# EEZ_DIB_DCP505_r1B2.net
KiCad netlist of a schematic drawn in EAGLE
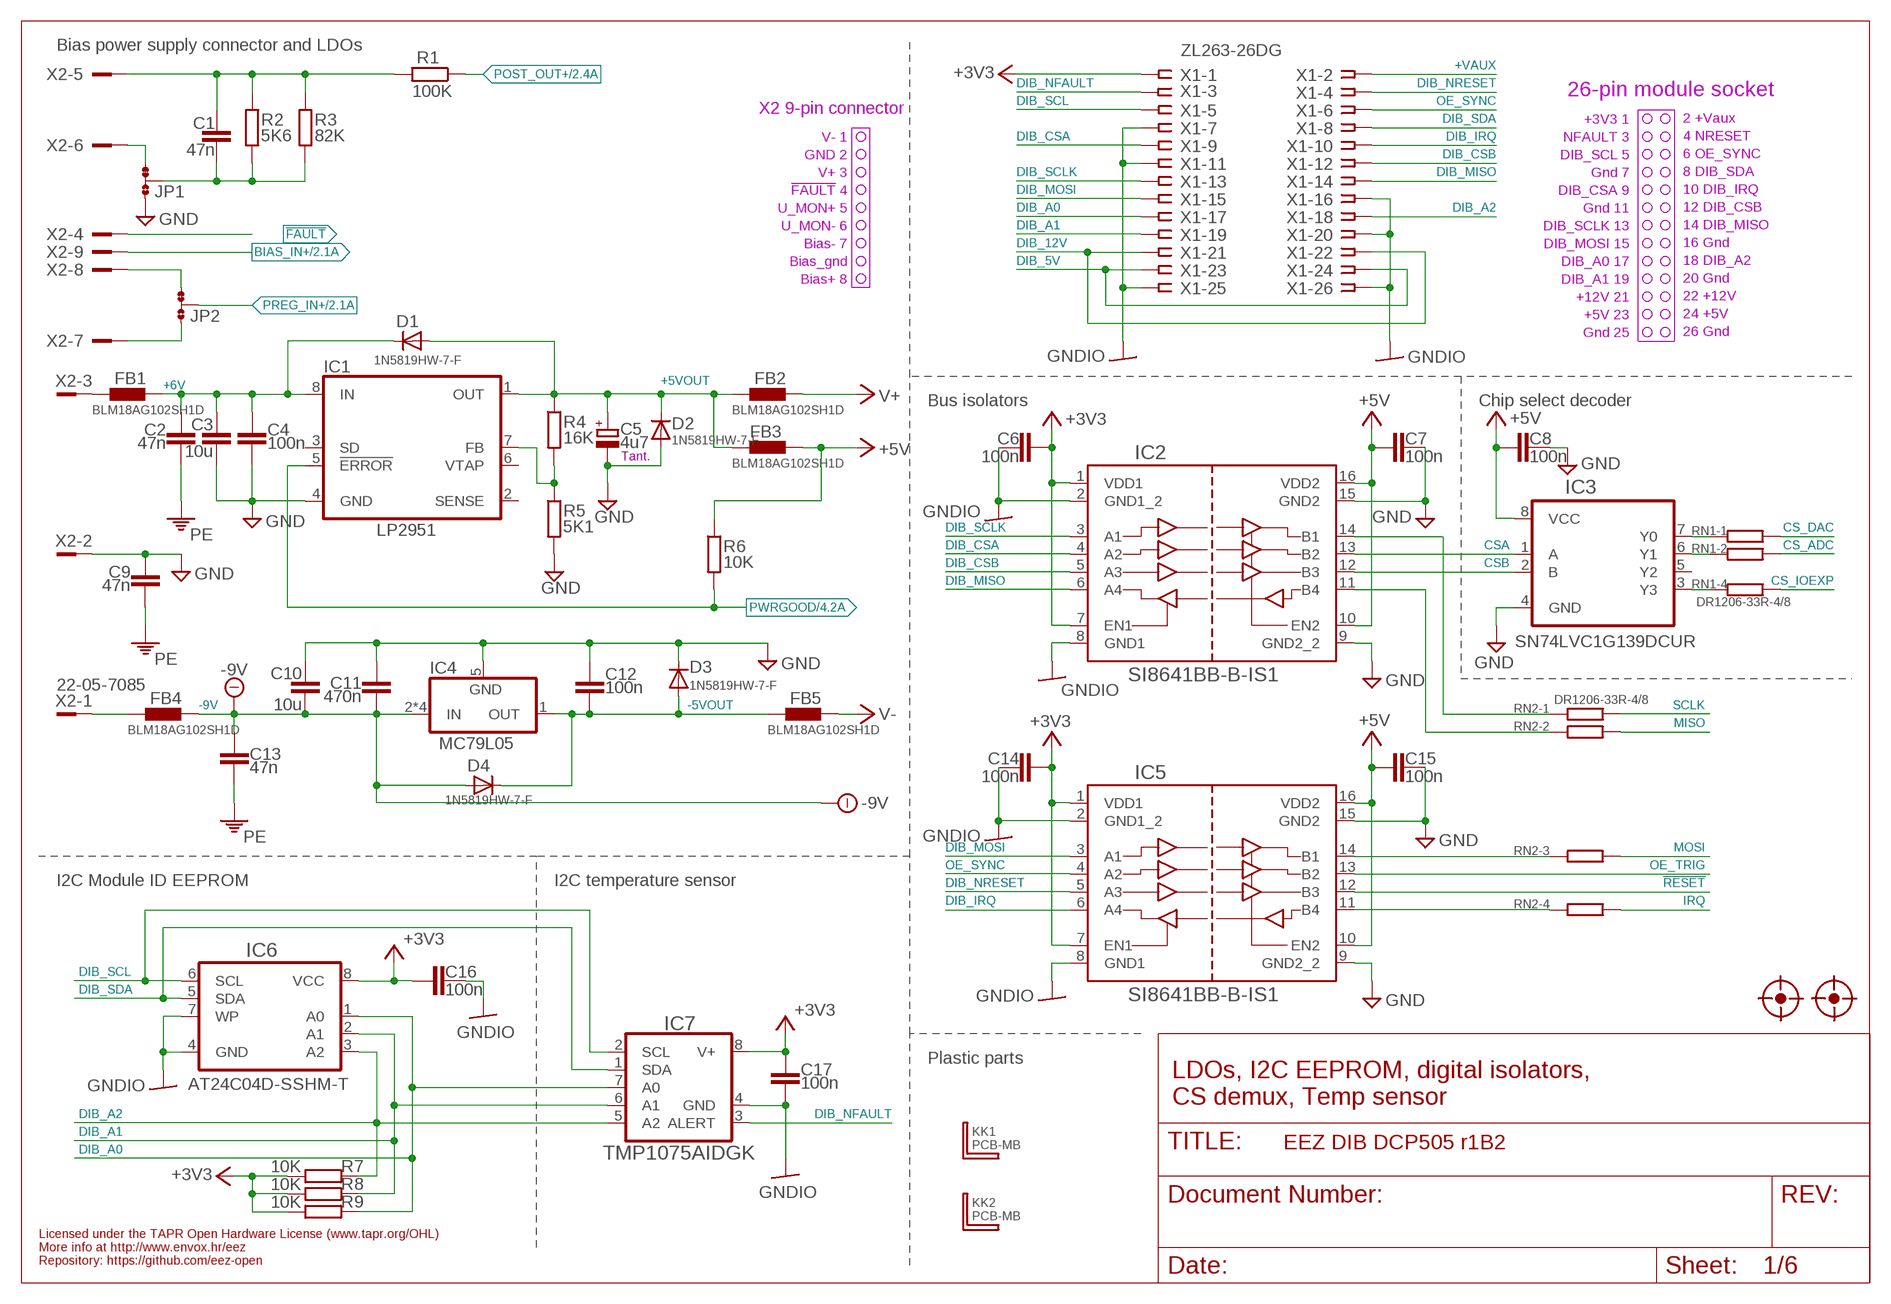
[diagram p0: schematic, sheet 1]
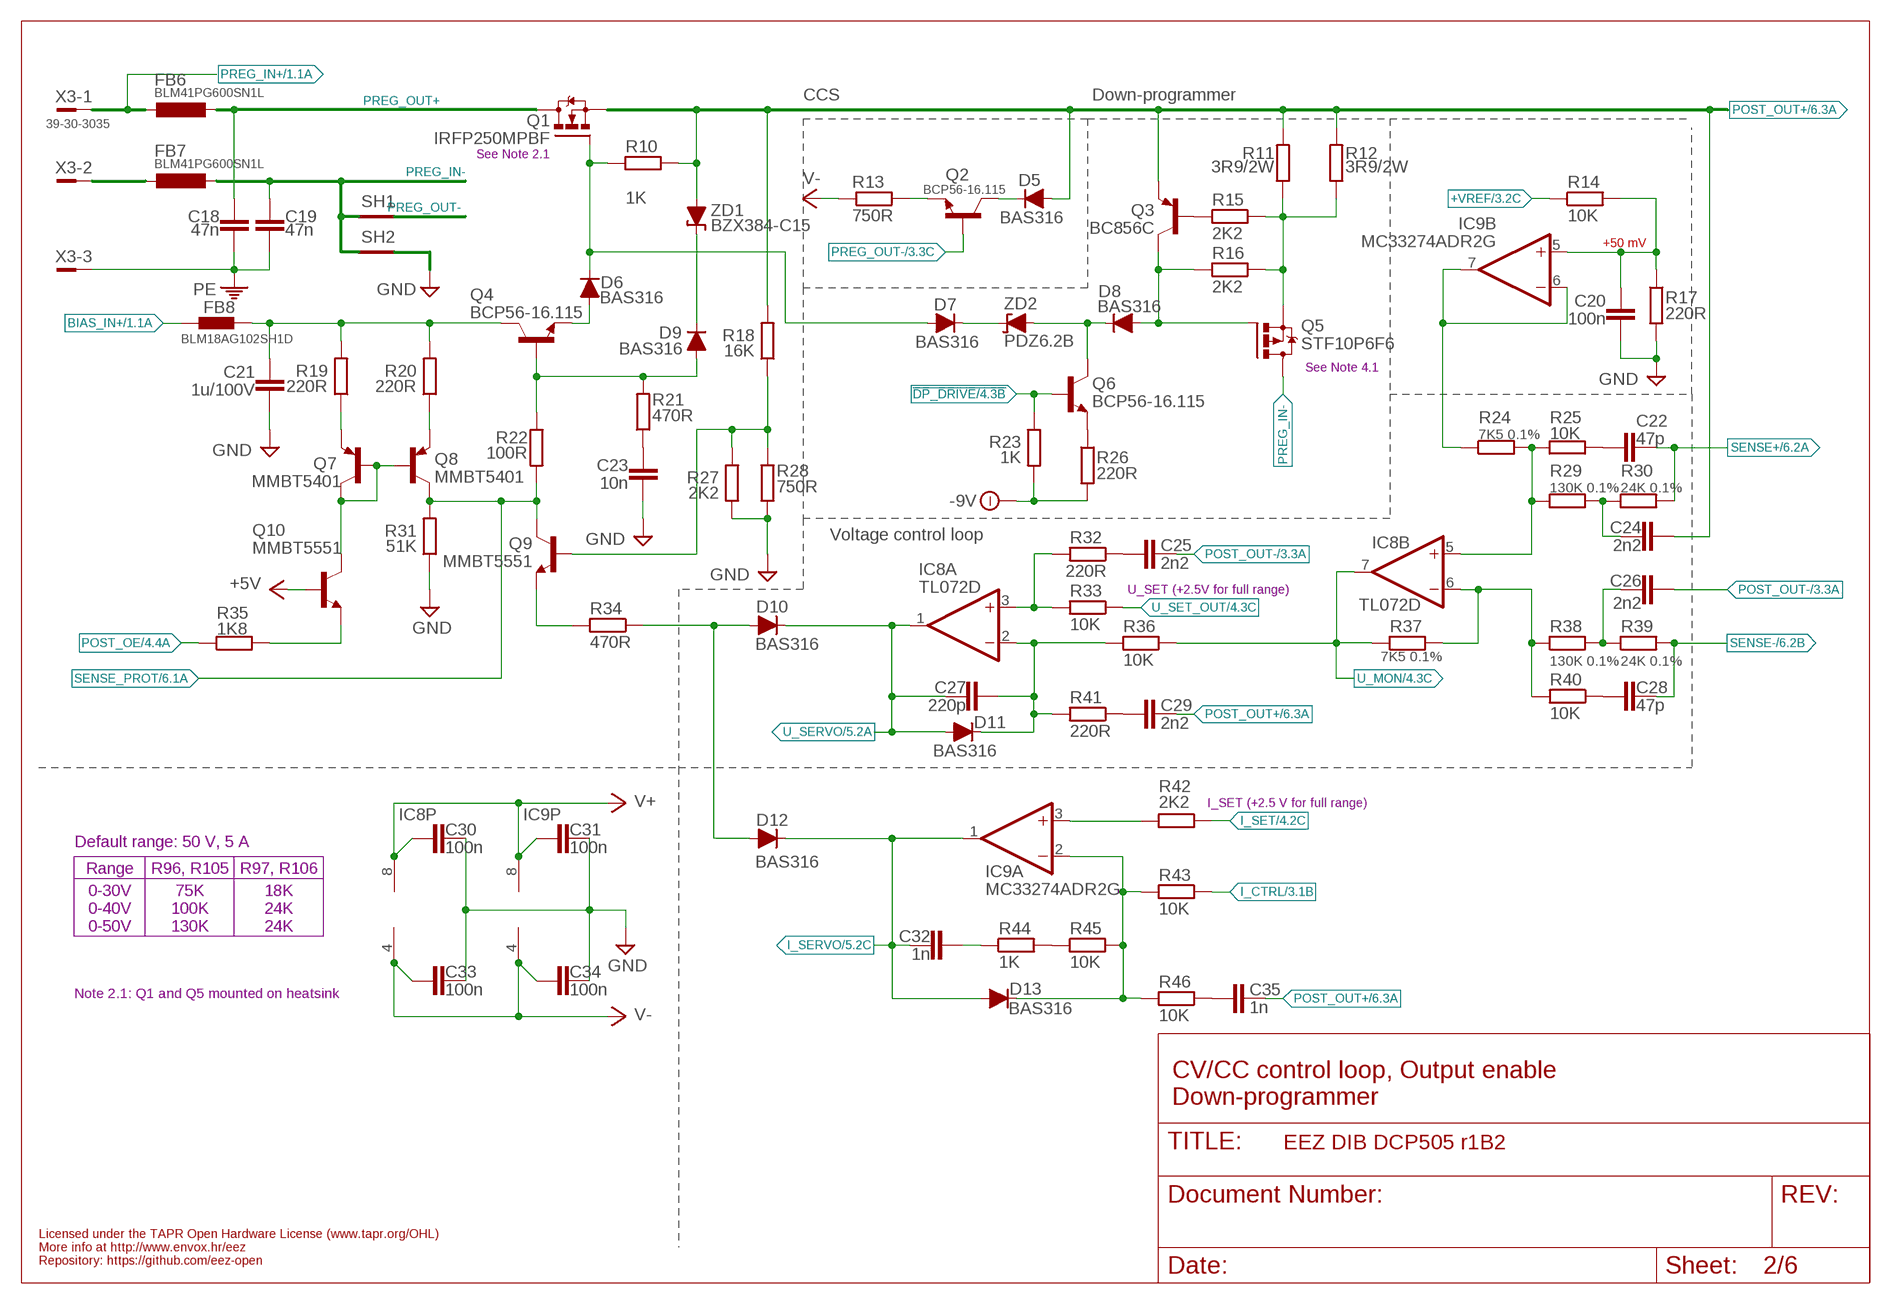
[diagram p1: schematic, sheet 2]
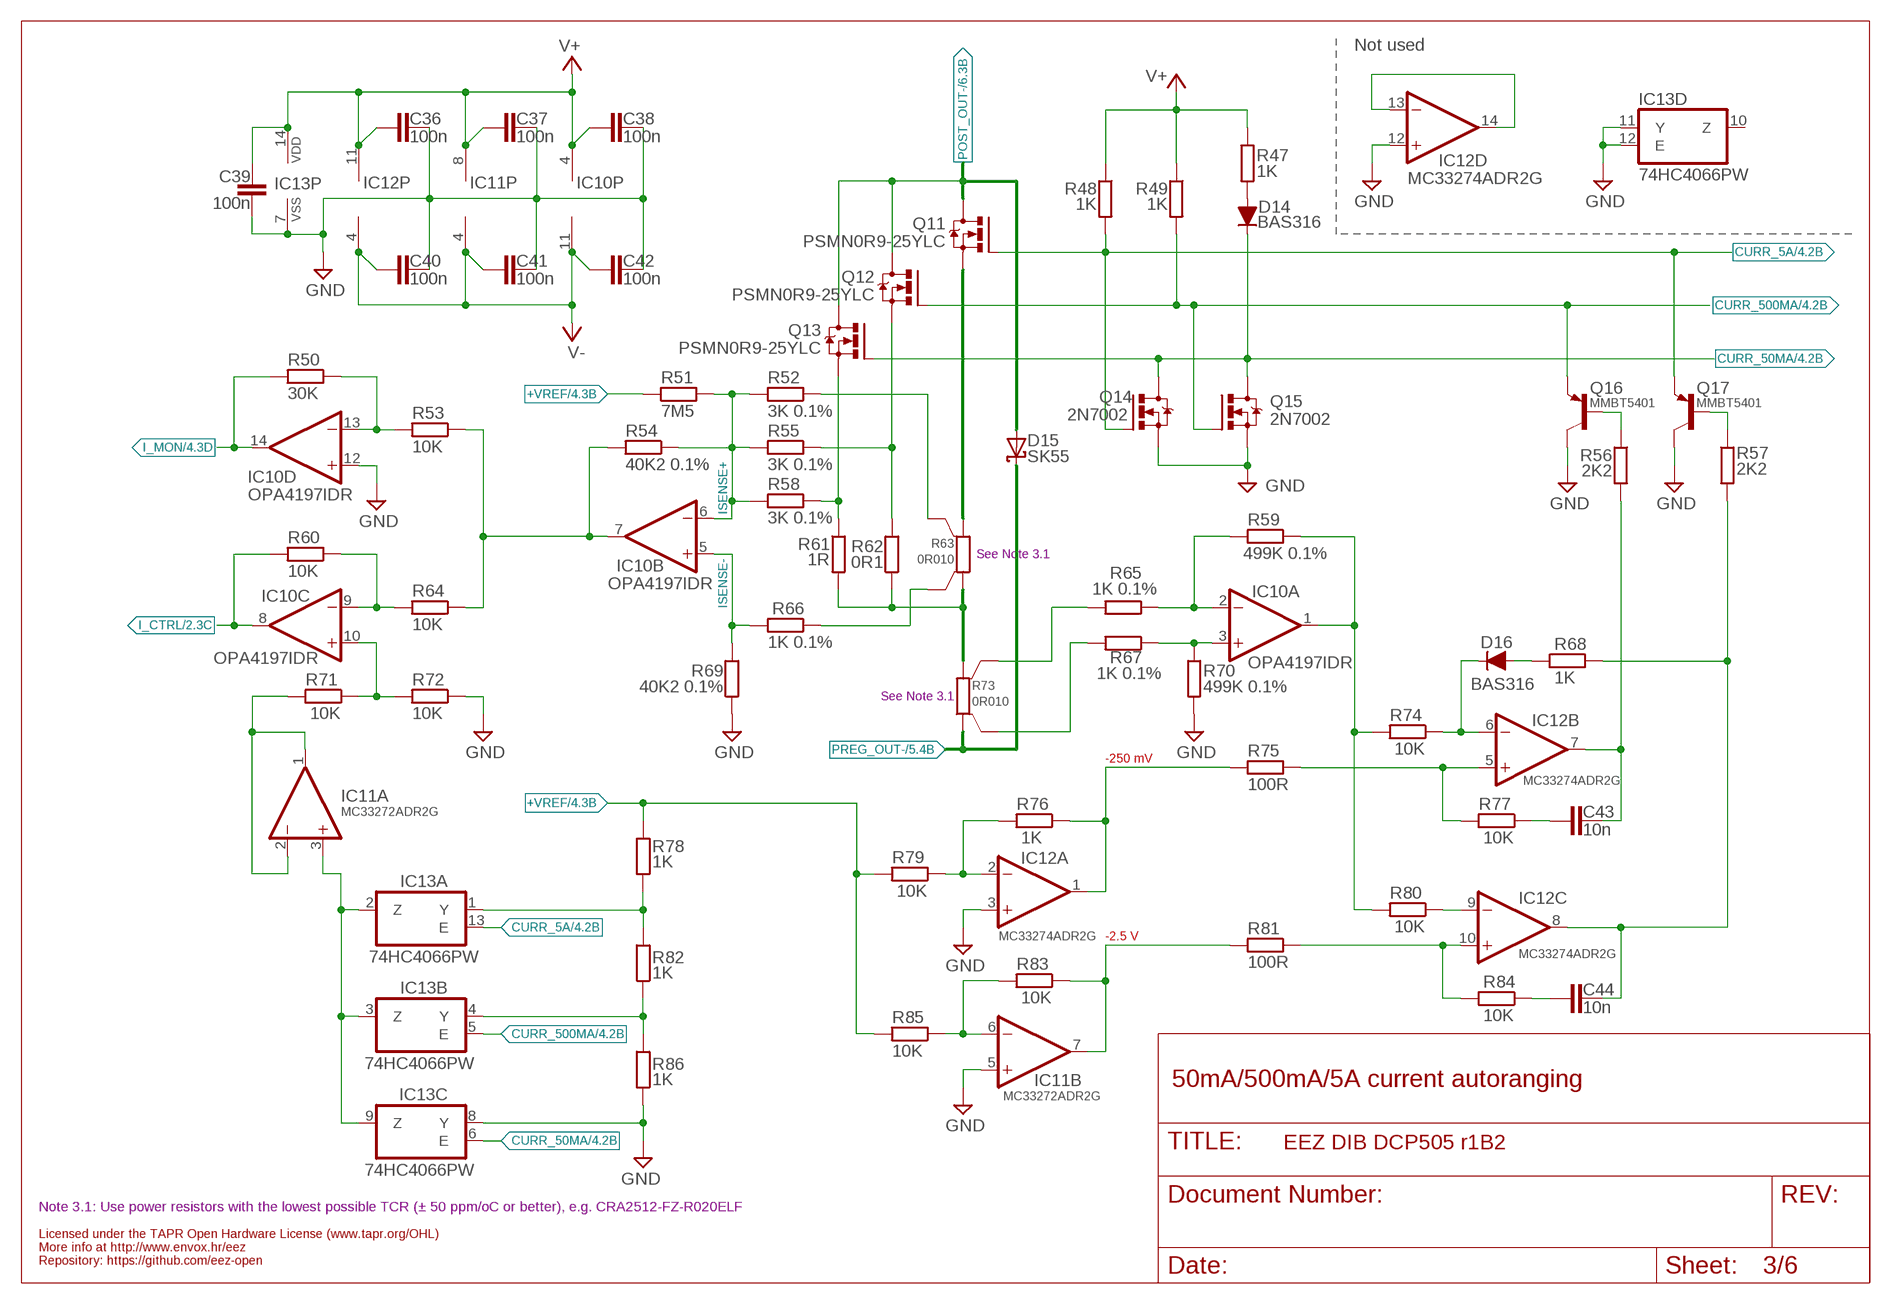
[diagram p2: schematic, sheet 3]
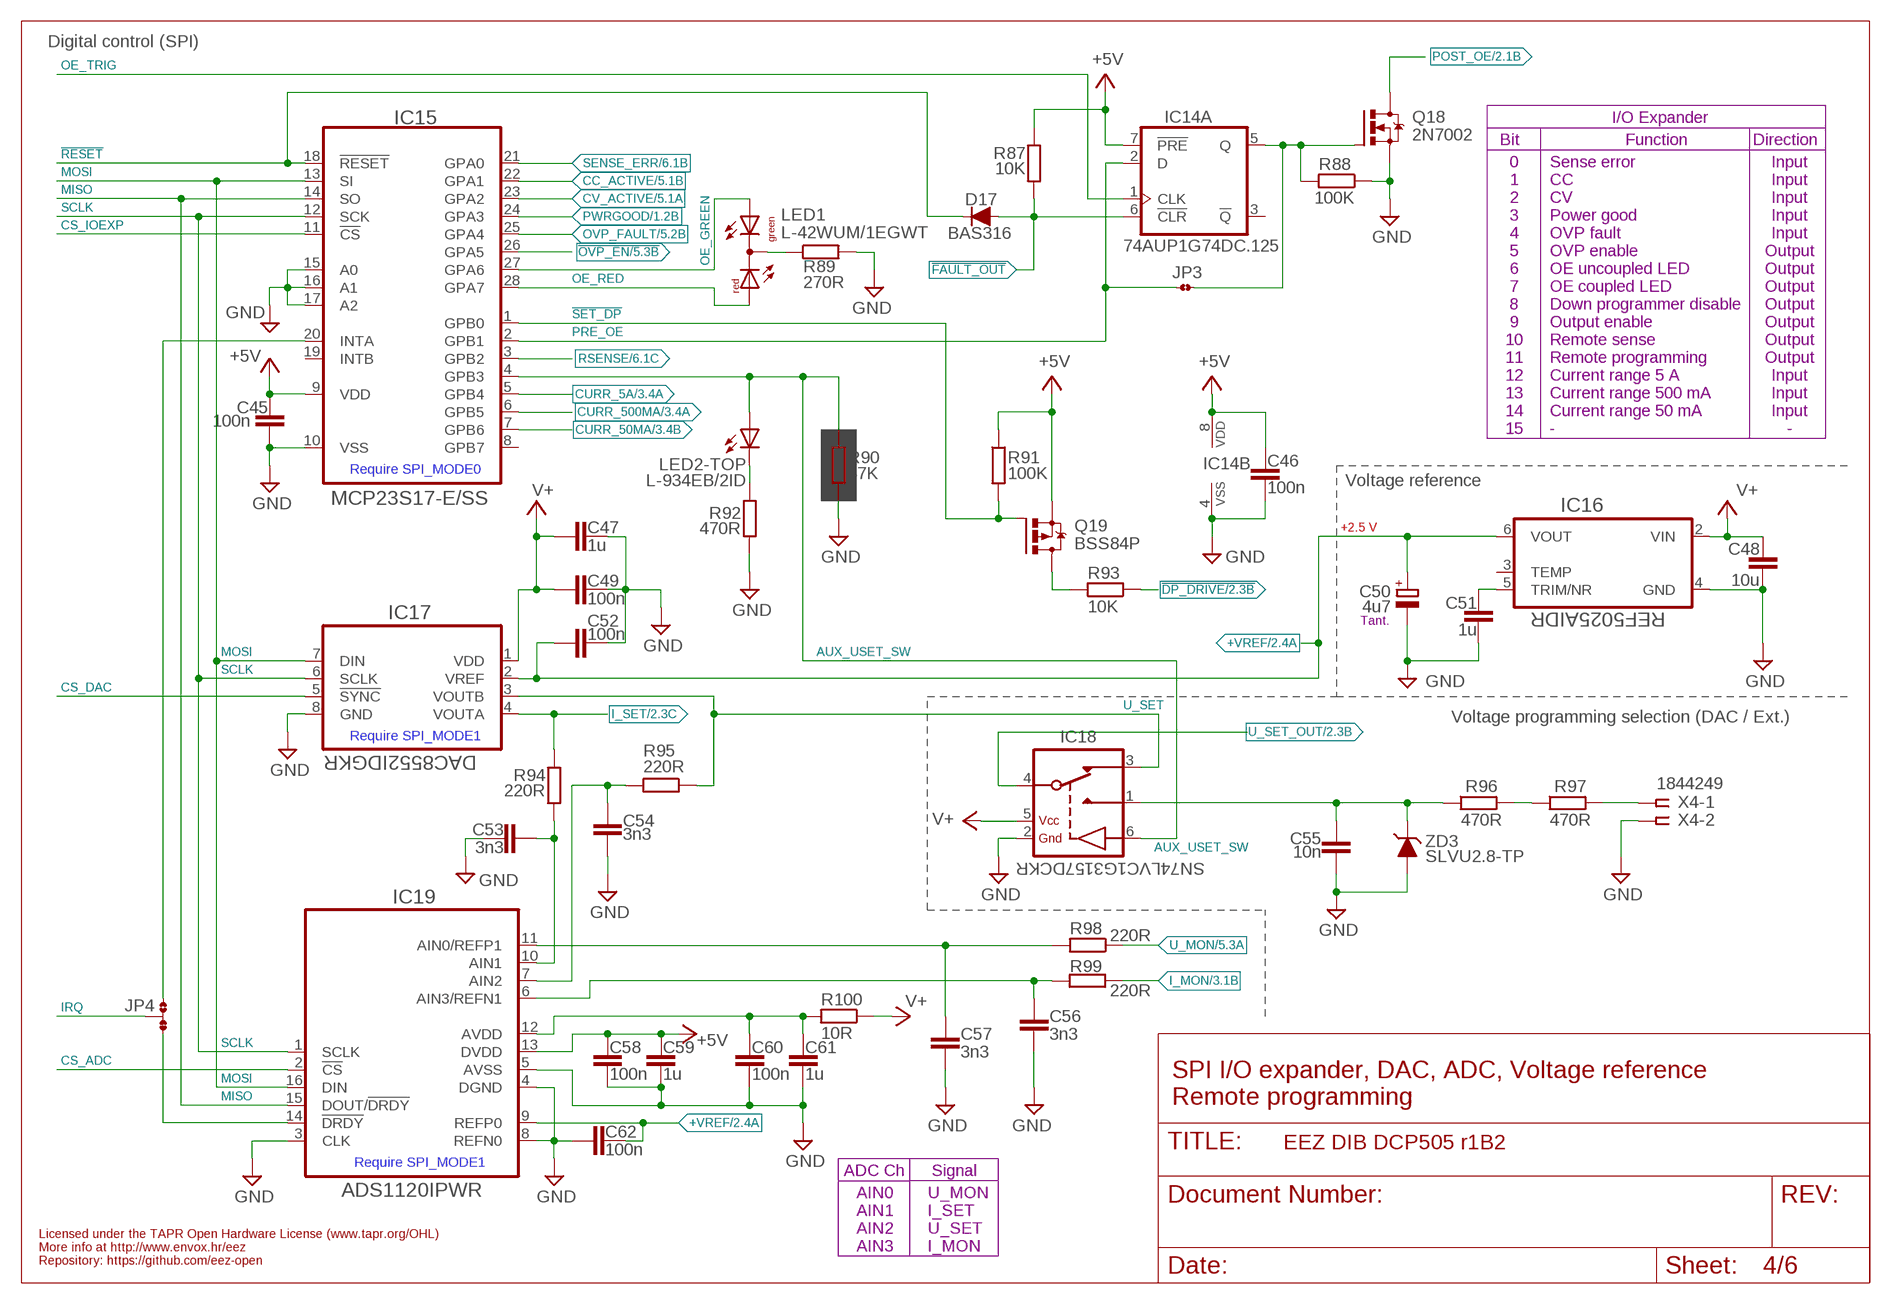
[diagram p3: schematic, sheet 4]
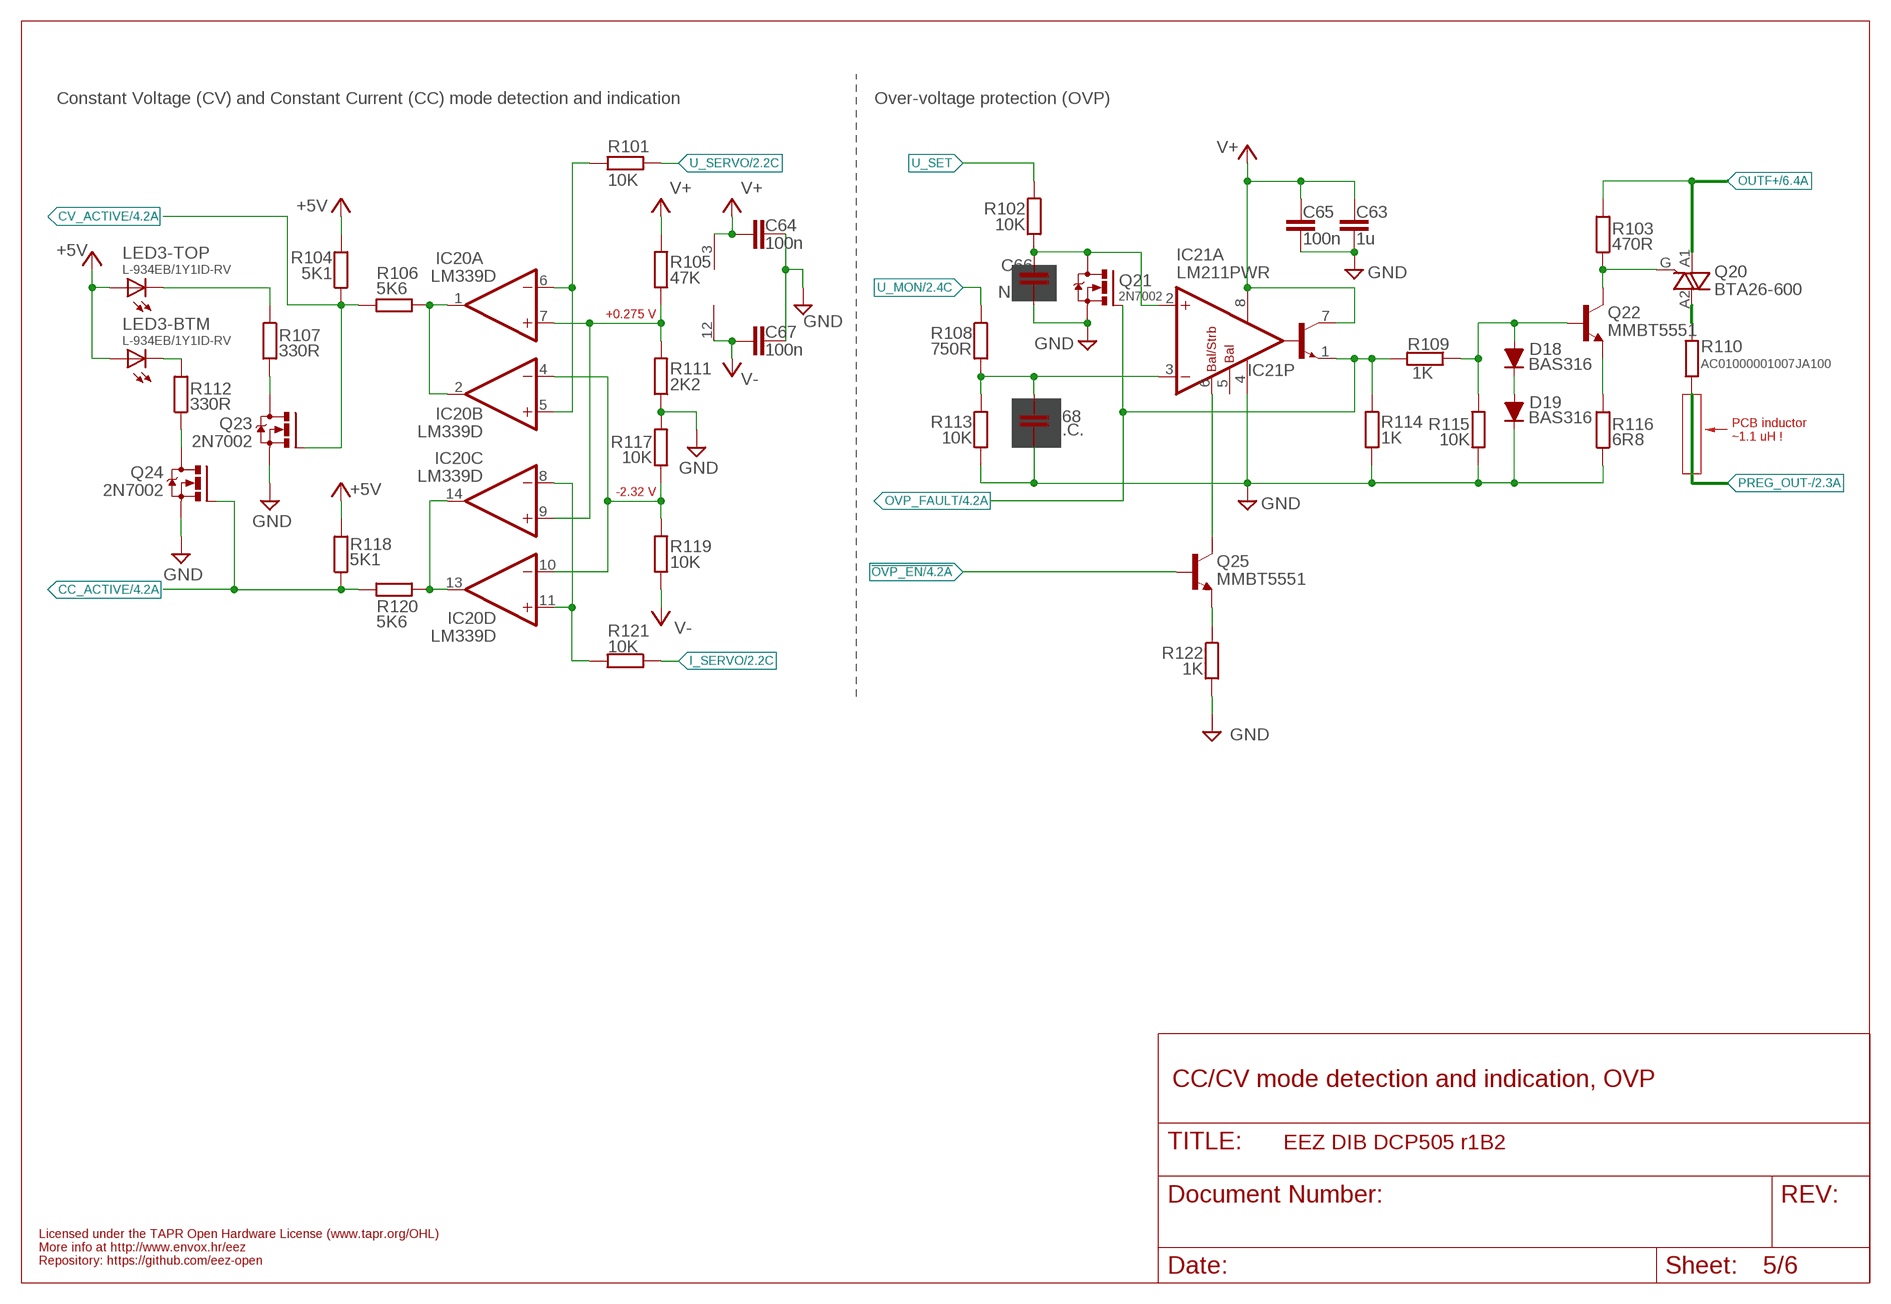
[diagram p4: schematic, sheet 5]
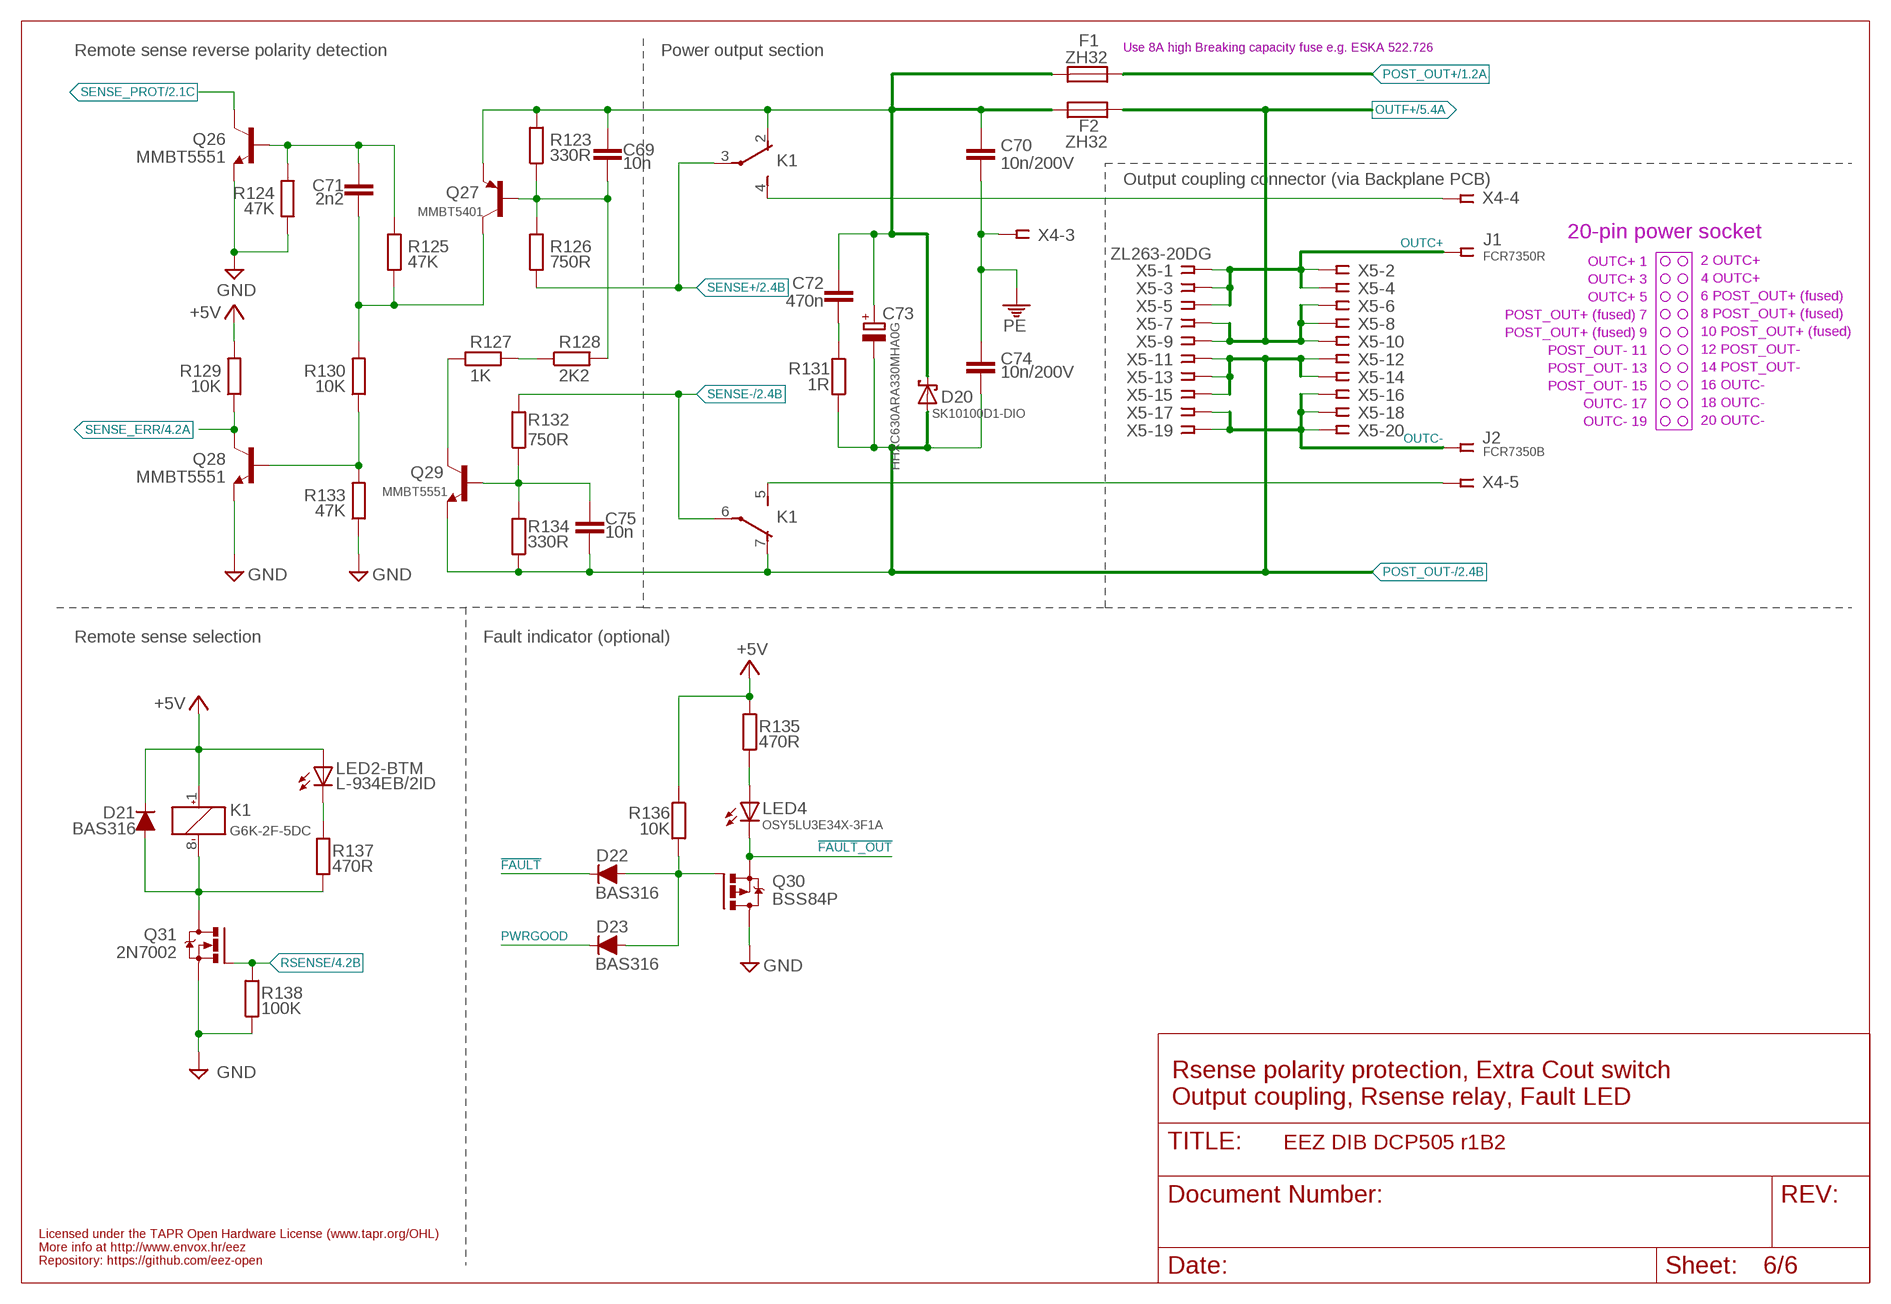
[diagram p5: schematic, sheet 6]

(export (version "E")
  (design (tool "Eeschema 10.0.6"))
  (components
    (comp (ref "C1")
      (value "47n")
      (footprint "eagle-import:C0805")
      (libsource (lib "eagle-import") (part "C-EUC0805"))
    )
    (comp (ref "C2")
      (value "47n")
      (footprint "eagle-import:C1206")
      (libsource (lib "eagle-import") (part "C-EUC1206"))
    )
    (comp (ref "C3")
      (value "10u")
      (footprint "eagle-import:C1206")
      (libsource (lib "eagle-import") (part "C-EUC1206"))
    )
    (comp (ref "C4")
      (value "100n")
      (footprint "eagle-import:C0603")
      (libsource (lib "eagle-import") (part "C-EUC0603"))
    )
    (comp (ref "C5")
      (value "4u7")
      (footprint "eagle-import:EC1206")
      (libsource (lib "eagle-import") (part "ECAP1206"))
    )
    (comp (ref "C6")
      (value "100n")
      (footprint "eagle-import:C0603")
      (libsource (lib "eagle-import") (part "C-EUC0603"))
    )
    (comp (ref "C7")
      (value "100n")
      (footprint "eagle-import:C0603")
      (libsource (lib "eagle-import") (part "C-EUC0603"))
    )
    (comp (ref "C8")
      (value "100n")
      (footprint "eagle-import:C0603")
      (libsource (lib "eagle-import") (part "C-EUC0603"))
    )
    (comp (ref "C9")
      (value "47n")
      (footprint "eagle-import:C1206")
      (libsource (lib "eagle-import") (part "C-EUC1206"))
    )
    (comp (ref "C10")
      (value "10u")
      (footprint "eagle-import:C1206")
      (libsource (lib "eagle-import") (part "C-EUC1206"))
    )
    (comp (ref "C11")
      (value "470n")
      (footprint "eagle-import:C0805")
      (libsource (lib "eagle-import") (part "C-EUC0805"))
    )
    (comp (ref "C12")
      (value "100n")
      (footprint "eagle-import:C0603")
      (libsource (lib "eagle-import") (part "C-EUC0603"))
    )
    (comp (ref "C13")
      (value "47n")
      (footprint "eagle-import:C1206")
      (libsource (lib "eagle-import") (part "C-EUC1206"))
    )
    (comp (ref "C14")
      (value "100n")
      (footprint "eagle-import:C0603")
      (libsource (lib "eagle-import") (part "C-EUC0603"))
    )
    (comp (ref "C15")
      (value "100n")
      (footprint "eagle-import:C0603")
      (libsource (lib "eagle-import") (part "C-EUC0603"))
    )
    (comp (ref "C16")
      (value "100n")
      (footprint "eagle-import:C0603")
      (libsource (lib "eagle-import") (part "C-EUC0603"))
    )
    (comp (ref "C17")
      (value "100n")
      (footprint "eagle-import:C0603")
      (libsource (lib "eagle-import") (part "C-EUC0603"))
    )
    (comp (ref "D1")
      (value "1N5819HW-7-F")
      (footprint "eagle-import:SOD323-W")
      (libsource (lib "eagle-import") (part "DIODE-SOD323-W"))
    )
    (comp (ref "D2")
      (value "1N5819HW-7-F")
      (footprint "eagle-import:SOD323-W")
      (libsource (lib "eagle-import") (part "DIODE-SOD323-W"))
    )
    (comp (ref "D3")
      (value "1N5819HW-7-F")
      (footprint "eagle-import:SOD323-W")
      (libsource (lib "eagle-import") (part "DIODE-SOD323-W"))
    )
    (comp (ref "D4")
      (value "1N5819HW-7-F")
      (footprint "eagle-import:SOD323-W")
      (libsource (lib "eagle-import") (part "DIODE-SOD323-W"))
    )
    (comp (ref "FB1")
      (value "BLM18AG102SH1D")
      (footprint "eagle-import:BEAD0603")
      (libsource (lib "eagle-import") (part "EEZ_inductors_and_transformers_FERRITE_BEAD0603"))
    )
    (comp (ref "FB2")
      (value "BLM18AG102SH1D")
      (footprint "eagle-import:BEAD0603")
      (libsource (lib "eagle-import") (part "EEZ_inductors_and_transformers_FERRITE_BEAD0603"))
    )
    (comp (ref "FB3")
      (value "BLM18AG102SH1D")
      (footprint "eagle-import:BEAD0603")
      (libsource (lib "eagle-import") (part "EEZ_inductors_and_transformers_FERRITE_BEAD0603"))
    )
    (comp (ref "FB4")
      (value "BLM18AG102SH1D")
      (footprint "eagle-import:BEAD0603")
      (libsource (lib "eagle-import") (part "EEZ_inductors_and_transformers_FERRITE_BEAD0603"))
    )
    (comp (ref "FB5")
      (value "BLM18AG102SH1D")
      (footprint "eagle-import:BEAD0603")
      (libsource (lib "eagle-import") (part "EEZ_inductors_and_transformers_FERRITE_BEAD0603"))
    )
    (comp (ref "FM1")
      (value "FIDUCIAL_2")
      (footprint "eagle-import:FIDUCIAL_DUAL")
      (libsource (lib "eagle-import") (part "FIDUCIAL_2"))
    )
    (comp (ref "FM2")
      (value "FIDUCIAL_2")
      (footprint "eagle-import:FIDUCIAL_DUAL")
      (libsource (lib "eagle-import") (part "FIDUCIAL_2"))
    )
    (comp (ref "IC1")
      (value "LP2951")
      (footprint "eagle-import:SOIC127P600X175-8N")
      (libsource (lib "eagle-import") (part "LP2951SO8"))
    )
    (comp (ref "IC2")
      (value "SI8641BB-B-IS1")
      (footprint "eagle-import:SOIC-16")
      (libsource (lib "eagle-import") (part "SI8641NSOIC-16"))
    )
    (comp (ref "IC3")
      (value "SN74LVC1G139DCUR")
      (footprint "eagle-import:DCU8")
      (libsource (lib "eagle-import") (part "SN74LVC1G139-VSSOP"))
    )
    (comp (ref "IC4")
      (value "MC79L05")
      (footprint "eagle-import:SOIC127P600X173-8N")
      (libsource (lib "eagle-import") (part "MC79LXXSOIC"))
    )
    (comp (ref "IC5")
      (value "SI8641BB-B-IS1")
      (footprint "eagle-import:SOIC-16")
      (libsource (lib "eagle-import") (part "SI8641NSOIC-16"))
    )
    (comp (ref "IC6")
      (value "AT24C04D-SSHM-T")
      (footprint "eagle-import:SOIC127P600X173-8N")
      (libsource (lib "eagle-import") (part "AT24CXXSOIC8"))
    )
    (comp (ref "IC7")
      (value "TMP1075AIDGK")
      (footprint "eagle-import:DGK8")
      (libsource (lib "eagle-import") (part "TMPX75DGK"))
    )
    (comp (ref "JP1")
      (value "JP3-CUT")
      (footprint "eagle-import:JP3-CUT")
      (libsource (lib "eagle-import") (part "JP3-CUT"))
    )
    (comp (ref "JP2")
      (value "JP3-CUT")
      (footprint "eagle-import:JP3-CUT")
      (libsource (lib "eagle-import") (part "JP3-CUT"))
    )
    (comp (ref "KK1")
      (value "PCB-MB")
      (footprint "eagle-import:PCB-MB")
      (libsource (lib "eagle-import") (part "PCB-MB"))
    )
    (comp (ref "KK2")
      (value "PCB-MB")
      (footprint "eagle-import:PCB-MB")
      (libsource (lib "eagle-import") (part "PCB-MB"))
    )
    (comp (ref "R1")
      (value "100K")
      (footprint "eagle-import:R0805")
      (libsource (lib "eagle-import") (part "R-EU_R0805"))
    )
    (comp (ref "R2")
      (value "5K6")
      (footprint "eagle-import:R0805")
      (libsource (lib "eagle-import") (part "R-EU_R0805"))
    )
    (comp (ref "R3")
      (value "82K")
      (footprint "eagle-import:R0805")
      (libsource (lib "eagle-import") (part "R-EU_R0805"))
    )
    (comp (ref "R4")
      (value "16K")
      (footprint "eagle-import:R0805")
      (libsource (lib "eagle-import") (part "R-EU_R0805"))
    )
    (comp (ref "R5")
      (value "5K1")
      (footprint "eagle-import:R0805")
      (libsource (lib "eagle-import") (part "R-EU_R0805"))
    )
    (comp (ref "R6")
      (value "10K")
      (footprint "eagle-import:R0805")
      (libsource (lib "eagle-import") (part "R-EU_R0805"))
    )
    (comp (ref "R7")
      (value "10K")
      (footprint "eagle-import:R0805")
      (libsource (lib "eagle-import") (part "R-EU_R0805"))
    )
    (comp (ref "R8")
      (value "10K")
      (footprint "eagle-import:R0805")
      (libsource (lib "eagle-import") (part "R-EU_R0805"))
    )
    (comp (ref "R9")
      (value "10K")
      (footprint "eagle-import:R0805")
      (libsource (lib "eagle-import") (part "R-EU_R0805"))
    )
    (comp (ref "RN1")
      (value "DR1206-33R-4/8")
      (footprint "eagle-import:CAY16")
      (libsource (lib "eagle-import") (part "R_ARRAY4"))
    )
    (comp (ref "RN2")
      (value "DR1206-33R-4/8")
      (footprint "eagle-import:CAY16")
      (libsource (lib "eagle-import") (part "R_ARRAY4"))
    )
    (comp (ref "X1")
      (value "ZL263-26DG")
      (footprint "eagle-import:SSW-113-02-T-D-RA")
      (libsource (lib "eagle-import") (part "SSW-113-02-T-D-RA"))
    )
    (comp (ref "X2")
      (value "22-05-7085")
      (footprint "eagle-import:SPOX_22-05-7095")
      (libsource (lib "eagle-import") (part "SPOX_22-05-7095"))
    )
    (comp (ref "C36")
      (value "100n")
      (footprint "eagle-import:C0603")
      (libsource (lib "eagle-import") (part "C-EUC0603"))
    )
    (comp (ref "C37")
      (value "100n")
      (footprint "eagle-import:C0603")
      (libsource (lib "eagle-import") (part "C-EUC0603"))
    )
    (comp (ref "C38")
      (value "100n")
      (footprint "eagle-import:C0603")
      (libsource (lib "eagle-import") (part "C-EUC0603"))
    )
    (comp (ref "C39")
      (value "100n")
      (footprint "eagle-import:C0603")
      (libsource (lib "eagle-import") (part "C-EUC0603"))
    )
    (comp (ref "C40")
      (value "100n")
      (footprint "eagle-import:C0603")
      (libsource (lib "eagle-import") (part "C-EUC0603"))
    )
    (comp (ref "C41")
      (value "100n")
      (footprint "eagle-import:C0603")
      (libsource (lib "eagle-import") (part "C-EUC0603"))
    )
    (comp (ref "C42")
      (value "100n")
      (footprint "eagle-import:C0603")
      (libsource (lib "eagle-import") (part "C-EUC0603"))
    )
    (comp (ref "C43")
      (value "10n")
      (footprint "eagle-import:C0603")
      (libsource (lib "eagle-import") (part "C-EUC0603"))
    )
    (comp (ref "C44")
      (value "10n")
      (footprint "eagle-import:C0603")
      (libsource (lib "eagle-import") (part "C-EUC0603"))
    )
    (comp (ref "D14")
      (value "BAS316")
      (footprint "eagle-import:SOD323-R")
      (libsource (lib "eagle-import") (part "DIODESOD323R"))
    )
    (comp (ref "D15")
      (value "SK55")
      (footprint "eagle-import:SMB")
      (libsource (lib "eagle-import") (part "SCHOTTKYSMB"))
    )
    (comp (ref "D16")
      (value "BAS316")
      (footprint "eagle-import:SOD323-R")
      (libsource (lib "eagle-import") (part "DIODESOD323R"))
    )
    (comp (ref "IC10")
      (value "OPA4197IDR")
      (footprint "eagle-import:SOIC127P600X175-14N")
      (fields (field (name "MPN") "TL074ACD"))
      (libsource (lib "eagle-import") (part "TL074SOIC14"))
    )
    (comp (ref "IC11")
      (value "MC33272ADR2G")
      (footprint "eagle-import:SOIC127P600X173-8N")
      (libsource (lib "eagle-import") (part "TL072SOIC8"))
    )
    (comp (ref "IC12")
      (value "MC33274ADR2G")
      (footprint "eagle-import:SOIC127P600X175-14N")
      (fields (field (name "MPN") "TL074ACD"))
      (libsource (lib "eagle-import") (part "TL074SOIC14"))
    )
    (comp (ref "IC13")
      (value "74HC4066PW")
      (footprint "eagle-import:SOP65P640X120-14N")
      (libsource (lib "eagle-import") (part "74HC4066PW"))
    )
    (comp (ref "Q11")
      (value "PSMN0R9-25YLC")
      (footprint "eagle-import:SOT669")
      (libsource (lib "eagle-import") (part "N-MOSFETLFPAK"))
    )
    (comp (ref "Q12")
      (value "PSMN0R9-25YLC")
      (footprint "eagle-import:SOT669")
      (libsource (lib "eagle-import") (part "N-MOSFETLFPAK"))
    )
    (comp (ref "Q13")
      (value "PSMN0R9-25YLC")
      (footprint "eagle-import:SOT669")
      (libsource (lib "eagle-import") (part "N-MOSFETLFPAK"))
    )
    (comp (ref "Q14")
      (value "2N7002")
      (footprint "eagle-import:SOT103P240X110-3N")
      (fields
        (field (name "MPN") "2N7002-7-F")
        (field (name "MPN_1") "2N7002-7-F")
        (field (name "OC_FARNELL") "1713823")
        (field (name "OC_NEWARK") "25R5679")
        (field (name "PACKAGE") "SOT-23-3")
        (field (name "SUPPLIER") "DIODES INC.")
      )
      (libsource (lib "eagle-import") (part "2N7002"))
    )
    (comp (ref "Q15")
      (value "2N7002")
      (footprint "eagle-import:SOT103P240X110-3N")
      (fields
        (field (name "MPN") "2N7002-7-F")
        (field (name "MPN_1") "2N7002-7-F")
        (field (name "OC_FARNELL") "1713823")
        (field (name "OC_NEWARK") "25R5679")
        (field (name "PACKAGE") "SOT-23-3")
        (field (name "SUPPLIER") "DIODES INC.")
      )
      (libsource (lib "eagle-import") (part "2N7002"))
    )
    (comp (ref "Q16")
      (value "MMBT5401")
      (footprint "eagle-import:SOT23-BEC")
      (libsource (lib "eagle-import") (part "-PNP-SOT23-BECBC857B"))
    )
    (comp (ref "Q17")
      (value "MMBT5401")
      (footprint "eagle-import:SOT23-BEC")
      (libsource (lib "eagle-import") (part "-PNP-SOT23-BECBC857B"))
    )
    (comp (ref "R47")
      (value "1K")
      (footprint "eagle-import:R0805")
      (libsource (lib "eagle-import") (part "R-EU_R0805"))
    )
    (comp (ref "R48")
      (value "1K")
      (footprint "eagle-import:R0805")
      (libsource (lib "eagle-import") (part "R-EU_R0805"))
    )
    (comp (ref "R49")
      (value "1K")
      (footprint "eagle-import:R0805")
      (libsource (lib "eagle-import") (part "R-EU_R0805"))
    )
    (comp (ref "R50")
      (value "30K")
      (footprint "eagle-import:R0805")
      (libsource (lib "eagle-import") (part "R-EU_R0805"))
    )
    (comp (ref "R51")
      (value "7M5")
      (footprint "eagle-import:R0805")
      (libsource (lib "eagle-import") (part "R-EU_R0805"))
    )
    (comp (ref "R52")
      (value "3K 0.1%")
      (footprint "eagle-import:R0603")
      (libsource (lib "eagle-import") (part "R-EU_R0603"))
    )
    (comp (ref "R53")
      (value "10K")
      (footprint "eagle-import:R0805")
      (libsource (lib "eagle-import") (part "R-EU_R0805"))
    )
    (comp (ref "R54")
      (value "40K2 0.1%")
      (footprint "eagle-import:R0603")
      (libsource (lib "eagle-import") (part "R-EU_R0603"))
    )
    (comp (ref "R55")
      (value "3K 0.1%")
      (footprint "eagle-import:R0603")
      (libsource (lib "eagle-import") (part "R-EU_R0603"))
    )
    (comp (ref "R56")
      (value "2K2")
      (footprint "eagle-import:R0805")
      (libsource (lib "eagle-import") (part "R-EU_R0805"))
    )
    (comp (ref "R57")
      (value "2K2")
      (footprint "eagle-import:R0805")
      (libsource (lib "eagle-import") (part "R-EU_R0805"))
    )
    (comp (ref "R58")
      (value "3K 0.1%")
      (footprint "eagle-import:R0603")
      (libsource (lib "eagle-import") (part "R-EU_R0603"))
    )
    (comp (ref "R59")
      (value "499K 0.1%")
      (footprint "eagle-import:R0603")
      (libsource (lib "eagle-import") (part "R-EU_R0603"))
    )
    (comp (ref "R60")
      (value "10K")
      (footprint "eagle-import:R0805")
      (libsource (lib "eagle-import") (part "R-EU_R0805"))
    )
    (comp (ref "R61")
      (value "1R")
      (footprint "eagle-import:R0805")
      (libsource (lib "eagle-import") (part "R-EU_R0805"))
    )
    (comp (ref "R62")
      (value "0R1")
      (footprint "eagle-import:R1206")
      (libsource (lib "eagle-import") (part "R-EU_R1206"))
    )
    (comp (ref "R63")
      (value "0R010")
      (footprint "eagle-import:R_H2728")
      (libsource (lib "eagle-import") (part "R-EU_4WIREH2728"))
    )
    (comp (ref "R64")
      (value "10K")
      (footprint "eagle-import:R0805")
      (libsource (lib "eagle-import") (part "R-EU_R0805"))
    )
    (comp (ref "R65")
      (value "1K 0.1%")
      (footprint "eagle-import:R0603")
      (libsource (lib "eagle-import") (part "R-EU_R0603"))
    )
    (comp (ref "R66")
      (value "1K 0.1%")
      (footprint "eagle-import:R0603")
      (libsource (lib "eagle-import") (part "R-EU_R0603"))
    )
    (comp (ref "R67")
      (value "1K 0.1%")
      (footprint "eagle-import:R0603")
      (libsource (lib "eagle-import") (part "R-EU_R0603"))
    )
    (comp (ref "R68")
      (value "1K")
      (footprint "eagle-import:R0805")
      (libsource (lib "eagle-import") (part "R-EU_R0805"))
    )
    (comp (ref "R69")
      (value "40K2 0.1%")
      (footprint "eagle-import:R0603")
      (libsource (lib "eagle-import") (part "R-EU_R0603"))
    )
    (comp (ref "R70")
      (value "499K 0.1%")
      (footprint "eagle-import:R0603")
      (libsource (lib "eagle-import") (part "R-EU_R0603"))
    )
    (comp (ref "R71")
      (value "10K")
      (footprint "eagle-import:R0805")
      (libsource (lib "eagle-import") (part "R-EU_R0805"))
    )
    (comp (ref "R72")
      (value "10K")
      (footprint "eagle-import:R0805")
      (libsource (lib "eagle-import") (part "R-EU_R0805"))
    )
    (comp (ref "R73")
      (value "0R010")
      (footprint "eagle-import:R_H2728")
      (libsource (lib "eagle-import") (part "R-EU_4WIREH2728"))
    )
    (comp (ref "R74")
      (value "10K")
      (footprint "eagle-import:R0805")
      (libsource (lib "eagle-import") (part "R-EU_R0805"))
    )
    (comp (ref "R75")
      (value "100R")
      (footprint "eagle-import:R0805")
      (libsource (lib "eagle-import") (part "R-EU_R0805"))
    )
    (comp (ref "R76")
      (value "1K")
      (footprint "eagle-import:R0805")
      (libsource (lib "eagle-import") (part "R-EU_R0805"))
    )
    (comp (ref "R77")
      (value "10K")
      (footprint "eagle-import:R0805")
      (libsource (lib "eagle-import") (part "R-EU_R0805"))
    )
    (comp (ref "R78")
      (value "1K")
      (footprint "eagle-import:R0805")
      (libsource (lib "eagle-import") (part "R-EU_R0805"))
    )
    (comp (ref "R79")
      (value "10K")
      (footprint "eagle-import:R0805")
      (libsource (lib "eagle-import") (part "R-EU_R0805"))
    )
    (comp (ref "R80")
      (value "10K")
      (footprint "eagle-import:R0805")
      (libsource (lib "eagle-import") (part "R-EU_R0805"))
    )
    (comp (ref "R81")
      (value "100R")
      (footprint "eagle-import:R0805")
      (libsource (lib "eagle-import") (part "R-EU_R0805"))
    )
    (comp (ref "R82")
      (value "1K")
      (footprint "eagle-import:R0805")
      (libsource (lib "eagle-import") (part "R-EU_R0805"))
    )
    (comp (ref "R83")
      (value "10K")
      (footprint "eagle-import:R0805")
      (libsource (lib "eagle-import") (part "R-EU_R0805"))
    )
    (comp (ref "R84")
      (value "10K")
      (footprint "eagle-import:R0805")
      (libsource (lib "eagle-import") (part "R-EU_R0805"))
    )
    (comp (ref "R85")
      (value "10K")
      (footprint "eagle-import:R0805")
      (libsource (lib "eagle-import") (part "R-EU_R0805"))
    )
    (comp (ref "R86")
      (value "1K")
      (footprint "eagle-import:R0805")
      (libsource (lib "eagle-import") (part "R-EU_R0805"))
    )
    (comp (ref "C63")
      (value "1u")
      (footprint "eagle-import:C0805")
      (libsource (lib "eagle-import") (part "C-EUC0805"))
    )
    (comp (ref "C64")
      (value "100n")
      (footprint "eagle-import:C0603")
      (libsource (lib "eagle-import") (part "C-EUC0603"))
    )
    (comp (ref "C65")
      (value "100n")
      (footprint "eagle-import:C0603")
      (libsource (lib "eagle-import") (part "C-EUC0603"))
    )
    (comp (ref "C66")
      (value "N.C.")
      (footprint "eagle-import:C0805")
      (libsource (lib "eagle-import") (part "C-EUC0805"))
    )
    (comp (ref "C67")
      (value "100n")
      (footprint "eagle-import:C0603")
      (libsource (lib "eagle-import") (part "C-EUC0603"))
    )
    (comp (ref "C68")
      (value "N.C.")
      (footprint "eagle-import:C0805")
      (libsource (lib "eagle-import") (part "C-EUC0805"))
    )
    (comp (ref "D18")
      (value "BAS316")
      (footprint "eagle-import:SOD323-R")
      (libsource (lib "eagle-import") (part "DIODESOD323R"))
    )
    (comp (ref "D19")
      (value "BAS316")
      (footprint "eagle-import:SOD323-R")
      (libsource (lib "eagle-import") (part "DIODESOD323R"))
    )
    (comp (ref "IC20")
      (value "LM339D")
      (footprint "eagle-import:SOIC127P600X175-14N")
      (libsource (lib "eagle-import") (part "LM339SO14"))
    )
    (comp (ref "IC21")
      (value "LM211PWR")
      (footprint "eagle-import:PW8_TSSOP8")
      (libsource (lib "eagle-import") (part "LM211"))
    )
    (comp (ref "LED3")
      (value "L-934EB/1Y1ID-RV")
      (footprint "eagle-import:L-934EB")
      (libsource (lib "eagle-import") (part "LED_L-934EB/1Y1ID-RV"))
    )
    (comp (ref "Q20")
      (value "BTA26-600")
      (footprint "eagle-import:TOP3_TRIAC_NOHOLE")
      (libsource (lib "eagle-import") (part "BTA41-2"))
    )
    (comp (ref "Q21")
      (value "2N7002")
      (footprint "eagle-import:SOT103P240X110-3N")
      (fields
        (field (name "MPN") "2N7002-7-F")
        (field (name "MPN_1") "2N7002-7-F")
        (field (name "OC_FARNELL") "1713823")
        (field (name "OC_NEWARK") "25R5679")
        (field (name "PACKAGE") "SOT-23-3")
        (field (name "SUPPLIER") "DIODES INC.")
      )
      (libsource (lib "eagle-import") (part "2N7002"))
    )
    (comp (ref "Q22")
      (value "MMBT5551")
      (footprint "eagle-import:SOT23-BEC")
      (libsource (lib "eagle-import") (part "-NPN-SOT23-BECMMBT5551LT1"))
    )
    (comp (ref "Q23")
      (value "2N7002")
      (footprint "eagle-import:SOT103P240X110-3N")
      (fields (field (name "MPN") "2N7002-7-F"))
      (libsource (lib "eagle-import") (part "2N7002"))
    )
    (comp (ref "Q24")
      (value "2N7002")
      (footprint "eagle-import:SOT103P240X110-3N")
      (fields (field (name "MPN") "2N7002-7-F"))
      (libsource (lib "eagle-import") (part "2N7002"))
    )
    (comp (ref "Q25")
      (value "MMBT5551")
      (footprint "eagle-import:SOT23-BEC")
      (libsource (lib "eagle-import") (part "-NPN-SOT23-BECMMBT5551LT1"))
    )
    (comp (ref "R101")
      (value "10K")
      (footprint "eagle-import:R0805")
      (libsource (lib "eagle-import") (part "R-EU_R0805"))
    )
    (comp (ref "R102")
      (value "10K")
      (footprint "eagle-import:R0805")
      (libsource (lib "eagle-import") (part "R-EU_R0805"))
    )
    (comp (ref "R103")
      (value "470R")
      (footprint "eagle-import:R0805")
      (libsource (lib "eagle-import") (part "R-EU_R0805"))
    )
    (comp (ref "R104")
      (value "5K1")
      (footprint "eagle-import:R0805")
      (libsource (lib "eagle-import") (part "R-EU_R0805"))
    )
    (comp (ref "R105")
      (value "47K")
      (footprint "eagle-import:R0805")
      (libsource (lib "eagle-import") (part "R-EU_R0805"))
    )
    (comp (ref "R106")
      (value "5K6")
      (footprint "eagle-import:R0805")
      (libsource (lib "eagle-import") (part "R-EU_R0805"))
    )
    (comp (ref "R107")
      (value "330R")
      (footprint "eagle-import:R0805")
      (libsource (lib "eagle-import") (part "R-EU_R0805"))
    )
    (comp (ref "R108")
      (value "750R")
      (footprint "eagle-import:R0805")
      (libsource (lib "eagle-import") (part "R-EU_R0805"))
    )
    (comp (ref "R109")
      (value "1K")
      (footprint "eagle-import:R0805")
      (libsource (lib "eagle-import") (part "R-EU_R0805"))
    )
    (comp (ref "R110")
      (value "AC01000001007JA100")
      (footprint "eagle-import:0411_15")
      (libsource (lib "eagle-import") (part "R-EU_0411/15"))
    )
    (comp (ref "R111")
      (value "2K2")
      (footprint "eagle-import:R0805")
      (libsource (lib "eagle-import") (part "R-EU_R0805"))
    )
    (comp (ref "R112")
      (value "330R")
      (footprint "eagle-import:R0805")
      (libsource (lib "eagle-import") (part "R-EU_R0805"))
    )
    (comp (ref "R113")
      (value "10K")
      (footprint "eagle-import:R0805")
      (libsource (lib "eagle-import") (part "R-EU_R0805"))
    )
    (comp (ref "R114")
      (value "1K")
      (footprint "eagle-import:R0805")
      (libsource (lib "eagle-import") (part "R-EU_R0805"))
    )
    (comp (ref "R115")
      (value "10K")
      (footprint "eagle-import:R0805")
      (libsource (lib "eagle-import") (part "R-EU_R0805"))
    )
    (comp (ref "R116")
      (value "6R8")
      (footprint "eagle-import:R0805")
      (libsource (lib "eagle-import") (part "R-EU_R0805"))
    )
    (comp (ref "R117")
      (value "10K")
      (footprint "eagle-import:R0805")
      (libsource (lib "eagle-import") (part "R-EU_R0805"))
    )
    (comp (ref "R118")
      (value "5K1")
      (footprint "eagle-import:R0805")
      (libsource (lib "eagle-import") (part "R-EU_R0805"))
    )
    (comp (ref "R119")
      (value "10K")
      (footprint "eagle-import:R0805")
      (libsource (lib "eagle-import") (part "R-EU_R0805"))
    )
    (comp (ref "R120")
      (value "5K6")
      (footprint "eagle-import:R0805")
      (libsource (lib "eagle-import") (part "R-EU_R0805"))
    )
    (comp (ref "R121")
      (value "10K")
      (footprint "eagle-import:R0805")
      (libsource (lib "eagle-import") (part "R-EU_R0805"))
    )
    (comp (ref "R122")
      (value "1K")
      (footprint "eagle-import:R0805")
      (libsource (lib "eagle-import") (part "R-EU_R0805"))
    )
    (comp (ref "C69")
      (value "10n")
      (footprint "eagle-import:C0805")
      (libsource (lib "eagle-import") (part "C-EUC0805"))
    )
    (comp (ref "C70")
      (value "10n/200V")
      (footprint "eagle-import:C1206")
      (libsource (lib "eagle-import") (part "C-EUC1206"))
    )
    (comp (ref "C71")
      (value "2n2")
      (footprint "eagle-import:C0805")
      (libsource (lib "eagle-import") (part "C-EUC0805"))
    )
    (comp (ref "C72")
      (value "470n")
      (footprint "eagle-import:C1206")
      (libsource (lib "eagle-import") (part "C-EUC1206"))
    )
    (comp (ref "C73")
      (value "HHXC630ARA330MHA0G")
      (footprint "eagle-import:CAPAE830X1050N")
      (libsource (lib "eagle-import") (part "ECAPSMD8.3MM/HA0"))
    )
    (comp (ref "C74")
      (value "10n/200V")
      (footprint "eagle-import:C1206")
      (libsource (lib "eagle-import") (part "C-EUC1206"))
    )
    (comp (ref "C75")
      (value "10n")
      (footprint "eagle-import:C0805")
      (libsource (lib "eagle-import") (part "C-EUC0805"))
    )
    (comp (ref "D20")
      (value "SK10100D1-DIO")
      (footprint "eagle-import:TO252-L")
      (libsource (lib "eagle-import") (part "SCHOTTKY-DUAL_A_L"))
    )
    (comp (ref "D21")
      (value "BAS316")
      (footprint "eagle-import:SOD323-R")
      (libsource (lib "eagle-import") (part "DIODESOD323R"))
    )
    (comp (ref "D22")
      (value "BAS316")
      (footprint "eagle-import:SOD323-R")
      (libsource (lib "eagle-import") (part "DIODESOD323R"))
    )
    (comp (ref "D23")
      (value "BAS316")
      (footprint "eagle-import:SOD323-R")
      (libsource (lib "eagle-import") (part "DIODESOD323R"))
    )
    (comp (ref "F1")
      (value "ZH32")
      (footprint "eagle-import:ZH32")
      (libsource (lib "eagle-import") (part "ZH32"))
    )
    (comp (ref "F2")
      (value "ZH32")
      (footprint "eagle-import:ZH32")
      (libsource (lib "eagle-import") (part "ZH32"))
    )
    (comp (ref "J1")
      (value "FCR7350R")
      (footprint "eagle-import:S16N-PC")
      (libsource (lib "eagle-import") (part "BINDING_POSTCLIFF"))
    )
    (comp (ref "J2")
      (value "FCR7350B")
      (footprint "eagle-import:S16N-PC")
      (libsource (lib "eagle-import") (part "BINDING_POSTCLIFF"))
    )
    (comp (ref "K1")
      (value "G6K-2F-5DC")
      (footprint "eagle-import:G6K-2F")
      (fields
        (field (name "MF") "OMRON COMPONENTS USA")
        (field (name "MPN") "G6K-2F DC24")
        (field (name "MF_1") "OMRON COMPONENTS USA")
        (field (name "MPN_1") "G6K-2F DC24")
        (field (name "OC_FARNELL") "1690427")
        (field (name "OC_NEWARK") "36K7467")
      )
      (libsource (lib "eagle-import") (part "G6K-2F"))
    )
    (comp (ref "LED2")
      (value "L-934EB/2ID")
      (footprint "eagle-import:L-934EB")
      (libsource (lib "eagle-import") (part "LED_L-934EB/2ID"))
    )
    (comp (ref "LED4")
      (value "OSY5LU3E34X-3F1A")
      (footprint "eagle-import:OSG8")
      (libsource (lib "eagle-import") (part "LEDOSG8"))
    )
    (comp (ref "Q26")
      (value "MMBT5551")
      (footprint "eagle-import:SOT23-BEC")
      (libsource (lib "eagle-import") (part "-NPN-SOT23-BECMMBT5551LT1"))
    )
    (comp (ref "Q27")
      (value "MMBT5401")
      (footprint "eagle-import:SOT23-BEC")
      (libsource (lib "eagle-import") (part "-PNP-SOT23-BECBC857B"))
    )
    (comp (ref "Q28")
      (value "MMBT5551")
      (footprint "eagle-import:SOT23-BEC")
      (libsource (lib "eagle-import") (part "-NPN-SOT23-BECMMBT5551LT1"))
    )
    (comp (ref "Q29")
      (value "MMBT5551")
      (footprint "eagle-import:SOT23-BEC")
      (libsource (lib "eagle-import") (part "-NPN-SOT23-BECMMBT5551LT1"))
    )
    (comp (ref "Q30")
      (value "BSS84P")
      (footprint "eagle-import:SOT95P237X112-3N")
      (fields (field (name "MPN") "IRLML2246TRPBF"))
      (libsource (lib "eagle-import") (part "IRLML2246TRPBF"))
    )
    (comp (ref "Q31")
      (value "2N7002")
      (footprint "eagle-import:SOT103P240X110-3N")
      (fields
        (field (name "MPN") "2N7002-7-F")
        (field (name "MPN_1") "2N7002-7-F")
        (field (name "OC_FARNELL") "1713823")
        (field (name "OC_NEWARK") "25R5679")
        (field (name "PACKAGE") "SOT-23-3")
        (field (name "SUPPLIER") "DIODES INC.")
      )
      (libsource (lib "eagle-import") (part "2N7002"))
    )
    (comp (ref "R123")
      (value "330R")
      (footprint "eagle-import:R0805")
      (libsource (lib "eagle-import") (part "R-EU_R0805"))
    )
    (comp (ref "R124")
      (value "47K")
      (footprint "eagle-import:R0805")
      (libsource (lib "eagle-import") (part "R-EU_R0805"))
    )
    (comp (ref "R125")
      (value "47K")
      (footprint "eagle-import:R0805")
      (libsource (lib "eagle-import") (part "R-EU_R0805"))
    )
    (comp (ref "R126")
      (value "750R")
      (footprint "eagle-import:R0805")
      (libsource (lib "eagle-import") (part "R-EU_R0805"))
    )
    (comp (ref "R127")
      (value "1K")
      (footprint "eagle-import:R0805")
      (libsource (lib "eagle-import") (part "R-EU_R0805"))
    )
    (comp (ref "R128")
      (value "2K2")
      (footprint "eagle-import:R0805")
      (libsource (lib "eagle-import") (part "R-EU_R0805"))
    )
    (comp (ref "R129")
      (value "10K")
      (footprint "eagle-import:R0805")
      (libsource (lib "eagle-import") (part "R-EU_R0805"))
    )
    (comp (ref "R130")
      (value "10K")
      (footprint "eagle-import:R0805")
      (libsource (lib "eagle-import") (part "R-EU_R0805"))
    )
    (comp (ref "R131")
      (value "1R")
      (footprint "eagle-import:R0805")
      (libsource (lib "eagle-import") (part "R-EU_R0805"))
    )
    (comp (ref "R132")
      (value "750R")
      (footprint "eagle-import:R0805")
      (libsource (lib "eagle-import") (part "R-EU_R0805"))
    )
    (comp (ref "R133")
      (value "47K")
      (footprint "eagle-import:R0805")
      (libsource (lib "eagle-import") (part "R-EU_R0805"))
    )
    (comp (ref "R134")
      (value "330R")
      (footprint "eagle-import:R0805")
      (libsource (lib "eagle-import") (part "R-EU_R0805"))
    )
    (comp (ref "R135")
      (value "470R")
      (footprint "eagle-import:R0805")
      (libsource (lib "eagle-import") (part "R-EU_R0805"))
    )
    (comp (ref "R136")
      (value "10K")
      (footprint "eagle-import:R0805")
      (libsource (lib "eagle-import") (part "R-EU_R0805"))
    )
    (comp (ref "R137")
      (value "470R")
      (footprint "eagle-import:R0805")
      (libsource (lib "eagle-import") (part "R-EU_R0805"))
    )
    (comp (ref "R138")
      (value "100K")
      (footprint "eagle-import:R0805")
      (libsource (lib "eagle-import") (part "R-EU_R0805"))
    )
    (comp (ref "X4")
      (value "1844249")
      (footprint "eagle-import:MC1,5_5-G-3,5")
      (libsource (lib "eagle-import") (part "MC1,5/5-G-3,5"))
    )
    (comp (ref "X5")
      (value "ZL263-20DG")
      (footprint "eagle-import:SSW-110-02-T-D-RA")
      (libsource (lib "eagle-import") (part "SSW-110-02-T-D-RA"))
    )
    (comp (ref "C45")
      (value "100n")
      (footprint "eagle-import:C0603")
      (libsource (lib "eagle-import") (part "C-EUC0603"))
    )
    (comp (ref "C46")
      (value "100n")
      (footprint "eagle-import:C0603")
      (libsource (lib "eagle-import") (part "C-EUC0603"))
    )
    (comp (ref "C47")
      (value "1u")
      (footprint "eagle-import:C0805")
      (libsource (lib "eagle-import") (part "C-EUC0805"))
    )
    (comp (ref "C48")
      (value "10u")
      (footprint "eagle-import:C1206")
      (libsource (lib "eagle-import") (part "C-EUC1206"))
    )
    (comp (ref "C49")
      (value "100n")
      (footprint "eagle-import:C0603")
      (libsource (lib "eagle-import") (part "C-EUC0603"))
    )
    (comp (ref "C50")
      (value "4u7")
      (footprint "eagle-import:EC1206")
      (libsource (lib "eagle-import") (part "ECAP1206"))
    )
    (comp (ref "C51")
      (value "1u")
      (footprint "eagle-import:C0805")
      (libsource (lib "eagle-import") (part "C-EUC0805"))
    )
    (comp (ref "C52")
      (value "100n")
      (footprint "eagle-import:C0603")
      (libsource (lib "eagle-import") (part "C-EUC0603"))
    )
    (comp (ref "C53")
      (value "3n3")
      (footprint "eagle-import:C0805")
      (libsource (lib "eagle-import") (part "C-EUC0805"))
    )
    (comp (ref "C54")
      (value "3n3")
      (footprint "eagle-import:C0805")
      (libsource (lib "eagle-import") (part "C-EUC0805"))
    )
    (comp (ref "C55")
      (value "10n")
      (footprint "eagle-import:C0805")
      (libsource (lib "eagle-import") (part "C-EUC0805"))
    )
    (comp (ref "C56")
      (value "3n3")
      (footprint "eagle-import:C0805")
      (libsource (lib "eagle-import") (part "C-EUC0805"))
    )
    (comp (ref "C57")
      (value "3n3")
      (footprint "eagle-import:C0805")
      (libsource (lib "eagle-import") (part "C-EUC0805"))
    )
    (comp (ref "C58")
      (value "100n")
      (footprint "eagle-import:C0603")
      (libsource (lib "eagle-import") (part "C-EUC0603"))
    )
    (comp (ref "C59")
      (value "1u")
      (footprint "eagle-import:C0805")
      (libsource (lib "eagle-import") (part "C-EUC0805"))
    )
    (comp (ref "C60")
      (value "100n")
      (footprint "eagle-import:C0603")
      (libsource (lib "eagle-import") (part "C-EUC0603"))
    )
    (comp (ref "C61")
      (value "1u")
      (footprint "eagle-import:C0805")
      (libsource (lib "eagle-import") (part "C-EUC0805"))
    )
    (comp (ref "C62")
      (value "100n")
      (footprint "eagle-import:C0603")
      (libsource (lib "eagle-import") (part "C-EUC0603"))
    )
    (comp (ref "D17")
      (value "BAS316")
      (footprint "eagle-import:SOD323-R")
      (libsource (lib "eagle-import") (part "DIODESOD323R"))
    )
    (comp (ref "IC14")
      (value "74AUP1G74DC.125")
      (footprint "eagle-import:DCU8")
      (libsource (lib "eagle-import") (part "SN74LVC1G74DCTR-VSSOP"))
    )
    (comp (ref "IC15")
      (value "MCP23S17-E/SS")
      (footprint "eagle-import:SOP65P780X200-28N")
      (libsource (lib "eagle-import") (part "MCP23S17-E/SSSSOP"))
    )
    (comp (ref "IC16")
      (value "REF5025AIDR")
      (footprint "eagle-import:SOIC127P600X175-8N")
      (libsource (lib "eagle-import") (part "REF50XX"))
    )
    (comp (ref "IC17")
      (value "DAC8552IDGKR")
      (footprint "eagle-import:DGK8-M")
      (libsource (lib "eagle-import") (part "DAC8552_DGK_8M"))
    )
    (comp (ref "IC18")
      (value "SN74LVC1G3157DCKR")
      (footprint "eagle-import:SOT65P210X110-6N")
      (libsource (lib "eagle-import") (part "SN74LVC1G3157-DCK"))
    )
    (comp (ref "IC19")
      (value "ADS1120IPWR")
      (footprint "eagle-import:PW(R-PDSO-G16)")
      (libsource (lib "eagle-import") (part "ADS1120TSSOP-16"))
    )
    (comp (ref "JP3")
      (value "JP2-CUT")
      (footprint "eagle-import:JP2-CUT")
      (libsource (lib "eagle-import") (part "JP2-CUT"))
    )
    (comp (ref "JP4")
      (value "JP3-CUT")
      (footprint "eagle-import:JP3-CUT")
      (libsource (lib "eagle-import") (part "JP3-CUT"))
    )
    (comp (ref "LED1")
      (value "L-42WUM/1EGWT")
      (footprint "eagle-import:L-42WUM-1EGWT")
      (libsource (lib "eagle-import") (part "LED_L-42WUM/1EGWT"))
    )
    (comp (ref "Q18")
      (value "2N7002")
      (footprint "eagle-import:SOT103P240X110-3N")
      (fields
        (field (name "MPN") "2N7002-7-F")
        (field (name "MPN_1") "2N7002-7-F")
        (field (name "OC_FARNELL") "1713823")
        (field (name "OC_NEWARK") "25R5679")
        (field (name "PACKAGE") "SOT-23-3")
        (field (name "SUPPLIER") "DIODES INC.")
      )
      (libsource (lib "eagle-import") (part "2N7002"))
    )
    (comp (ref "Q19")
      (value "BSS84P")
      (footprint "eagle-import:SOT95P237X112-3N")
      (fields (field (name "MPN") "IRLML2246TRPBF"))
      (libsource (lib "eagle-import") (part "IRLML2246TRPBF"))
    )
    (comp (ref "R87")
      (value "10K")
      (footprint "eagle-import:R0805")
      (libsource (lib "eagle-import") (part "R-EU_R0805"))
    )
    (comp (ref "R88")
      (value "100K")
      (footprint "eagle-import:R0805")
      (libsource (lib "eagle-import") (part "R-EU_R0805"))
    )
    (comp (ref "R89")
      (value "270R")
      (footprint "eagle-import:R0805")
      (libsource (lib "eagle-import") (part "R-EU_R0805"))
    )
    (comp (ref "R90")
      (value "47K")
      (footprint "eagle-import:R0805")
      (libsource (lib "eagle-import") (part "R-EU_R0805"))
    )
    (comp (ref "R91")
      (value "100K")
      (footprint "eagle-import:R0805")
      (libsource (lib "eagle-import") (part "R-EU_R0805"))
    )
    (comp (ref "R92")
      (value "470R")
      (footprint "eagle-import:R0805")
      (libsource (lib "eagle-import") (part "R-EU_R0805"))
    )
    (comp (ref "R93")
      (value "10K")
      (footprint "eagle-import:R0805")
      (libsource (lib "eagle-import") (part "R-EU_R0805"))
    )
    (comp (ref "R94")
      (value "220R")
      (footprint "eagle-import:R0805")
      (libsource (lib "eagle-import") (part "R-EU_R0805"))
    )
    (comp (ref "R95")
      (value "220R")
      (footprint "eagle-import:R0805")
      (libsource (lib "eagle-import") (part "R-EU_R0805"))
    )
    (comp (ref "R96")
      (value "470R")
      (footprint "eagle-import:R0805")
      (libsource (lib "eagle-import") (part "R-EU_R0805"))
    )
    (comp (ref "R97")
      (value "470R")
      (footprint "eagle-import:R0805")
      (libsource (lib "eagle-import") (part "R-EU_R0805"))
    )
    (comp (ref "R98")
      (value "220R")
      (footprint "eagle-import:R0805")
      (libsource (lib "eagle-import") (part "R-EU_R0805"))
    )
    (comp (ref "R99")
      (value "220R")
      (footprint "eagle-import:R0805")
      (libsource (lib "eagle-import") (part "R-EU_R0805"))
    )
    (comp (ref "R100")
      (value "10R")
      (footprint "eagle-import:R0805")
      (libsource (lib "eagle-import") (part "R-EU_R0805"))
    )
    (comp (ref "ZD3")
      (value "SLVU2.8-TP")
      (footprint "eagle-import:SOT23")
      (libsource (lib "eagle-import") (part "SLVU2.8"))
    )
    (comp (ref "C18")
      (value "47n")
      (footprint "eagle-import:C1206")
      (libsource (lib "eagle-import") (part "C-EUC1206"))
    )
    (comp (ref "C19")
      (value "47n")
      (footprint "eagle-import:C1206")
      (libsource (lib "eagle-import") (part "C-EUC1206"))
    )
    (comp (ref "C20")
      (value "100n")
      (footprint "eagle-import:C0603")
      (libsource (lib "eagle-import") (part "C-EUC0603"))
    )
    (comp (ref "C21")
      (value "1u/100V")
      (footprint "eagle-import:C1206")
      (libsource (lib "eagle-import") (part "C-EUC1206"))
    )
    (comp (ref "C22")
      (value "47p")
      (footprint "eagle-import:C0805")
      (libsource (lib "eagle-import") (part "C-EUC0805"))
    )
    (comp (ref "C23")
      (value "10n")
      (footprint "eagle-import:C0805")
      (libsource (lib "eagle-import") (part "C-EUC0805"))
    )
    (comp (ref "C24")
      (value "2n2")
      (footprint "eagle-import:C0805")
      (libsource (lib "eagle-import") (part "C-EUC0805"))
    )
    (comp (ref "C25")
      (value "2n2")
      (footprint "eagle-import:C0805")
      (libsource (lib "eagle-import") (part "C-EUC0805"))
    )
    (comp (ref "C26")
      (value "2n2")
      (footprint "eagle-import:C0805")
      (libsource (lib "eagle-import") (part "C-EUC0805"))
    )
    (comp (ref "C27")
      (value "220p")
      (footprint "eagle-import:C0805")
      (libsource (lib "eagle-import") (part "C-EUC0805"))
    )
    (comp (ref "C28")
      (value "47p")
      (footprint "eagle-import:C0805")
      (libsource (lib "eagle-import") (part "C-EUC0805"))
    )
    (comp (ref "C29")
      (value "2n2")
      (footprint "eagle-import:C0805")
      (libsource (lib "eagle-import") (part "C-EUC0805"))
    )
    (comp (ref "C30")
      (value "100n")
      (footprint "eagle-import:C0603")
      (libsource (lib "eagle-import") (part "C-EUC0603"))
    )
    (comp (ref "C31")
      (value "100n")
      (footprint "eagle-import:C0603")
      (libsource (lib "eagle-import") (part "C-EUC0603"))
    )
    (comp (ref "C32")
      (value "1n")
      (footprint "eagle-import:C0805")
      (libsource (lib "eagle-import") (part "C-EUC0805"))
    )
    (comp (ref "C33")
      (value "100n")
      (footprint "eagle-import:C0603")
      (libsource (lib "eagle-import") (part "C-EUC0603"))
    )
    (comp (ref "C34")
      (value "100n")
      (footprint "eagle-import:C0603")
      (libsource (lib "eagle-import") (part "C-EUC0603"))
    )
    (comp (ref "C35")
      (value "1n")
      (footprint "eagle-import:C0805")
      (libsource (lib "eagle-import") (part "C-EUC0805"))
    )
    (comp (ref "D5")
      (value "BAS316")
      (footprint "eagle-import:SOD323-R")
      (libsource (lib "eagle-import") (part "DIODESOD323R"))
    )
    (comp (ref "D6")
      (value "BAS316")
      (footprint "eagle-import:SOD323-R")
      (libsource (lib "eagle-import") (part "DIODESOD323R"))
    )
    (comp (ref "D7")
      (value "BAS316")
      (footprint "eagle-import:SOD323-R")
      (libsource (lib "eagle-import") (part "DIODESOD323R"))
    )
    (comp (ref "D8")
      (value "BAS316")
      (footprint "eagle-import:SOD323-R")
      (libsource (lib "eagle-import") (part "DIODESOD323R"))
    )
    (comp (ref "D9")
      (value "BAS316")
      (footprint "eagle-import:SOD323-R")
      (libsource (lib "eagle-import") (part "DIODESOD323R"))
    )
    (comp (ref "D10")
      (value "BAS316")
      (footprint "eagle-import:SOD323-R")
      (libsource (lib "eagle-import") (part "DIODESOD323R"))
    )
    (comp (ref "D11")
      (value "BAS316")
      (footprint "eagle-import:SOD323-R")
      (libsource (lib "eagle-import") (part "DIODESOD323R"))
    )
    (comp (ref "D12")
      (value "BAS316")
      (footprint "eagle-import:SOD323-R")
      (libsource (lib "eagle-import") (part "DIODESOD323R"))
    )
    (comp (ref "D13")
      (value "BAS316")
      (footprint "eagle-import:SOD323-R")
      (libsource (lib "eagle-import") (part "DIODESOD323R"))
    )
    (comp (ref "FB6")
      (value "BLM41PG600SN1L")
      (footprint "eagle-import:L1812")
      (libsource (lib "eagle-import") (part "L-EUL1812"))
    )
    (comp (ref "FB7")
      (value "BLM41PG600SN1L")
      (footprint "eagle-import:L1812")
      (libsource (lib "eagle-import") (part "L-EUL1812"))
    )
    (comp (ref "FB8")
      (value "BLM18AG102SH1D")
      (footprint "eagle-import:BEAD0603")
      (libsource (lib "eagle-import") (part "EEZ_inductors_and_transformers_FERRITE_BEAD0603"))
    )
    (comp (ref "IC8")
      (value "TL072D")
      (footprint "eagle-import:SOIC127P600X173-8N")
      (libsource (lib "eagle-import") (part "TL072SOIC8"))
    )
    (comp (ref "IC9")
      (value "MC33274ADR2G")
      (footprint "eagle-import:SOIC127P600X173-8N")
      (libsource (lib "eagle-import") (part "TL072SOIC8"))
    )
    (comp (ref "Q1")
      (value "IRFP250MPBF")
      (footprint "eagle-import:TO247BH-CLR2")
      (libsource (lib "eagle-import") (part "IRFP240MIRROR2"))
    )
    (comp (ref "Q2")
      (value "BCP56-16.115")
      (footprint "eagle-import:SOT230P700X180-4N")
      (libsource (lib "eagle-import") (part "BCP56"))
    )
    (comp (ref "Q3")
      (value "BC856C")
      (footprint "eagle-import:SOT23-BEC")
      (libsource (lib "eagle-import") (part "-PNP-SOT23-BECBC857C"))
    )
    (comp (ref "Q4")
      (value "BCP56-16.115")
      (footprint "eagle-import:SOT230P700X180-4N")
      (libsource (lib "eagle-import") (part "BCP56"))
    )
    (comp (ref "Q5")
      (value "STF10P6F6")
      (footprint "eagle-import:TO220H-CLR2")
      (libsource (lib "eagle-import") (part "P-MOSFETMIRROR2"))
    )
    (comp (ref "Q6")
      (value "BCP56-16.115")
      (footprint "eagle-import:SOT230P700X180-4N")
      (libsource (lib "eagle-import") (part "BCP56"))
    )
    (comp (ref "Q7")
      (value "MMBT5401")
      (footprint "eagle-import:SOT23-BEC")
      (libsource (lib "eagle-import") (part "-PNP-SOT23-BECBC857B"))
    )
    (comp (ref "Q8")
      (value "MMBT5401")
      (footprint "eagle-import:SOT23-BEC")
      (libsource (lib "eagle-import") (part "-PNP-SOT23-BECBC857B"))
    )
    (comp (ref "Q9")
      (value "MMBT5551")
      (footprint "eagle-import:SOT23-BEC")
      (libsource (lib "eagle-import") (part "-NPN-SOT23-BECMMBT5551LT1"))
    )
    (comp (ref "Q10")
      (value "MMBT5551")
      (footprint "eagle-import:SOT23-BEC")
      (libsource (lib "eagle-import") (part "-NPN-SOT23-BECMMBT5551LT1"))
    )
    (comp (ref "R10")
      (value "1K")
      (footprint "eagle-import:R0805")
      (libsource (lib "eagle-import") (part "R-EU_R0805"))
    )
    (comp (ref "R11")
      (value "3R9/2W")
      (footprint "eagle-import:R2512")
      (libsource (lib "eagle-import") (part "R-EU_R2512"))
    )
    (comp (ref "R12")
      (value "3R9/2W")
      (footprint "eagle-import:R2512")
      (libsource (lib "eagle-import") (part "R-EU_R2512"))
    )
    (comp (ref "R13")
      (value "750R")
      (footprint "eagle-import:R0805")
      (libsource (lib "eagle-import") (part "R-EU_R0805"))
    )
    (comp (ref "R14")
      (value "10K")
      (footprint "eagle-import:R0805")
      (libsource (lib "eagle-import") (part "R-EU_R0805"))
    )
    (comp (ref "R15")
      (value "2K2")
      (footprint "eagle-import:R0805")
      (libsource (lib "eagle-import") (part "R-EU_R0805"))
    )
    (comp (ref "R16")
      (value "2K2")
      (footprint "eagle-import:R0805")
      (libsource (lib "eagle-import") (part "R-EU_R0805"))
    )
    (comp (ref "R17")
      (value "220R")
      (footprint "eagle-import:R0805")
      (libsource (lib "eagle-import") (part "R-EU_R0805"))
    )
    (comp (ref "R18")
      (value "16K")
      (footprint "eagle-import:R0805")
      (libsource (lib "eagle-import") (part "R-EU_R0805"))
    )
    (comp (ref "R19")
      (value "220R")
      (footprint "eagle-import:R0805")
      (libsource (lib "eagle-import") (part "R-EU_R0805"))
    )
    (comp (ref "R20")
      (value "220R")
      (footprint "eagle-import:R0805")
      (libsource (lib "eagle-import") (part "R-EU_R0805"))
    )
    (comp (ref "R21")
      (value "470R")
      (footprint "eagle-import:R0805")
      (libsource (lib "eagle-import") (part "R-EU_R0805"))
    )
    (comp (ref "R22")
      (value "100R")
      (footprint "eagle-import:R0805")
      (libsource (lib "eagle-import") (part "R-EU_R0805"))
    )
    (comp (ref "R23")
      (value "1K")
      (footprint "eagle-import:R0805")
      (libsource (lib "eagle-import") (part "R-EU_R0805"))
    )
    (comp (ref "R24")
      (value "7K5 0.1%")
      (footprint "eagle-import:R0805")
      (libsource (lib "eagle-import") (part "R-EU_R0805"))
    )
    (comp (ref "R25")
      (value "10K")
      (footprint "eagle-import:R0805")
      (libsource (lib "eagle-import") (part "R-EU_R0805"))
    )
    (comp (ref "R26")
      (value "220R")
      (footprint "eagle-import:R0805")
      (libsource (lib "eagle-import") (part "R-EU_R0805"))
    )
    (comp (ref "R27")
      (value "2K2")
      (footprint "eagle-import:R0805")
      (libsource (lib "eagle-import") (part "R-EU_R0805"))
    )
    (comp (ref "R28")
      (value "750R")
      (footprint "eagle-import:R0805")
      (libsource (lib "eagle-import") (part "R-EU_R0805"))
    )
    (comp (ref "R29")
      (value "130K 0.1%")
      (footprint "eagle-import:R0805")
      (libsource (lib "eagle-import") (part "R-EU_R0805"))
    )
    (comp (ref "R30")
      (value "24K 0.1%")
      (footprint "eagle-import:R0805")
      (libsource (lib "eagle-import") (part "R-EU_R0805"))
    )
    (comp (ref "R31")
      (value "51K")
      (footprint "eagle-import:R0805")
      (libsource (lib "eagle-import") (part "R-EU_R0805"))
    )
    (comp (ref "R32")
      (value "220R")
      (footprint "eagle-import:R0805")
      (libsource (lib "eagle-import") (part "R-EU_R0805"))
    )
    (comp (ref "R33")
      (value "10K")
      (footprint "eagle-import:R0805")
      (libsource (lib "eagle-import") (part "R-EU_R0805"))
    )
    (comp (ref "R34")
      (value "470R")
      (footprint "eagle-import:R0805")
      (libsource (lib "eagle-import") (part "R-EU_R0805"))
    )
    (comp (ref "R35")
      (value "1K8")
      (footprint "eagle-import:R0805")
      (libsource (lib "eagle-import") (part "R-EU_R0805"))
    )
    (comp (ref "R36")
      (value "10K")
      (footprint "eagle-import:R0805")
      (libsource (lib "eagle-import") (part "R-EU_R0805"))
    )
    (comp (ref "R37")
      (value "7K5 0.1%")
      (footprint "eagle-import:R0805")
      (libsource (lib "eagle-import") (part "R-EU_R0805"))
    )
    (comp (ref "R38")
      (value "130K 0.1%")
      (footprint "eagle-import:R0805")
      (libsource (lib "eagle-import") (part "R-EU_R0805"))
    )
    (comp (ref "R39")
      (value "24K 0.1%")
      (footprint "eagle-import:R0805")
      (libsource (lib "eagle-import") (part "R-EU_R0805"))
    )
    (comp (ref "R40")
      (value "10K")
      (footprint "eagle-import:R0805")
      (libsource (lib "eagle-import") (part "R-EU_R0805"))
    )
    (comp (ref "R41")
      (value "220R")
      (footprint "eagle-import:R0805")
      (libsource (lib "eagle-import") (part "R-EU_R0805"))
    )
    (comp (ref "R42")
      (value "2K2")
      (footprint "eagle-import:R0805")
      (libsource (lib "eagle-import") (part "R-EU_R0805"))
    )
    (comp (ref "R43")
      (value "10K")
      (footprint "eagle-import:R0805")
      (libsource (lib "eagle-import") (part "R-EU_R0805"))
    )
    (comp (ref "R44")
      (value "1K")
      (footprint "eagle-import:R0805")
      (libsource (lib "eagle-import") (part "R-EU_R0805"))
    )
    (comp (ref "R45")
      (value "10K")
      (footprint "eagle-import:R0805")
      (libsource (lib "eagle-import") (part "R-EU_R0805"))
    )
    (comp (ref "R46")
      (value "10K")
      (footprint "eagle-import:R0805")
      (libsource (lib "eagle-import") (part "R-EU_R0805"))
    )
    (comp (ref "SH1")
      (value "SHORTNOHOLE")
      (footprint "eagle-import:SHORT_NOHOLE")
      (libsource (lib "eagle-import") (part "SHORTNOHOLE"))
    )
    (comp (ref "SH2")
      (value "SHORTNOHOLE")
      (footprint "eagle-import:SHORT_NOHOLE")
      (libsource (lib "eagle-import") (part "SHORTNOHOLE"))
    )
    (comp (ref "X3")
      (value "39-30-3035")
      (footprint "eagle-import:MINIFIT_6659-3")
      (libsource (lib "eagle-import") (part "MINIFIT_6659-3"))
    )
    (comp (ref "ZD1")
      (value "BZX384-C15")
      (footprint "eagle-import:SOD323-W")
      (libsource (lib "eagle-import") (part "ZENER-DIODESOD323"))
    )
    (comp (ref "ZD2")
      (value "PDZ6.2B")
      (footprint "eagle-import:SOD323-W")
      (libsource (lib "eagle-import") (part "ZENER-DIODESOD323"))
    )
  )
  (nets
    (net (code "1") (name "+3V3") (class "Default")
      (node (ref "C14") (pin "1") (pinfunction "1_1") (pintype "passive"))
      (node (ref "C16") (pin "2") (pinfunction "2_2") (pintype "passive"))
      (node (ref "C17") (pin "1") (pinfunction "1_1") (pintype "passive"))
      (node (ref "C6") (pin "1") (pinfunction "1_1") (pintype "passive"))
      (node (ref "IC2") (pin "1") (pinfunction "VDD1_1") (pintype "passive"))
      (node (ref "IC2") (pin "7") (pinfunction "EN1_7") (pintype "input"))
      (node (ref "IC5") (pin "1") (pinfunction "VDD1_1") (pintype "passive"))
      (node (ref "IC5") (pin "7") (pinfunction "EN1_7") (pintype "input"))
      (node (ref "IC6") (pin "8") (pinfunction "VCC_8") (pintype "power_in"))
      (node (ref "IC7") (pin "8") (pinfunction "V+_8") (pintype "passive"))
      (node (ref "R7") (pin "1") (pinfunction "1_1") (pintype "passive"))
      (node (ref "R8") (pin "1") (pinfunction "1_1") (pintype "passive"))
      (node (ref "R9") (pin "1") (pinfunction "1_1") (pintype "passive"))
      (node (ref "X1") (pin "1") (pinfunction "1_1") (pintype "passive"))
    )
    (net (code "2") (name "+5V") (class "Default")
      (node (ref "C15") (pin "2") (pinfunction "2_2") (pintype "passive"))
      (node (ref "C45") (pin "1") (pinfunction "1_1") (pintype "passive"))
      (node (ref "C46") (pin "2") (pinfunction "2_2") (pintype "passive"))
      (node (ref "C58") (pin "2") (pinfunction "2_2") (pintype "passive"))
      (node (ref "C59") (pin "2") (pinfunction "2_2") (pintype "passive"))
      (node (ref "C7") (pin "2") (pinfunction "2_2") (pintype "passive"))
      (node (ref "C8") (pin "1") (pinfunction "1_1") (pintype "passive"))
      (node (ref "D21") (pin "C") (pinfunction "C_C") (pintype "passive"))
      (node (ref "FB3") (pin "P$2") (pinfunction "2_P$2") (pintype "passive"))
      (node (ref "IC14") (pin "7") (pinfunction "~{PRE}_7") (pintype "input"))
      (node (ref "IC14") (pin "8") (pinfunction "VDD_8") (pintype "power_in"))
      (node (ref "IC15") (pin "9") (pinfunction "VDD_9") (pintype "power_in"))
      (node (ref "IC19") (pin "13") (pinfunction "DVDD_13") (pintype "power_in"))
      (node (ref "IC2") (pin "10") (pinfunction "EN2_10") (pintype "input"))
      (node (ref "IC2") (pin "16") (pinfunction "VDD2_16") (pintype "passive"))
      (node (ref "IC3") (pin "8") (pinfunction "VCC_8") (pintype "passive"))
      (node (ref "IC5") (pin "10") (pinfunction "EN2_10") (pintype "input"))
      (node (ref "IC5") (pin "16") (pinfunction "VDD2_16") (pintype "passive"))
      (node (ref "K1") (pin "1") (pinfunction "+_1") (pintype "passive"))
      (node (ref "LED2") (pin "BA") (pinfunction "A_BA") (pintype "passive"))
      (node (ref "LED3") (pin "BA") (pinfunction "A_BA") (pintype "passive"))
      (node (ref "LED3") (pin "TA") (pinfunction "A_TA") (pintype "passive"))
      (node (ref "Q10") (pin "B") (pinfunction "B_B") (pintype "passive"))
      (node (ref "Q19") (pin "2") (pinfunction "S_2") (pintype "passive"))
      (node (ref "R104") (pin "2") (pinfunction "2_2") (pintype "passive"))
      (node (ref "R118") (pin "2") (pinfunction "2_2") (pintype "passive"))
      (node (ref "R129") (pin "2") (pinfunction "2_2") (pintype "passive"))
      (node (ref "R135") (pin "2") (pinfunction "2_2") (pintype "passive"))
      (node (ref "R136") (pin "1") (pinfunction "1_1") (pintype "passive"))
      (node (ref "R6") (pin "1") (pinfunction "1_1") (pintype "passive"))
      (node (ref "R87") (pin "1") (pinfunction "1_1") (pintype "passive"))
      (node (ref "R91") (pin "1") (pinfunction "1_1") (pintype "passive"))
    )
    (net (code "3") (name "+5VOUT") (class "Default")
      (node (ref "C5") (pin "+") (pinfunction "+_+") (pintype "passive"))
      (node (ref "D1") (pin "A") (pinfunction "A_A") (pintype "passive"))
      (node (ref "D2") (pin "C") (pinfunction "C_C") (pintype "passive"))
      (node (ref "FB2") (pin "P$1") (pinfunction "1_P$1") (pintype "passive"))
      (node (ref "FB3") (pin "P$1") (pinfunction "1_P$1") (pintype "passive"))
      (node (ref "IC1") (pin "1") (pinfunction "OUT_1") (pintype "output"))
      (node (ref "R4") (pin "1") (pinfunction "1_1") (pintype "passive"))
    )
    (net (code "4") (name "+6V") (class "Default")
      (node (ref "C2") (pin "1") (pinfunction "1_1") (pintype "passive"))
      (node (ref "C3") (pin "1") (pinfunction "1_1") (pintype "passive"))
      (node (ref "C4") (pin "1") (pinfunction "1_1") (pintype "passive"))
      (node (ref "D1") (pin "C") (pinfunction "C_C") (pintype "passive"))
      (node (ref "FB1") (pin "P$2") (pinfunction "2_P$2") (pintype "passive"))
      (node (ref "IC1") (pin "8") (pinfunction "IN_8") (pintype "power_in"))
    )
    (net (code "5") (name "+VAUX") (class "Default")
      (node (ref "X1") (pin "2") (pinfunction "1_2") (pintype "passive"))
    )
    (net (code "6") (name "+VREF") (class "Default")
      (node (ref "C50") (pin "+") (pinfunction "+_+") (pintype "passive"))
      (node (ref "C52") (pin "2") (pinfunction "2_2") (pintype "passive"))
      (node (ref "C62") (pin "2") (pinfunction "2_2") (pintype "passive"))
      (node (ref "IC16") (pin "6") (pinfunction "VOUT_6") (pintype "output"))
      (node (ref "IC17") (pin "2") (pinfunction "VREF_2") (pintype "input"))
      (node (ref "IC19") (pin "9") (pinfunction "REFP0_9") (pintype "input"))
      (node (ref "R14") (pin "1") (pinfunction "1_1") (pintype "passive"))
      (node (ref "R51") (pin "1") (pinfunction "1_1") (pintype "passive"))
      (node (ref "R78") (pin "2") (pinfunction "2_2") (pintype "passive"))
      (node (ref "R79") (pin "2") (pinfunction "2_2") (pintype "passive"))
      (node (ref "R85") (pin "2") (pinfunction "2_2") (pintype "passive"))
    )
    (net (code "7") (name "-5VOUT") (class "Default")
      (node (ref "C12") (pin "2") (pinfunction "2_2") (pintype "passive"))
      (node (ref "D3") (pin "A") (pinfunction "A_A") (pintype "passive"))
      (node (ref "D4") (pin "C") (pinfunction "C_C") (pintype "passive"))
      (node (ref "FB5") (pin "P$1") (pinfunction "1_P$1") (pintype "passive"))
      (node (ref "IC4") (pin "1") (pinfunction "OUT_1") (pintype "passive"))
    )
    (net (code "8") (name "-9V") (class "Default")
      (node (ref "C10") (pin "2") (pinfunction "2_2") (pintype "passive"))
      (node (ref "C11") (pin "2") (pinfunction "2_2") (pintype "passive"))
      (node (ref "C13") (pin "1") (pinfunction "1_1") (pintype "passive"))
      (node (ref "D4") (pin "A") (pinfunction "A_A") (pintype "passive"))
      (node (ref "FB4") (pin "P$2") (pinfunction "2_P$2") (pintype "passive"))
      (node (ref "IC4") (pin "2") (pinfunction "IN_2") (pintype "input"))
      (node (ref "IC4") (pin "3") (pinfunction "IN_3") (pintype "input"))
      (node (ref "IC4") (pin "6") (pinfunction "IN_6") (pintype "input"))
      (node (ref "IC4") (pin "7") (pinfunction "IN_7") (pintype "input"))
      (node (ref "R23") (pin "2") (pinfunction "2_2") (pintype "passive"))
      (node (ref "R26") (pin "2") (pinfunction "2_2") (pintype "passive"))
    )
    (net (code "9") (name "AUX_USET_SW") (class "Default")
      (node (ref "IC15") (pin "4") (pinfunction "GPB3_4") (pintype "bidirectional"))
      (node (ref "IC18") (pin "6") (pinfunction "CTRL_6") (pintype "input"))
      (node (ref "LED2") (pin "TA") (pinfunction "A_TA") (pintype "passive"))
      (node (ref "R90") (pin "2") (pinfunction "2_2") (pintype "passive"))
    )
    (net (code "10") (name "BIAS_IN+") (class "Default")
      (node (ref "FB8") (pin "P$1") (pinfunction "1_P$1") (pintype "passive"))
      (node (ref "X2") (pin "9") (pinfunction "1_9") (pintype "passive"))
    )
    (net (code "11") (name "CC_ACTIVE") (class "Default")
      (node (ref "IC15") (pin "22") (pinfunction "GPA1_22") (pintype "bidirectional"))
      (node (ref "Q24") (pin "1") (pinfunction "G_1") (pintype "passive"))
      (node (ref "R118") (pin "1") (pinfunction "1_1") (pintype "passive"))
      (node (ref "R120") (pin "2") (pinfunction "2_2") (pintype "passive"))
    )
    (net (code "12") (name "CSA") (class "Default")
      (node (ref "IC2") (pin "13") (pinfunction "B2_13") (pintype "output"))
      (node (ref "IC3") (pin "1") (pinfunction "A_1") (pintype "input"))
    )
    (net (code "13") (name "CSB") (class "Default")
      (node (ref "IC2") (pin "12") (pinfunction "B3_12") (pintype "output"))
      (node (ref "IC3") (pin "2") (pinfunction "B_2") (pintype "input"))
    )
    (net (code "14") (name "CS_ADC") (class "Default")
      (node (ref "IC19") (pin "2") (pinfunction "~{CS}_2") (pintype "input"))
      (node (ref "RN1") (pin "7") (pinfunction "2_7") (pintype "passive"))
    )
    (net (code "15") (name "CS_DAC") (class "Default")
      (node (ref "IC17") (pin "5") (pinfunction "~{SYNC}_5") (pintype "input"))
      (node (ref "RN1") (pin "8") (pinfunction "2_8") (pintype "passive"))
    )
    (net (code "16") (name "CS_IOEXP") (class "Default")
      (node (ref "IC15") (pin "11") (pinfunction "~{CS}_11") (pintype "input"))
      (node (ref "RN1") (pin "5") (pinfunction "2_5") (pintype "passive"))
    )
    (net (code "17") (name "CURR_5A") (class "Default")
      (node (ref "IC13") (pin "13") (pinfunction "E_13") (pintype "input"))
      (node (ref "IC15") (pin "5") (pinfunction "GPB4_5") (pintype "bidirectional"))
      (node (ref "Q11") (pin "4") (pinfunction "G_4") (pintype "passive"))
      (node (ref "Q14") (pin "1") (pinfunction "G_1") (pintype "passive"))
      (node (ref "Q17") (pin "E") (pinfunction "E_E") (pintype "passive"))
      (node (ref "R48") (pin "2") (pinfunction "2_2") (pintype "passive"))
    )
    (net (code "18") (name "CURR_50MA") (class "Default")
      (node (ref "D14") (pin "C") (pinfunction "C_C") (pintype "passive"))
      (node (ref "IC13") (pin "6") (pinfunction "E_6") (pintype "input"))
      (node (ref "IC15") (pin "7") (pinfunction "GPB6_7") (pintype "bidirectional"))
      (node (ref "Q13") (pin "4") (pinfunction "G_4") (pintype "passive"))
      (node (ref "Q14") (pin "3") (pinfunction "D_3") (pintype "passive"))
      (node (ref "Q15") (pin "3") (pinfunction "D_3") (pintype "passive"))
    )
    (net (code "19") (name "CURR_500MA") (class "Default")
      (node (ref "IC13") (pin "5") (pinfunction "E_5") (pintype "input"))
      (node (ref "IC15") (pin "6") (pinfunction "GPB5_6") (pintype "bidirectional"))
      (node (ref "Q12") (pin "4") (pinfunction "G_4") (pintype "passive"))
      (node (ref "Q15") (pin "1") (pinfunction "G_1") (pintype "passive"))
      (node (ref "Q16") (pin "E") (pinfunction "E_E") (pintype "passive"))
      (node (ref "R49") (pin "2") (pinfunction "2_2") (pintype "passive"))
    )
    (net (code "20") (name "CV_ACTIVE") (class "Default")
      (node (ref "IC15") (pin "23") (pinfunction "GPA2_23") (pintype "bidirectional"))
      (node (ref "Q23") (pin "1") (pinfunction "G_1") (pintype "passive"))
      (node (ref "R104") (pin "1") (pinfunction "1_1") (pintype "passive"))
      (node (ref "R106") (pin "2") (pinfunction "2_2") (pintype "passive"))
    )
    (net (code "21") (name "DIB_5V") (class "Default")
      (node (ref "X1") (pin "23") (pinfunction "1_23") (pintype "passive"))
      (node (ref "X1") (pin "24") (pinfunction "1_24") (pintype "passive"))
    )
    (net (code "22") (name "DIB_12V") (class "Default")
      (node (ref "X1") (pin "21") (pinfunction "1_21") (pintype "passive"))
      (node (ref "X1") (pin "22") (pinfunction "1_22") (pintype "passive"))
    )
    (net (code "23") (name "DIB_A0") (class "Default")
      (node (ref "IC6") (pin "1") (pinfunction "A0_1") (pintype "input"))
      (node (ref "IC7") (pin "7") (pinfunction "A0_7") (pintype "input"))
      (node (ref "R9") (pin "2") (pinfunction "2_2") (pintype "passive"))
      (node (ref "X1") (pin "17") (pinfunction "1_17") (pintype "passive"))
    )
    (net (code "24") (name "DIB_A1") (class "Default")
      (node (ref "IC6") (pin "2") (pinfunction "A1_2") (pintype "input"))
      (node (ref "IC7") (pin "6") (pinfunction "A1_6") (pintype "input"))
      (node (ref "R8") (pin "2") (pinfunction "2_2") (pintype "passive"))
      (node (ref "X1") (pin "19") (pinfunction "1_19") (pintype "passive"))
    )
    (net (code "25") (name "DIB_A2") (class "Default")
      (node (ref "IC6") (pin "3") (pinfunction "A2_3") (pintype "input"))
      (node (ref "IC7") (pin "5") (pinfunction "A2_5") (pintype "input"))
      (node (ref "R7") (pin "2") (pinfunction "2_2") (pintype "passive"))
      (node (ref "X1") (pin "18") (pinfunction "1_18") (pintype "passive"))
    )
    (net (code "26") (name "DIB_CSA") (class "Default")
      (node (ref "IC2") (pin "4") (pinfunction "A2_4") (pintype "input"))
      (node (ref "X1") (pin "9") (pinfunction "1_9") (pintype "passive"))
    )
    (net (code "27") (name "DIB_CSB") (class "Default")
      (node (ref "IC2") (pin "5") (pinfunction "A3_5") (pintype "input"))
      (node (ref "X1") (pin "12") (pinfunction "1_12") (pintype "passive"))
    )
    (net (code "28") (name "DIB_IRQ") (class "Default")
      (node (ref "IC5") (pin "6") (pinfunction "A4_6") (pintype "output"))
      (node (ref "X1") (pin "10") (pinfunction "1_10") (pintype "passive"))
    )
    (net (code "29") (name "DIB_MISO") (class "Default")
      (node (ref "IC2") (pin "6") (pinfunction "A4_6") (pintype "output"))
      (node (ref "X1") (pin "14") (pinfunction "1_14") (pintype "passive"))
    )
    (net (code "30") (name "DIB_MOSI") (class "Default")
      (node (ref "IC5") (pin "3") (pinfunction "A1_3") (pintype "input"))
      (node (ref "X1") (pin "15") (pinfunction "1_15") (pintype "passive"))
    )
    (net (code "31") (name "DIB_NFAULT") (class "Default")
      (node (ref "IC7") (pin "3") (pinfunction "ALERT_3") (pintype "passive"))
      (node (ref "X1") (pin "3") (pinfunction "1_3") (pintype "passive"))
    )
    (net (code "32") (name "DIB_NRESET") (class "Default")
      (node (ref "IC5") (pin "5") (pinfunction "A3_5") (pintype "input"))
      (node (ref "X1") (pin "4") (pinfunction "1_4") (pintype "passive"))
    )
    (net (code "33") (name "DIB_SCL") (class "Default")
      (node (ref "IC6") (pin "6") (pinfunction "SCL_6") (pintype "bidirectional"))
      (node (ref "IC7") (pin "2") (pinfunction "SCL_2") (pintype "bidirectional"))
      (node (ref "X1") (pin "5") (pinfunction "1_5") (pintype "passive"))
    )
    (net (code "34") (name "DIB_SCLK") (class "Default")
      (node (ref "IC2") (pin "3") (pinfunction "A1_3") (pintype "input"))
      (node (ref "X1") (pin "13") (pinfunction "1_13") (pintype "passive"))
    )
    (net (code "35") (name "DIB_SDA") (class "Default")
      (node (ref "IC6") (pin "5") (pinfunction "SDA_5") (pintype "bidirectional"))
      (node (ref "IC7") (pin "1") (pinfunction "SDA_1") (pintype "bidirectional"))
      (node (ref "X1") (pin "8") (pinfunction "1_8") (pintype "passive"))
    )
    (net (code "36") (name "GND") (class "Default")
      (node (ref "C10") (pin "1") (pinfunction "1_1") (pintype "passive"))
      (node (ref "C11") (pin "1") (pinfunction "1_1") (pintype "passive"))
      (node (ref "C12") (pin "1") (pinfunction "1_1") (pintype "passive"))
      (node (ref "C15") (pin "1") (pinfunction "1_1") (pintype "passive"))
      (node (ref "C20") (pin "2") (pinfunction "2_2") (pintype "passive"))
      (node (ref "C21") (pin "2") (pinfunction "2_2") (pintype "passive"))
      (node (ref "C23") (pin "2") (pinfunction "2_2") (pintype "passive"))
      (node (ref "C3") (pin "2") (pinfunction "2_2") (pintype "passive"))
      (node (ref "C30") (pin "1") (pinfunction "1_1") (pintype "passive"))
      (node (ref "C31") (pin "1") (pinfunction "1_1") (pintype "passive"))
      (node (ref "C33") (pin "1") (pinfunction "1_1") (pintype "passive"))
      (node (ref "C34") (pin "1") (pinfunction "1_1") (pintype "passive"))
      (node (ref "C36") (pin "2") (pinfunction "2_2") (pintype "passive"))
      (node (ref "C37") (pin "2") (pinfunction "2_2") (pintype "passive"))
      (node (ref "C38") (pin "2") (pinfunction "2_2") (pintype "passive"))
      (node (ref "C39") (pin "1") (pinfunction "1_1") (pintype "passive"))
      (node (ref "C4") (pin "2") (pinfunction "2_2") (pintype "passive"))
      (node (ref "C40") (pin "2") (pinfunction "2_2") (pintype "passive"))
      (node (ref "C41") (pin "2") (pinfunction "2_2") (pintype "passive"))
      (node (ref "C42") (pin "2") (pinfunction "2_2") (pintype "passive"))
      (node (ref "C45") (pin "2") (pinfunction "2_2") (pintype "passive"))
      (node (ref "C46") (pin "1") (pinfunction "1_1") (pintype "passive"))
      (node (ref "C47") (pin "2") (pinfunction "2_2") (pintype "passive"))
      (node (ref "C48") (pin "2") (pinfunction "2_2") (pintype "passive"))
      (node (ref "C49") (pin "1") (pinfunction "1_1") (pintype "passive"))
      (node (ref "C5") (pin "-") (pinfunction "-_-") (pintype "passive"))
      (node (ref "C50") (pin "-") (pinfunction "-_-") (pintype "passive"))
      (node (ref "C51") (pin "2") (pinfunction "2_2") (pintype "passive"))
      (node (ref "C52") (pin "1") (pinfunction "1_1") (pintype "passive"))
      (node (ref "C53") (pin "1") (pinfunction "1_1") (pintype "passive"))
      (node (ref "C54") (pin "1") (pinfunction "1_1") (pintype "passive"))
      (node (ref "C55") (pin "1") (pinfunction "1_1") (pintype "passive"))
      (node (ref "C56") (pin "2") (pinfunction "2_2") (pintype "passive"))
      (node (ref "C57") (pin "1") (pinfunction "1_1") (pintype "passive"))
      (node (ref "C58") (pin "1") (pinfunction "1_1") (pintype "passive"))
      (node (ref "C59") (pin "1") (pinfunction "1_1") (pintype "passive"))
      (node (ref "C60") (pin "1") (pinfunction "1_1") (pintype "passive"))
      (node (ref "C61") (pin "1") (pinfunction "1_1") (pintype "passive"))
      (node (ref "C62") (pin "1") (pinfunction "1_1") (pintype "passive"))
      (node (ref "C63") (pin "2") (pinfunction "2_2") (pintype "passive"))
      (node (ref "C64") (pin "1") (pinfunction "1_1") (pintype "passive"))
      (node (ref "C65") (pin "1") (pinfunction "1_1") (pintype "passive"))
      (node (ref "C66") (pin "1") (pinfunction "1_1") (pintype "passive"))
      (node (ref "C67") (pin "1") (pinfunction "1_1") (pintype "passive"))
      (node (ref "C68") (pin "1") (pinfunction "1_1") (pintype "passive"))
      (node (ref "C7") (pin "1") (pinfunction "1_1") (pintype "passive"))
      (node (ref "C8") (pin "2") (pinfunction "2_2") (pintype "passive"))
      (node (ref "C9") (pin "1") (pinfunction "1_1") (pintype "passive"))
      (node (ref "D19") (pin "C") (pinfunction "C_C") (pintype "passive"))
      (node (ref "D2") (pin "A") (pinfunction "A_A") (pintype "passive"))
      (node (ref "D3") (pin "C") (pinfunction "C_C") (pintype "passive"))
      (node (ref "IC1") (pin "4") (pinfunction "GND_4") (pintype "passive"))
      (node (ref "IC10") (pin "12") (pinfunction "+IN_12") (pintype "input"))
      (node (ref "IC11") (pin "5") (pinfunction "+IN_5") (pintype "input"))
      (node (ref "IC12") (pin "12") (pinfunction "+IN_12") (pintype "input"))
      (node (ref "IC12") (pin "3") (pinfunction "+IN_3") (pintype "input"))
      (node (ref "IC13") (pin "11") (pinfunction "Y_11") (pintype "tri_state"))
      (node (ref "IC13") (pin "12") (pinfunction "E_12") (pintype "input"))
      (node (ref "IC13") (pin "7") (pinfunction "VSS_7") (pintype "power_in"))
      (node (ref "IC13") (pin "8") (pinfunction "Y_8") (pintype "tri_state"))
      (node (ref "IC14") (pin "4") (pinfunction "VSS_4") (pintype "power_in"))
      (node (ref "IC15") (pin "10") (pinfunction "VSS_10") (pintype "power_in"))
      (node (ref "IC15") (pin "15") (pinfunction "A0_15") (pintype "input"))
      (node (ref "IC15") (pin "16") (pinfunction "A1_16") (pintype "input"))
      (node (ref "IC15") (pin "17") (pinfunction "A2_17") (pintype "input"))
      (node (ref "IC16") (pin "4") (pinfunction "GND_4") (pintype "passive"))
      (node (ref "IC17") (pin "8") (pinfunction "GND_8") (pintype "power_in"))
      (node (ref "IC18") (pin "2") (pinfunction "GND_2") (pintype "passive"))
      (node (ref "IC19") (pin "3") (pinfunction "CLK_3") (pintype "bidirectional"))
      (node (ref "IC19") (pin "4") (pinfunction "DGND_4") (pintype "passive"))
      (node (ref "IC19") (pin "5") (pinfunction "AVSS_5") (pintype "passive"))
      (node (ref "IC19") (pin "8") (pinfunction "REFN0_8") (pintype "input"))
      (node (ref "IC2") (pin "15") (pinfunction "GND2_15") (pintype "passive"))
      (node (ref "IC2") (pin "9") (pinfunction "GND2_2_9") (pintype "passive"))
      (node (ref "IC21") (pin "4") (pinfunction "V-_4") (pintype "power_in"))
      (node (ref "IC3") (pin "4") (pinfunction "GND_4") (pintype "passive"))
      (node (ref "IC4") (pin "5") (pinfunction "GND_5") (pintype "passive"))
      (node (ref "IC5") (pin "15") (pinfunction "GND2_15") (pintype "passive"))
      (node (ref "IC5") (pin "9") (pinfunction "GND2_2_9") (pintype "passive"))
      (node (ref "JP1") (pin "NO") (pinfunction "NO_NO") (pintype "passive"))
      (node (ref "Q14") (pin "2") (pinfunction "S_2") (pintype "passive"))
      (node (ref "Q15") (pin "2") (pinfunction "S_2") (pintype "passive"))
      (node (ref "Q16") (pin "C") (pinfunction "C_C") (pintype "passive"))
      (node (ref "Q17") (pin "C") (pinfunction "C_C") (pintype "passive"))
      (node (ref "Q18") (pin "2") (pinfunction "S_2") (pintype "passive"))
      (node (ref "Q21") (pin "2") (pinfunction "S_2") (pintype "passive"))
      (node (ref "Q23") (pin "2") (pinfunction "S_2") (pintype "passive"))
      (node (ref "Q24") (pin "2") (pinfunction "S_2") (pintype "passive"))
      (node (ref "Q26") (pin "E") (pinfunction "E_E") (pintype "passive"))
      (node (ref "Q28") (pin "E") (pinfunction "E_E") (pintype "passive"))
      (node (ref "Q30") (pin "3") (pinfunction "D_3") (pintype "passive"))
      (node (ref "Q31") (pin "2") (pinfunction "S_2") (pintype "passive"))
      (node (ref "R111") (pin "1") (pinfunction "1_1") (pintype "passive"))
      (node (ref "R113") (pin "2") (pinfunction "2_2") (pintype "passive"))
      (node (ref "R114") (pin "2") (pinfunction "2_2") (pintype "passive"))
      (node (ref "R115") (pin "1") (pinfunction "1_1") (pintype "passive"))
      (node (ref "R116") (pin "1") (pinfunction "1_1") (pintype "passive"))
      (node (ref "R117") (pin "2") (pinfunction "2_2") (pintype "passive"))
      (node (ref "R122") (pin "2") (pinfunction "2_2") (pintype "passive"))
      (node (ref "R124") (pin "1") (pinfunction "1_1") (pintype "passive"))
      (node (ref "R133") (pin "1") (pinfunction "1_1") (pintype "passive"))
      (node (ref "R138") (pin "1") (pinfunction "1_1") (pintype "passive"))
      (node (ref "R17") (pin "2") (pinfunction "2_2") (pintype "passive"))
      (node (ref "R27") (pin "1") (pinfunction "1_1") (pintype "passive"))
      (node (ref "R28") (pin "1") (pinfunction "1_1") (pintype "passive"))
      (node (ref "R31") (pin "1") (pinfunction "1_1") (pintype "passive"))
      (node (ref "R5") (pin "2") (pinfunction "2_2") (pintype "passive"))
      (node (ref "R69") (pin "1") (pinfunction "1_1") (pintype "passive"))
      (node (ref "R70") (pin "2") (pinfunction "2_2") (pintype "passive"))
      (node (ref "R72") (pin "1") (pinfunction "1_1") (pintype "passive"))
      (node (ref "R86") (pin "1") (pinfunction "1_1") (pintype "passive"))
      (node (ref "R88") (pin "1") (pinfunction "1_1") (pintype "passive"))
      (node (ref "R89") (pin "2") (pinfunction "2_2") (pintype "passive"))
      (node (ref "R90") (pin "1") (pinfunction "1_1") (pintype "passive"))
      (node (ref "R92") (pin "1") (pinfunction "1_1") (pintype "passive"))
      (node (ref "SH2") (pin "P$2") (pinfunction "GND_B_P$2") (pintype "bidirectional"))
      (node (ref "X2") (pin "2") (pinfunction "1_2") (pintype "passive"))
      (node (ref "X4") (pin "2") (pinfunction "1_2") (pintype "passive"))
      (node (ref "ZD3") (pin "1") (pinfunction "A_1") (pintype "passive"))
      (node (ref "ZD3") (pin "2") (pinfunction "A_2") (pintype "passive"))
    )
    (net (code "37") (name "GNDIO") (class "Default")
      (node (ref "C14") (pin "2") (pinfunction "2_2") (pintype "passive"))
      (node (ref "C16") (pin "1") (pinfunction "1_1") (pintype "passive"))
      (node (ref "C17") (pin "2") (pinfunction "2_2") (pintype "passive"))
      (node (ref "C6") (pin "2") (pinfunction "2_2") (pintype "passive"))
      (node (ref "IC2") (pin "2") (pinfunction "GND1_2_2") (pintype "passive"))
      (node (ref "IC2") (pin "8") (pinfunction "GND1_8") (pintype "passive"))
      (node (ref "IC5") (pin "2") (pinfunction "GND1_2_2") (pintype "passive"))
      (node (ref "IC5") (pin "8") (pinfunction "GND1_8") (pintype "passive"))
      (node (ref "IC6") (pin "4") (pinfunction "GND_4") (pintype "passive"))
      (node (ref "IC6") (pin "7") (pinfunction "WP_7") (pintype "input"))
      (node (ref "IC7") (pin "4") (pinfunction "GND_4") (pintype "passive"))
      (node (ref "X1") (pin "11") (pinfunction "1_11") (pintype "passive"))
      (node (ref "X1") (pin "16") (pinfunction "1_16") (pintype "passive"))
      (node (ref "X1") (pin "20") (pinfunction "1_20") (pintype "passive"))
      (node (ref "X1") (pin "25") (pinfunction "1_25") (pintype "passive"))
      (node (ref "X1") (pin "26") (pinfunction "1_26") (pintype "passive"))
      (node (ref "X1") (pin "7") (pinfunction "1_7") (pintype "passive"))
    )
    (net (code "38") (name "IRQ") (class "Default")
      (node (ref "JP4") (pin "COM") (pinfunction "COM_COM") (pintype "passive"))
      (node (ref "RN2") (pin "5") (pinfunction "2_5") (pintype "passive"))
    )
    (net (code "39") (name "ISENSE+") (class "Default")
      (node (ref "IC10") (pin "6") (pinfunction "-IN_6") (pintype "input"))
      (node (ref "R51") (pin "2") (pinfunction "2_2") (pintype "passive"))
      (node (ref "R52") (pin "2") (pinfunction "2_2") (pintype "passive"))
      (node (ref "R54") (pin "1") (pinfunction "1_1") (pintype "passive"))
      (node (ref "R55") (pin "2") (pinfunction "2_2") (pintype "passive"))
      (node (ref "R58") (pin "2") (pinfunction "2_2") (pintype "passive"))
    )
    (net (code "40") (name "ISENSE-") (class "Default")
      (node (ref "IC10") (pin "5") (pinfunction "+IN_5") (pintype "input"))
      (node (ref "R66") (pin "2") (pinfunction "2_2") (pintype "passive"))
      (node (ref "R69") (pin "2") (pinfunction "2_2") (pintype "passive"))
    )
    (net (code "41") (name "I_CTRL") (class "Default")
      (node (ref "IC10") (pin "8") (pinfunction "OUT_8") (pintype "output"))
      (node (ref "R43") (pin "1") (pinfunction "1_1") (pintype "passive"))
      (node (ref "R60") (pin "2") (pinfunction "2_2") (pintype "passive"))
    )
    (net (code "42") (name "I_MON") (class "Default")
      (node (ref "IC10") (pin "14") (pinfunction "OUT_14") (pintype "output"))
      (node (ref "R50") (pin "2") (pinfunction "2_2") (pintype "passive"))
      (node (ref "R99") (pin "1") (pinfunction "1_1") (pintype "passive"))
    )
    (net (code "43") (name "I_SERVO") (class "Default")
      (node (ref "C32") (pin "2") (pinfunction "2_2") (pintype "passive"))
      (node (ref "D12") (pin "C") (pinfunction "C_C") (pintype "passive"))
      (node (ref "D13") (pin "A") (pinfunction "A_A") (pintype "passive"))
      (node (ref "IC9") (pin "1") (pinfunction "OUT_1") (pintype "output"))
      (node (ref "R121") (pin "1") (pinfunction "1_1") (pintype "passive"))
    )
    (net (code "44") (name "I_SET") (class "Default")
      (node (ref "IC17") (pin "4") (pinfunction "VOUTA_4") (pintype "output"))
      (node (ref "R42") (pin "1") (pinfunction "1_1") (pintype "passive"))
      (node (ref "R94") (pin "1") (pinfunction "1_1") (pintype "passive"))
    )
    (net (code "45") (name "MISO") (class "Default")
      (node (ref "IC15") (pin "14") (pinfunction "SO_14") (pintype "output"))
      (node (ref "IC19") (pin "15") (pinfunction "DOUT/~{DRDY}_15") (pintype "output"))
      (node (ref "RN2") (pin "7") (pinfunction "2_7") (pintype "passive"))
    )
    (net (code "46") (name "MOSI") (class "Default")
      (node (ref "IC15") (pin "13") (pinfunction "SI_13") (pintype "input"))
      (node (ref "IC17") (pin "7") (pinfunction "DIN_7") (pintype "input"))
      (node (ref "IC19") (pin "16") (pinfunction "DIN_16") (pintype "input"))
      (node (ref "RN2") (pin "6") (pinfunction "2_6") (pintype "passive"))
    )
    (net (code "47") (name "Net-(C1-Pad2)") (class "Default")
      (node (ref "C1") (pin "2") (pinfunction "2_2") (pintype "passive"))
      (node (ref "JP1") (pin "COM") (pinfunction "COM_COM") (pintype "passive"))
      (node (ref "R2") (pin "2") (pinfunction "2_2") (pintype "passive"))
      (node (ref "R3") (pin "2") (pinfunction "2_2") (pintype "passive"))
    )
    (net (code "48") (name "Net-(C22-Pad2)") (class "Default")
      (node (ref "C22") (pin "2") (pinfunction "2_2") (pintype "passive"))
      (node (ref "R25") (pin "1") (pinfunction "1_1") (pintype "passive"))
    )
    (net (code "49") (name "Net-(C23-Pad1)") (class "Default")
      (node (ref "C23") (pin "1") (pinfunction "1_1") (pintype "passive"))
      (node (ref "R21") (pin "1") (pinfunction "1_1") (pintype "passive"))
    )
    (net (code "50") (name "Net-(C24-Pad1)") (class "Default")
      (node (ref "C24") (pin "1") (pinfunction "1_1") (pintype "passive"))
      (node (ref "R29") (pin "2") (pinfunction "2_2") (pintype "passive"))
      (node (ref "R30") (pin "1") (pinfunction "1_1") (pintype "passive"))
    )
    (net (code "51") (name "Net-(C25-Pad2)") (class "Default")
      (node (ref "C25") (pin "2") (pinfunction "2_2") (pintype "passive"))
      (node (ref "R32") (pin "1") (pinfunction "1_1") (pintype "passive"))
    )
    (net (code "52") (name "Net-(C26-Pad1)") (class "Default")
      (node (ref "C26") (pin "1") (pinfunction "1_1") (pintype "passive"))
      (node (ref "R38") (pin "2") (pinfunction "2_2") (pintype "passive"))
      (node (ref "R39") (pin "1") (pinfunction "1_1") (pintype "passive"))
    )
    (net (code "53") (name "Net-(C28-Pad2)") (class "Default")
      (node (ref "C28") (pin "2") (pinfunction "2_2") (pintype "passive"))
      (node (ref "R40") (pin "1") (pinfunction "1_1") (pintype "passive"))
    )
    (net (code "54") (name "Net-(C29-Pad2)") (class "Default")
      (node (ref "C29") (pin "2") (pinfunction "2_2") (pintype "passive"))
      (node (ref "R41") (pin "1") (pinfunction "1_1") (pintype "passive"))
    )
    (net (code "55") (name "Net-(C32-Pad1)") (class "Default")
      (node (ref "C32") (pin "1") (pinfunction "1_1") (pintype "passive"))
      (node (ref "R44") (pin "1") (pinfunction "1_1") (pintype "passive"))
    )
    (net (code "56") (name "Net-(C35-Pad2)") (class "Default")
      (node (ref "C35") (pin "2") (pinfunction "2_2") (pintype "passive"))
      (node (ref "R46") (pin "1") (pinfunction "1_1") (pintype "passive"))
    )
    (net (code "57") (name "Net-(C43-Pad1)") (class "Default")
      (node (ref "C43") (pin "1") (pinfunction "1_1") (pintype "passive"))
      (node (ref "R77") (pin "1") (pinfunction "1_1") (pintype "passive"))
    )
    (net (code "58") (name "Net-(C44-Pad1)") (class "Default")
      (node (ref "C44") (pin "1") (pinfunction "1_1") (pintype "passive"))
      (node (ref "R84") (pin "1") (pinfunction "1_1") (pintype "passive"))
    )
    (net (code "59") (name "Net-(C69-Pad2)") (class "Default")
      (node (ref "C69") (pin "2") (pinfunction "2_2") (pintype "passive"))
      (node (ref "Q27") (pin "B") (pinfunction "B_B") (pintype "passive"))
      (node (ref "R123") (pin "1") (pinfunction "1_1") (pintype "passive"))
      (node (ref "R126") (pin "2") (pinfunction "2_2") (pintype "passive"))
      (node (ref "R128") (pin "2") (pinfunction "2_2") (pintype "passive"))
    )
    (net (code "60") (name "Net-(C71-Pad1)") (class "Default")
      (node (ref "C71") (pin "1") (pinfunction "1_1") (pintype "passive"))
      (node (ref "Q26") (pin "B") (pinfunction "B_B") (pintype "passive"))
      (node (ref "R124") (pin "2") (pinfunction "2_2") (pintype "passive"))
      (node (ref "R125") (pin "2") (pinfunction "2_2") (pintype "passive"))
    )
    (net (code "61") (name "Net-(C71-Pad2)") (class "Default")
      (node (ref "C71") (pin "2") (pinfunction "2_2") (pintype "passive"))
      (node (ref "Q27") (pin "C") (pinfunction "C_C") (pintype "passive"))
      (node (ref "R125") (pin "1") (pinfunction "1_1") (pintype "passive"))
      (node (ref "R130") (pin "2") (pinfunction "2_2") (pintype "passive"))
    )
    (net (code "62") (name "Net-(C72-Pad2)") (class "Default")
      (node (ref "C72") (pin "2") (pinfunction "2_2") (pintype "passive"))
      (node (ref "R131") (pin "2") (pinfunction "2_2") (pintype "passive"))
    )
    (net (code "63") (name "Net-(C75-Pad1)") (class "Default")
      (node (ref "C75") (pin "1") (pinfunction "1_1") (pintype "passive"))
      (node (ref "Q29") (pin "B") (pinfunction "B_B") (pintype "passive"))
      (node (ref "R132") (pin "1") (pinfunction "1_1") (pintype "passive"))
      (node (ref "R134") (pin "2") (pinfunction "2_2") (pintype "passive"))
    )
    (net (code "64") (name "Net-(D5-PadC)") (class "Default")
      (node (ref "D5") (pin "C") (pinfunction "C_C") (pintype "passive"))
      (node (ref "Q2") (pin "2") (pinfunction "C_2") (pintype "passive"))
      (node (ref "Q2") (pin "4") (pinfunction "C_4") (pintype "passive"))
    )
    (net (code "65") (name "Net-(D7-PadC)") (class "Default")
      (node (ref "D7") (pin "C") (pinfunction "C_C") (pintype "passive"))
      (node (ref "ZD2") (pin "C") (pinfunction "C_C") (pintype "passive"))
    )
    (net (code "66") (name "Net-(D8-PadC)") (class "Default")
      (node (ref "D8") (pin "C") (pinfunction "C_C") (pintype "passive"))
      (node (ref "Q6") (pin "2") (pinfunction "C_2") (pintype "passive"))
      (node (ref "Q6") (pin "4") (pinfunction "C_4") (pintype "passive"))
      (node (ref "ZD2") (pin "A") (pinfunction "A_A") (pintype "passive"))
    )
    (net (code "67") (name "Net-(D9-PadC)") (class "Default")
      (node (ref "D9") (pin "C") (pinfunction "C_C") (pintype "passive"))
      (node (ref "ZD1") (pin "C") (pinfunction "C_C") (pintype "passive"))
    )
    (net (code "68") (name "Net-(D10-PadA)") (class "Default")
      (node (ref "D10") (pin "A") (pinfunction "A_A") (pintype "passive"))
      (node (ref "D12") (pin "A") (pinfunction "A_A") (pintype "passive"))
      (node (ref "R34") (pin "1") (pinfunction "1_1") (pintype "passive"))
    )
    (net (code "69") (name "Net-(D14-PadA)") (class "Default")
      (node (ref "D14") (pin "A") (pinfunction "A_A") (pintype "passive"))
      (node (ref "R47") (pin "2") (pinfunction "2_2") (pintype "passive"))
    )
    (net (code "70") (name "Net-(D16-PadA)") (class "Default")
      (node (ref "D16") (pin "A") (pinfunction "A_A") (pintype "passive"))
      (node (ref "R68") (pin "1") (pinfunction "1_1") (pintype "passive"))
    )
    (net (code "71") (name "Net-(D18-PadA)") (class "Default")
      (node (ref "D18") (pin "A") (pinfunction "A_A") (pintype "passive"))
      (node (ref "Q22") (pin "B") (pinfunction "B_B") (pintype "passive"))
      (node (ref "R109") (pin "1") (pinfunction "1_1") (pintype "passive"))
      (node (ref "R115") (pin "2") (pinfunction "2_2") (pintype "passive"))
    )
    (net (code "72") (name "Net-(D18-PadC)") (class "Default")
      (node (ref "D18") (pin "C") (pinfunction "C_C") (pintype "passive"))
      (node (ref "D19") (pin "A") (pinfunction "A_A") (pintype "passive"))
    )
    (net (code "73") (name "Net-(D20-C)") (class "Default")
      (node (ref "C69") (pin "1") (pinfunction "1_1") (pintype "passive"))
      (node (ref "C70") (pin "1") (pinfunction "1_1") (pintype "passive"))
      (node (ref "C72") (pin "1") (pinfunction "1_1") (pintype "passive"))
      (node (ref "C73") (pin "+") (pinfunction "+_+") (pintype "passive"))
      (node (ref "D20") (pin "3") (pinfunction "C_3") (pintype "passive"))
      (node (ref "F1") (pin "2") (pinfunction "2_2") (pintype "passive"))
      (node (ref "F2") (pin "1") (pinfunction "1_1") (pintype "passive"))
      (node (ref "K1") (pin "2") (pinfunction "O_2") (pintype "passive"))
      (node (ref "Q27") (pin "E") (pinfunction "E_E") (pintype "passive"))
      (node (ref "R123") (pin "2") (pinfunction "2_2") (pintype "passive"))
    )
    (net (code "74") (name "Net-(FB1-1)") (class "Default")
      (node (ref "FB1") (pin "P$1") (pinfunction "1_P$1") (pintype "passive"))
      (node (ref "X2") (pin "3") (pinfunction "1_3") (pintype "passive"))
    )
    (net (code "75") (name "Net-(FB4-1)") (class "Default")
      (node (ref "FB4") (pin "P$1") (pinfunction "1_P$1") (pintype "passive"))
      (node (ref "X2") (pin "1") (pinfunction "1_1") (pintype "passive"))
    )
    (net (code "76") (name "Net-(FB8-2)") (class "Default")
      (node (ref "C21") (pin "1") (pinfunction "1_1") (pintype "passive"))
      (node (ref "FB8") (pin "P$2") (pinfunction "2_P$2") (pintype "passive"))
      (node (ref "Q4") (pin "2") (pinfunction "C_2") (pintype "passive"))
      (node (ref "Q4") (pin "4") (pinfunction "C_4") (pintype "passive"))
      (node (ref "R19") (pin "2") (pinfunction "2_2") (pintype "passive"))
      (node (ref "R20") (pin "2") (pinfunction "2_2") (pintype "passive"))
    )
    (net (code "77") (name "Net-(IC1-FB)") (class "Default")
      (node (ref "IC1") (pin "7") (pinfunction "FB_7") (pintype "input"))
      (node (ref "R4") (pin "2") (pinfunction "2_2") (pintype "passive"))
      (node (ref "R5") (pin "1") (pinfunction "1_1") (pintype "passive"))
    )
    (net (code "78") (name "Net-(IC2-B1)") (class "Default")
      (node (ref "IC2") (pin "14") (pinfunction "B1_14") (pintype "output"))
      (node (ref "RN2") (pin "1") (pinfunction "1_1") (pintype "passive"))
    )
    (net (code "79") (name "Net-(IC2-B4)") (class "Default")
      (node (ref "IC2") (pin "11") (pinfunction "B4_11") (pintype "input"))
      (node (ref "RN2") (pin "2") (pinfunction "1_2") (pintype "passive"))
    )
    (net (code "80") (name "Net-(IC3-Y0)") (class "Default")
      (node (ref "IC3") (pin "7") (pinfunction "Y0_7") (pintype "output"))
      (node (ref "RN1") (pin "1") (pinfunction "1_1") (pintype "passive"))
    )
    (net (code "81") (name "Net-(IC3-Y1)") (class "Default")
      (node (ref "IC3") (pin "6") (pinfunction "Y1_6") (pintype "output"))
      (node (ref "RN1") (pin "2") (pinfunction "1_2") (pintype "passive"))
    )
    (net (code "82") (name "Net-(IC3-Y3)") (class "Default")
      (node (ref "IC3") (pin "3") (pinfunction "Y3_3") (pintype "output"))
      (node (ref "RN1") (pin "4") (pinfunction "1_4") (pintype "passive"))
    )
    (net (code "83") (name "Net-(IC5-B1)") (class "Default")
      (node (ref "IC5") (pin "14") (pinfunction "B1_14") (pintype "output"))
      (node (ref "RN2") (pin "3") (pinfunction "1_3") (pintype "passive"))
    )
    (net (code "84") (name "Net-(IC5-B4)") (class "Default")
      (node (ref "IC5") (pin "11") (pinfunction "B4_11") (pintype "input"))
      (node (ref "RN2") (pin "4") (pinfunction "1_4") (pintype "passive"))
    )
    (net (code "85") (name "Net-(IC8A-+IN)") (class "Default")
      (node (ref "IC8") (pin "3") (pinfunction "+IN_3") (pintype "input"))
      (node (ref "R32") (pin "2") (pinfunction "2_2") (pintype "passive"))
      (node (ref "R33") (pin "2") (pinfunction "2_2") (pintype "passive"))
    )
    (net (code "86") (name "Net-(IC8A--IN)") (class "Default")
      (node (ref "C27") (pin "1") (pinfunction "1_1") (pintype "passive"))
      (node (ref "D11") (pin "C") (pinfunction "C_C") (pintype "passive"))
      (node (ref "IC8") (pin "2") (pinfunction "-IN_2") (pintype "input"))
      (node (ref "R36") (pin "2") (pinfunction "2_2") (pintype "passive"))
      (node (ref "R41") (pin "2") (pinfunction "2_2") (pintype "passive"))
    )
    (net (code "87") (name "Net-(IC8B-+IN)") (class "Default")
      (node (ref "IC8") (pin "5") (pinfunction "+IN_5") (pintype "input"))
      (node (ref "R24") (pin "2") (pinfunction "2_2") (pintype "passive"))
      (node (ref "R25") (pin "2") (pinfunction "2_2") (pintype "passive"))
      (node (ref "R29") (pin "1") (pinfunction "1_1") (pintype "passive"))
    )
    (net (code "88") (name "Net-(IC8B--IN)") (class "Default")
      (node (ref "IC8") (pin "6") (pinfunction "-IN_6") (pintype "input"))
      (node (ref "R37") (pin "2") (pinfunction "2_2") (pintype "passive"))
      (node (ref "R38") (pin "1") (pinfunction "1_1") (pintype "passive"))
      (node (ref "R40") (pin "2") (pinfunction "2_2") (pintype "passive"))
    )
    (net (code "89") (name "Net-(IC9A-+IN)") (class "Default")
      (node (ref "IC9") (pin "3") (pinfunction "+IN_3") (pintype "input"))
      (node (ref "R42") (pin "2") (pinfunction "2_2") (pintype "passive"))
    )
    (net (code "90") (name "Net-(IC9A--IN)") (class "Default")
      (node (ref "D13") (pin "C") (pinfunction "C_C") (pintype "passive"))
      (node (ref "IC9") (pin "2") (pinfunction "-IN_2") (pintype "input"))
      (node (ref "R43") (pin "2") (pinfunction "2_2") (pintype "passive"))
      (node (ref "R45") (pin "2") (pinfunction "2_2") (pintype "passive"))
      (node (ref "R46") (pin "2") (pinfunction "2_2") (pintype "passive"))
    )
    (net (code "91") (name "Net-(IC9B-+IN)") (class "Default")
      (node (ref "C20") (pin "1") (pinfunction "1_1") (pintype "passive"))
      (node (ref "IC9") (pin "5") (pinfunction "+IN_5") (pintype "input"))
      (node (ref "R14") (pin "2") (pinfunction "2_2") (pintype "passive"))
      (node (ref "R17") (pin "1") (pinfunction "1_1") (pintype "passive"))
    )
    (net (code "92") (name "Net-(IC9B--IN)") (class "Default")
      (node (ref "IC9") (pin "6") (pinfunction "-IN_6") (pintype "input"))
      (node (ref "IC9") (pin "7") (pinfunction "OUT_7") (pintype "output"))
      (node (ref "R24") (pin "1") (pinfunction "1_1") (pintype "passive"))
    )
    (net (code "93") (name "Net-(IC10A-+IN)") (class "Default")
      (node (ref "IC10") (pin "3") (pinfunction "+IN_3") (pintype "input"))
      (node (ref "R67") (pin "1") (pinfunction "1_1") (pintype "passive"))
      (node (ref "R70") (pin "1") (pinfunction "1_1") (pintype "passive"))
    )
    (net (code "94") (name "Net-(IC10A--IN)") (class "Default")
      (node (ref "IC10") (pin "2") (pinfunction "-IN_2") (pintype "input"))
      (node (ref "R59") (pin "2") (pinfunction "2_2") (pintype "passive"))
      (node (ref "R65") (pin "1") (pinfunction "1_1") (pintype "passive"))
    )
    (net (code "95") (name "Net-(IC10A-OUT)") (class "Default")
      (node (ref "IC10") (pin "1") (pinfunction "OUT_1") (pintype "output"))
      (node (ref "R59") (pin "1") (pinfunction "1_1") (pintype "passive"))
      (node (ref "R74") (pin "2") (pinfunction "2_2") (pintype "passive"))
      (node (ref "R80") (pin "2") (pinfunction "2_2") (pintype "passive"))
    )
    (net (code "96") (name "Net-(IC10B-OUT)") (class "Default")
      (node (ref "IC10") (pin "7") (pinfunction "OUT_7") (pintype "output"))
      (node (ref "R53") (pin "1") (pinfunction "1_1") (pintype "passive"))
      (node (ref "R54") (pin "2") (pinfunction "2_2") (pintype "passive"))
      (node (ref "R64") (pin "1") (pinfunction "1_1") (pintype "passive"))
    )
    (net (code "97") (name "Net-(IC10C-+IN)") (class "Default")
      (node (ref "IC10") (pin "10") (pinfunction "+IN_10") (pintype "input"))
      (node (ref "R71") (pin "1") (pinfunction "1_1") (pintype "passive"))
      (node (ref "R72") (pin "2") (pinfunction "2_2") (pintype "passive"))
    )
    (net (code "98") (name "Net-(IC10C--IN)") (class "Default")
      (node (ref "IC10") (pin "9") (pinfunction "-IN_9") (pintype "input"))
      (node (ref "R60") (pin "1") (pinfunction "1_1") (pintype "passive"))
      (node (ref "R64") (pin "2") (pinfunction "2_2") (pintype "passive"))
    )
    (net (code "99") (name "Net-(IC10D--IN)") (class "Default")
      (node (ref "IC10") (pin "13") (pinfunction "-IN_13") (pintype "input"))
      (node (ref "R50") (pin "1") (pinfunction "1_1") (pintype "passive"))
      (node (ref "R53") (pin "2") (pinfunction "2_2") (pintype "passive"))
    )
    (net (code "100") (name "Net-(IC11A-+IN)") (class "Default")
      (node (ref "IC11") (pin "3") (pinfunction "+IN_3") (pintype "input"))
      (node (ref "IC13") (pin "2") (pinfunction "Z_2") (pintype "tri_state"))
      (node (ref "IC13") (pin "3") (pinfunction "Z_3") (pintype "tri_state"))
      (node (ref "IC13") (pin "9") (pinfunction "Z_9") (pintype "tri_state"))
    )
    (net (code "101") (name "Net-(IC11A--IN)") (class "Default")
      (node (ref "IC11") (pin "1") (pinfunction "OUT_1") (pintype "output"))
      (node (ref "IC11") (pin "2") (pinfunction "-IN_2") (pintype "input"))
      (node (ref "R71") (pin "2") (pinfunction "2_2") (pintype "passive"))
    )
    (net (code "102") (name "Net-(IC11B--IN)") (class "Default")
      (node (ref "IC11") (pin "6") (pinfunction "-IN_6") (pintype "input"))
      (node (ref "R83") (pin "2") (pinfunction "2_2") (pintype "passive"))
      (node (ref "R85") (pin "1") (pinfunction "1_1") (pintype "passive"))
    )
    (net (code "103") (name "Net-(IC11B-OUT)") (class "Default")
      (node (ref "IC11") (pin "7") (pinfunction "OUT_7") (pintype "output"))
      (node (ref "R81") (pin "2") (pinfunction "2_2") (pintype "passive"))
      (node (ref "R83") (pin "1") (pinfunction "1_1") (pintype "passive"))
    )
    (net (code "104") (name "Net-(IC12A--IN)") (class "Default")
      (node (ref "IC12") (pin "2") (pinfunction "-IN_2") (pintype "input"))
      (node (ref "R76") (pin "2") (pinfunction "2_2") (pintype "passive"))
      (node (ref "R79") (pin "1") (pinfunction "1_1") (pintype "passive"))
    )
    (net (code "105") (name "Net-(IC12A-OUT)") (class "Default")
      (node (ref "IC12") (pin "1") (pinfunction "OUT_1") (pintype "output"))
      (node (ref "R75") (pin "2") (pinfunction "2_2") (pintype "passive"))
      (node (ref "R76") (pin "1") (pinfunction "1_1") (pintype "passive"))
    )
    (net (code "106") (name "Net-(IC12B-+IN)") (class "Default")
      (node (ref "IC12") (pin "5") (pinfunction "+IN_5") (pintype "input"))
      (node (ref "R75") (pin "1") (pinfunction "1_1") (pintype "passive"))
      (node (ref "R77") (pin "2") (pinfunction "2_2") (pintype "passive"))
    )
    (net (code "107") (name "Net-(IC12B--IN)") (class "Default")
      (node (ref "D16") (pin "C") (pinfunction "C_C") (pintype "passive"))
      (node (ref "IC12") (pin "6") (pinfunction "-IN_6") (pintype "input"))
      (node (ref "R74") (pin "1") (pinfunction "1_1") (pintype "passive"))
    )
    (net (code "108") (name "Net-(IC12B-OUT)") (class "Default")
      (node (ref "C43") (pin "2") (pinfunction "2_2") (pintype "passive"))
      (node (ref "IC12") (pin "7") (pinfunction "OUT_7") (pintype "output"))
      (node (ref "R56") (pin "2") (pinfunction "2_2") (pintype "passive"))
    )
    (net (code "109") (name "Net-(IC12C-+IN)") (class "Default")
      (node (ref "IC12") (pin "10") (pinfunction "+IN_10") (pintype "input"))
      (node (ref "R81") (pin "1") (pinfunction "1_1") (pintype "passive"))
      (node (ref "R84") (pin "2") (pinfunction "2_2") (pintype "passive"))
    )
    (net (code "110") (name "Net-(IC12C--IN)") (class "Default")
      (node (ref "IC12") (pin "9") (pinfunction "-IN_9") (pintype "input"))
      (node (ref "R80") (pin "1") (pinfunction "1_1") (pintype "passive"))
    )
    (net (code "111") (name "Net-(IC12C-OUT)") (class "Default")
      (node (ref "C44") (pin "2") (pinfunction "2_2") (pintype "passive"))
      (node (ref "IC12") (pin "8") (pinfunction "OUT_8") (pintype "output"))
      (node (ref "R57") (pin "2") (pinfunction "2_2") (pintype "passive"))
      (node (ref "R68") (pin "2") (pinfunction "2_2") (pintype "passive"))
    )
    (net (code "112") (name "Net-(IC12D--IN)") (class "Default")
      (node (ref "IC12") (pin "13") (pinfunction "-IN_13") (pintype "input"))
      (node (ref "IC12") (pin "14") (pinfunction "OUT_14") (pintype "output"))
    )
    (net (code "113") (name "Net-(IC13A-Y)") (class "Default")
      (node (ref "IC13") (pin "1") (pinfunction "Y_1") (pintype "tri_state"))
      (node (ref "R78") (pin "1") (pinfunction "1_1") (pintype "passive"))
      (node (ref "R82") (pin "2") (pinfunction "2_2") (pintype "passive"))
    )
    (net (code "114") (name "Net-(IC13B-Y)") (class "Default")
      (node (ref "IC13") (pin "4") (pinfunction "Y_4") (pintype "tri_state"))
      (node (ref "R82") (pin "1") (pinfunction "1_1") (pintype "passive"))
      (node (ref "R86") (pin "2") (pinfunction "2_2") (pintype "passive"))
    )
    (net (code "115") (name "Net-(IC14A-Q)") (class "Default")
      (node (ref "IC14") (pin "5") (pinfunction "Q_5") (pintype "output"))
      (node (ref "JP3") (pin "2") (pinfunction "2_2") (pintype "passive"))
      (node (ref "Q18") (pin "1") (pinfunction "G_1") (pintype "passive"))
      (node (ref "R88") (pin "2") (pinfunction "2_2") (pintype "passive"))
    )
    (net (code "116") (name "Net-(IC15-INTA)") (class "Default")
      (node (ref "IC15") (pin "20") (pinfunction "INTA_20") (pintype "output"))
      (node (ref "JP4") (pin "NO") (pinfunction "NO_NO") (pintype "passive"))
    )
    (net (code "117") (name "Net-(IC16-TRIM{slash}NR)") (class "Default")
      (node (ref "C51") (pin "1") (pinfunction "1_1") (pintype "passive"))
      (node (ref "IC16") (pin "5") (pinfunction "TRIM/NR_5") (pintype "input"))
    )
    (net (code "118") (name "Net-(IC18-NO)") (class "Default")
      (node (ref "C55") (pin "2") (pinfunction "2_2") (pintype "passive"))
      (node (ref "IC18") (pin "1") (pinfunction "NO_1") (pintype "bidirectional"))
      (node (ref "R96") (pin "1") (pinfunction "1_1") (pintype "passive"))
      (node (ref "ZD3") (pin "3") (pinfunction "C_3") (pintype "passive"))
    )
    (net (code "119") (name "Net-(IC19-AIN0{slash}REFP1)") (class "Default")
      (node (ref "C57") (pin "2") (pinfunction "2_2") (pintype "passive"))
      (node (ref "IC19") (pin "11") (pinfunction "AIN0/REFP1_11") (pintype "input"))
      (node (ref "R98") (pin "2") (pinfunction "2_2") (pintype "passive"))
    )
    (net (code "120") (name "Net-(IC19-AIN1)") (class "Default")
      (node (ref "C53") (pin "2") (pinfunction "2_2") (pintype "passive"))
      (node (ref "IC19") (pin "10") (pinfunction "AIN1_10") (pintype "input"))
      (node (ref "R94") (pin "2") (pinfunction "2_2") (pintype "passive"))
    )
    (net (code "121") (name "Net-(IC19-AIN2)") (class "Default")
      (node (ref "C54") (pin "2") (pinfunction "2_2") (pintype "passive"))
      (node (ref "IC19") (pin "7") (pinfunction "AIN2_7") (pintype "input"))
      (node (ref "R95") (pin "2") (pinfunction "2_2") (pintype "passive"))
    )
    (net (code "122") (name "Net-(IC19-AIN3{slash}REFN1)") (class "Default")
      (node (ref "C56") (pin "1") (pinfunction "1_1") (pintype "passive"))
      (node (ref "IC19") (pin "6") (pinfunction "AIN3/REFN1_6") (pintype "input"))
      (node (ref "R99") (pin "2") (pinfunction "2_2") (pintype "passive"))
    )
    (net (code "123") (name "Net-(IC19-AVDD)") (class "Default")
      (node (ref "C60") (pin "2") (pinfunction "2_2") (pintype "passive"))
      (node (ref "C61") (pin "2") (pinfunction "2_2") (pintype "passive"))
      (node (ref "IC19") (pin "12") (pinfunction "AVDD_12") (pintype "power_in"))
      (node (ref "R100") (pin "2") (pinfunction "2_2") (pintype "passive"))
    )
    (net (code "124") (name "Net-(IC19-~{DRDY})") (class "Default")
      (node (ref "IC19") (pin "14") (pinfunction "~{DRDY}_14") (pintype "output"))
      (node (ref "JP4") (pin "NC") (pinfunction "NC_NC") (pintype "passive"))
    )
    (net (code "125") (name "Net-(IC20A-+IN)") (class "Default")
      (node (ref "IC20") (pin "7") (pinfunction "+IN_7") (pintype "input"))
      (node (ref "IC20") (pin "9") (pinfunction "+IN_9") (pintype "input"))
      (node (ref "R105") (pin "1") (pinfunction "1_1") (pintype "passive"))
      (node (ref "R111") (pin "2") (pinfunction "2_2") (pintype "passive"))
    )
    (net (code "126") (name "Net-(IC20A--IN)") (class "Default")
      (node (ref "IC20") (pin "5") (pinfunction "+IN_5") (pintype "input"))
      (node (ref "IC20") (pin "6") (pinfunction "-IN_6") (pintype "input"))
      (node (ref "R101") (pin "2") (pinfunction "2_2") (pintype "passive"))
    )
    (net (code "127") (name "Net-(IC20A-OUT)") (class "Default")
      (node (ref "IC20") (pin "1") (pinfunction "OUT_1") (pintype "open_collector"))
      (node (ref "IC20") (pin "2") (pinfunction "OUT_2") (pintype "open_collector"))
      (node (ref "R106") (pin "1") (pinfunction "1_1") (pintype "passive"))
    )
    (net (code "128") (name "Net-(IC20B--IN)") (class "Default")
      (node (ref "IC20") (pin "10") (pinfunction "-IN_10") (pintype "input"))
      (node (ref "IC20") (pin "4") (pinfunction "-IN_4") (pintype "input"))
      (node (ref "R117") (pin "1") (pinfunction "1_1") (pintype "passive"))
      (node (ref "R119") (pin "2") (pinfunction "2_2") (pintype "passive"))
    )
    (net (code "129") (name "Net-(IC20C--IN)") (class "Default")
      (node (ref "IC20") (pin "11") (pinfunction "+IN_11") (pintype "input"))
      (node (ref "IC20") (pin "8") (pinfunction "-IN_8") (pintype "input"))
      (node (ref "R121") (pin "2") (pinfunction "2_2") (pintype "passive"))
    )
    (net (code "130") (name "Net-(IC20C-OUT)") (class "Default")
      (node (ref "IC20") (pin "13") (pinfunction "OUT_13") (pintype "open_collector"))
      (node (ref "IC20") (pin "14") (pinfunction "OUT_14") (pintype "open_collector"))
      (node (ref "R120") (pin "1") (pinfunction "1_1") (pintype "passive"))
    )
    (net (code "131") (name "Net-(IC21A-+IN)") (class "Default")
      (node (ref "C66") (pin "2") (pinfunction "2_2") (pintype "passive"))
      (node (ref "IC21") (pin "2") (pinfunction "+IN_2") (pintype "input"))
      (node (ref "Q21") (pin "3") (pinfunction "D_3") (pintype "passive"))
      (node (ref "R102") (pin "2") (pinfunction "2_2") (pintype "passive"))
    )
    (net (code "132") (name "Net-(IC21A--IN)") (class "Default")
      (node (ref "C68") (pin "2") (pinfunction "2_2") (pintype "passive"))
      (node (ref "IC21") (pin "3") (pinfunction "-IN_3") (pintype "input"))
      (node (ref "R108") (pin "2") (pinfunction "2_2") (pintype "passive"))
      (node (ref "R113") (pin "1") (pinfunction "1_1") (pintype "passive"))
    )
    (net (code "133") (name "Net-(IC21A-BAL{slash}STRB)") (class "Default")
      (node (ref "IC21") (pin "6") (pinfunction "BAL/STRB_6") (pintype "input"))
      (node (ref "Q25") (pin "C") (pinfunction "C_C") (pintype "passive"))
    )
    (net (code "134") (name "Net-(K1A--)") (class "Default")
      (node (ref "D21") (pin "A") (pinfunction "A_A") (pintype "passive"))
      (node (ref "K1") (pin "8") (pinfunction "-_8") (pintype "passive"))
      (node (ref "Q31") (pin "3") (pinfunction "D_3") (pintype "passive"))
      (node (ref "R137") (pin "1") (pinfunction "1_1") (pintype "passive"))
    )
    (net (code "135") (name "Net-(K1B-S)") (class "Default")
      (node (ref "K1") (pin "4") (pinfunction "S_4") (pintype "passive"))
      (node (ref "X4") (pin "4") (pinfunction "1_4") (pintype "passive"))
    )
    (net (code "136") (name "Net-(K1C-S)") (class "Default")
      (node (ref "K1") (pin "5") (pinfunction "S_5") (pintype "passive"))
      (node (ref "X4") (pin "5") (pinfunction "1_5") (pintype "passive"))
    )
    (net (code "137") (name "Net-(LED1-C)") (class "Default")
      (node (ref "LED1") (pin "CC") (pinfunction "C_CC") (pintype "passive"))
      (node (ref "R89") (pin "1") (pinfunction "1_1") (pintype "passive"))
    )
    (net (code "138") (name "Net-(LED2A-C)") (class "Default")
      (node (ref "LED2") (pin "BC") (pinfunction "C_BC") (pintype "passive"))
      (node (ref "R137") (pin "2") (pinfunction "2_2") (pintype "passive"))
    )
    (net (code "139") (name "Net-(LED2B-C)") (class "Default")
      (node (ref "LED2") (pin "TC") (pinfunction "C_TC") (pintype "passive"))
      (node (ref "R92") (pin "2") (pinfunction "2_2") (pintype "passive"))
    )
    (net (code "140") (name "Net-(LED3A-C)") (class "Default")
      (node (ref "LED3") (pin "BC") (pinfunction "C_BC") (pintype "passive"))
      (node (ref "R112") (pin "2") (pinfunction "2_2") (pintype "passive"))
    )
    (net (code "141") (name "Net-(LED3B-C)") (class "Default")
      (node (ref "LED3") (pin "TC") (pinfunction "C_TC") (pintype "passive"))
      (node (ref "R107") (pin "1") (pinfunction "1_1") (pintype "passive"))
    )
    (net (code "142") (name "Net-(LED4-PadA)") (class "Default")
      (node (ref "LED4") (pin "A") (pinfunction "A_A") (pintype "passive"))
      (node (ref "R135") (pin "1") (pinfunction "1_1") (pintype "passive"))
    )
    (net (code "143") (name "Net-(Q1-G)") (class "Default")
      (node (ref "D6") (pin "C") (pinfunction "C_C") (pintype "passive"))
      (node (ref "D7") (pin "A") (pinfunction "A_A") (pintype "passive"))
      (node (ref "Q1") (pin "1") (pinfunction "G_1") (pintype "passive"))
      (node (ref "R10") (pin "1") (pinfunction "1_1") (pintype "passive"))
    )
    (net (code "144") (name "Net-(Q2-E)") (class "Default")
      (node (ref "Q2") (pin "3") (pinfunction "E_3") (pintype "passive"))
      (node (ref "R13") (pin "2") (pinfunction "2_2") (pintype "passive"))
    )
    (net (code "145") (name "Net-(Q3-PadB)") (class "Default")
      (node (ref "Q3") (pin "B") (pinfunction "B_B") (pintype "passive"))
      (node (ref "R15") (pin "2") (pinfunction "2_2") (pintype "passive"))
    )
    (net (code "146") (name "Net-(Q4-B)") (class "Default")
      (node (ref "D9") (pin "A") (pinfunction "A_A") (pintype "passive"))
      (node (ref "Q4") (pin "1") (pinfunction "B_1") (pintype "passive"))
      (node (ref "R21") (pin "2") (pinfunction "2_2") (pintype "passive"))
      (node (ref "R22") (pin "1") (pinfunction "1_1") (pintype "passive"))
    )
    (net (code "147") (name "Net-(Q4-E)") (class "Default")
      (node (ref "D6") (pin "A") (pinfunction "A_A") (pintype "passive"))
      (node (ref "Q4") (pin "3") (pinfunction "E_3") (pintype "passive"))
    )
    (net (code "148") (name "Net-(Q5-G)") (class "Default")
      (node (ref "D8") (pin "A") (pinfunction "A_A") (pintype "passive"))
      (node (ref "Q3") (pin "C") (pinfunction "C_C") (pintype "passive"))
      (node (ref "Q5") (pin "1") (pinfunction "G_1") (pintype "passive"))
      (node (ref "R16") (pin "2") (pinfunction "2_2") (pintype "passive"))
    )
    (net (code "149") (name "Net-(Q5-S)") (class "Default")
      (node (ref "Q5") (pin "3") (pinfunction "S_3") (pintype "passive"))
      (node (ref "R11") (pin "1") (pinfunction "1_1") (pintype "passive"))
      (node (ref "R12") (pin "1") (pinfunction "1_1") (pintype "passive"))
      (node (ref "R15") (pin "1") (pinfunction "1_1") (pintype "passive"))
      (node (ref "R16") (pin "1") (pinfunction "1_1") (pintype "passive"))
    )
    (net (code "150") (name "Net-(Q6-E)") (class "Default")
      (node (ref "Q6") (pin "3") (pinfunction "E_3") (pintype "passive"))
      (node (ref "R26") (pin "1") (pinfunction "1_1") (pintype "passive"))
    )
    (net (code "151") (name "Net-(Q7-PadE)") (class "Default")
      (node (ref "Q7") (pin "E") (pinfunction "E_E") (pintype "passive"))
      (node (ref "R19") (pin "1") (pinfunction "1_1") (pintype "passive"))
    )
    (net (code "152") (name "Net-(Q8-PadE)") (class "Default")
      (node (ref "Q8") (pin "E") (pinfunction "E_E") (pintype "passive"))
      (node (ref "R20") (pin "1") (pinfunction "1_1") (pintype "passive"))
    )
    (net (code "153") (name "Net-(Q9-PadB)") (class "Default")
      (node (ref "Q9") (pin "B") (pinfunction "B_B") (pintype "passive"))
      (node (ref "R18") (pin "1") (pinfunction "1_1") (pintype "passive"))
      (node (ref "R27") (pin "2") (pinfunction "2_2") (pintype "passive"))
      (node (ref "R28") (pin "2") (pinfunction "2_2") (pintype "passive"))
    )
    (net (code "154") (name "Net-(Q9-PadE)") (class "Default")
      (node (ref "Q9") (pin "E") (pinfunction "E_E") (pintype "passive"))
      (node (ref "R34") (pin "2") (pinfunction "2_2") (pintype "passive"))
    )
    (net (code "155") (name "Net-(Q10-PadC)") (class "Default")
      (node (ref "Q10") (pin "C") (pinfunction "C_C") (pintype "passive"))
      (node (ref "Q7") (pin "B") (pinfunction "B_B") (pintype "passive"))
      (node (ref "Q7") (pin "C") (pinfunction "C_C") (pintype "passive"))
      (node (ref "Q8") (pin "B") (pinfunction "B_B") (pintype "passive"))
    )
    (net (code "156") (name "Net-(Q10-PadE)") (class "Default")
      (node (ref "Q10") (pin "E") (pinfunction "E_E") (pintype "passive"))
      (node (ref "R35") (pin "2") (pinfunction "2_2") (pintype "passive"))
    )
    (net (code "157") (name "Net-(Q11-S-Pad1)") (class "Default")
      (node (ref "Q11") (pin "1") (pinfunction "S_1") (pintype "passive"))
      (node (ref "Q11") (pin "2") (pinfunction "S_2") (pintype "passive"))
      (node (ref "Q11") (pin "3") (pinfunction "S_3") (pintype "passive"))
      (node (ref "R63") (pin "2") (pinfunction "2_2") (pintype "passive"))
    )
    (net (code "158") (name "Net-(Q12-S-Pad1)") (class "Default")
      (node (ref "Q12") (pin "1") (pinfunction "S_1") (pintype "passive"))
      (node (ref "Q12") (pin "2") (pinfunction "S_2") (pintype "passive"))
      (node (ref "Q12") (pin "3") (pinfunction "S_3") (pintype "passive"))
      (node (ref "R55") (pin "1") (pinfunction "1_1") (pintype "passive"))
      (node (ref "R62") (pin "2") (pinfunction "2_2") (pintype "passive"))
    )
    (net (code "159") (name "Net-(Q13-S-Pad1)") (class "Default")
      (node (ref "Q13") (pin "1") (pinfunction "S_1") (pintype "passive"))
      (node (ref "Q13") (pin "2") (pinfunction "S_2") (pintype "passive"))
      (node (ref "Q13") (pin "3") (pinfunction "S_3") (pintype "passive"))
      (node (ref "R58") (pin "1") (pinfunction "1_1") (pintype "passive"))
      (node (ref "R61") (pin "1") (pinfunction "1_1") (pintype "passive"))
    )
    (net (code "160") (name "Net-(Q16-PadB)") (class "Default")
      (node (ref "Q16") (pin "B") (pinfunction "B_B") (pintype "passive"))
      (node (ref "R56") (pin "1") (pinfunction "1_1") (pintype "passive"))
    )
    (net (code "161") (name "Net-(Q17-PadB)") (class "Default")
      (node (ref "Q17") (pin "B") (pinfunction "B_B") (pintype "passive"))
      (node (ref "R57") (pin "1") (pinfunction "1_1") (pintype "passive"))
    )
    (net (code "162") (name "Net-(Q19-D)") (class "Default")
      (node (ref "Q19") (pin "3") (pinfunction "D_3") (pintype "passive"))
      (node (ref "R93") (pin "2") (pinfunction "2_2") (pintype "passive"))
    )
    (net (code "163") (name "Net-(Q20-PadA2)") (class "Default")
      (node (ref "Q20") (pin "A2") (pinfunction "A2_A2") (pintype "passive"))
      (node (ref "R110") (pin "2") (pinfunction "2_2") (pintype "passive"))
    )
    (net (code "164") (name "Net-(Q20-PadG)") (class "Default")
      (node (ref "Q20") (pin "G") (pinfunction "G_G") (pintype "passive"))
      (node (ref "Q22") (pin "C") (pinfunction "C_C") (pintype "passive"))
      (node (ref "R103") (pin "1") (pinfunction "1_1") (pintype "passive"))
    )
    (net (code "165") (name "Net-(Q22-PadE)") (class "Default")
      (node (ref "Q22") (pin "E") (pinfunction "E_E") (pintype "passive"))
      (node (ref "R116") (pin "2") (pinfunction "2_2") (pintype "passive"))
    )
    (net (code "166") (name "Net-(Q23-D)") (class "Default")
      (node (ref "Q23") (pin "3") (pinfunction "D_3") (pintype "passive"))
      (node (ref "R107") (pin "2") (pinfunction "2_2") (pintype "passive"))
    )
    (net (code "167") (name "Net-(Q24-D)") (class "Default")
      (node (ref "Q24") (pin "3") (pinfunction "D_3") (pintype "passive"))
      (node (ref "R112") (pin "1") (pinfunction "1_1") (pintype "passive"))
    )
    (net (code "168") (name "Net-(Q25-PadE)") (class "Default")
      (node (ref "Q25") (pin "E") (pinfunction "E_E") (pintype "passive"))
      (node (ref "R122") (pin "1") (pinfunction "1_1") (pintype "passive"))
    )
    (net (code "169") (name "Net-(Q28-PadB)") (class "Default")
      (node (ref "Q28") (pin "B") (pinfunction "B_B") (pintype "passive"))
      (node (ref "R130") (pin "1") (pinfunction "1_1") (pintype "passive"))
      (node (ref "R133") (pin "2") (pinfunction "2_2") (pintype "passive"))
    )
    (net (code "170") (name "Net-(Q29-PadC)") (class "Default")
      (node (ref "Q29") (pin "C") (pinfunction "C_C") (pintype "passive"))
      (node (ref "R127") (pin "1") (pinfunction "1_1") (pintype "passive"))
    )
    (net (code "171") (name "Net-(Q30-G)") (class "Default")
      (node (ref "D22") (pin "A") (pinfunction "A_A") (pintype "passive"))
      (node (ref "D23") (pin "A") (pinfunction "A_A") (pintype "passive"))
      (node (ref "Q30") (pin "1") (pinfunction "G_1") (pintype "passive"))
      (node (ref "R136") (pin "2") (pinfunction "2_2") (pintype "passive"))
    )
    (net (code "172") (name "Net-(R44-Pad2)") (class "Default")
      (node (ref "R44") (pin "2") (pinfunction "2_2") (pintype "passive"))
      (node (ref "R45") (pin "1") (pinfunction "1_1") (pintype "passive"))
    )
    (net (code "173") (name "Net-(R52-Pad1)") (class "Default")
      (node (ref "R52") (pin "1") (pinfunction "1_1") (pintype "passive"))
      (node (ref "R63") (pin "2S") (pinfunction "2S_2S") (pintype "passive"))
    )
    (net (code "174") (name "Net-(R61-Pad2)") (class "Default")
      (node (ref "R61") (pin "2") (pinfunction "2_2") (pintype "passive"))
      (node (ref "R62") (pin "1") (pinfunction "1_1") (pintype "passive"))
      (node (ref "R63") (pin "1") (pinfunction "1_1") (pintype "passive"))
      (node (ref "R73") (pin "2") (pinfunction "2_2") (pintype "passive"))
    )
    (net (code "175") (name "Net-(R63-Pad1S)") (class "Default")
      (node (ref "R63") (pin "1S") (pinfunction "1S_1S") (pintype "passive"))
      (node (ref "R66") (pin "1") (pinfunction "1_1") (pintype "passive"))
    )
    (net (code "176") (name "Net-(R65-Pad2)") (class "Default")
      (node (ref "R65") (pin "2") (pinfunction "2_2") (pintype "passive"))
      (node (ref "R73") (pin "2S") (pinfunction "2S_2S") (pintype "passive"))
    )
    (net (code "177") (name "Net-(R67-Pad2)") (class "Default")
      (node (ref "R67") (pin "2") (pinfunction "2_2") (pintype "passive"))
      (node (ref "R73") (pin "1S") (pinfunction "1S_1S") (pintype "passive"))
    )
    (net (code "178") (name "Net-(R96-Pad2)") (class "Default")
      (node (ref "R96") (pin "2") (pinfunction "2_2") (pintype "passive"))
      (node (ref "R97") (pin "1") (pinfunction "1_1") (pintype "passive"))
    )
    (net (code "179") (name "Net-(R97-Pad2)") (class "Default")
      (node (ref "R97") (pin "2") (pinfunction "2_2") (pintype "passive"))
      (node (ref "X4") (pin "1") (pinfunction "1_1") (pintype "passive"))
    )
    (net (code "180") (name "Net-(R127-Pad2)") (class "Default")
      (node (ref "R127") (pin "2") (pinfunction "2_2") (pintype "passive"))
      (node (ref "R128") (pin "1") (pinfunction "1_1") (pintype "passive"))
    )
    (net (code "181") (name "Net-(X2E-1)") (class "Default")
      (node (ref "C1") (pin "1") (pinfunction "1_1") (pintype "passive"))
      (node (ref "R1") (pin "2") (pinfunction "2_2") (pintype "passive"))
      (node (ref "R2") (pin "1") (pinfunction "1_1") (pintype "passive"))
      (node (ref "R3") (pin "1") (pinfunction "1_1") (pintype "passive"))
      (node (ref "X2") (pin "5") (pinfunction "1_5") (pintype "passive"))
    )
    (net (code "182") (name "Net-(X2F-1)") (class "Default")
      (node (ref "JP1") (pin "NC") (pinfunction "NC_NC") (pintype "passive"))
      (node (ref "X2") (pin "6") (pinfunction "1_6") (pintype "passive"))
    )
    (net (code "183") (name "Net-(X2G-1)") (class "Default")
      (node (ref "JP2") (pin "NO") (pinfunction "NO_NO") (pintype "passive"))
      (node (ref "X2") (pin "7") (pinfunction "1_7") (pintype "passive"))
    )
    (net (code "184") (name "Net-(X2H-1)") (class "Default")
      (node (ref "JP2") (pin "NC") (pinfunction "NC_NC") (pintype "passive"))
      (node (ref "X2") (pin "8") (pinfunction "1_8") (pintype "passive"))
    )
    (net (code "185") (name "Net-(X3B-1)") (class "Default")
      (node (ref "FB7") (pin "1") (pinfunction "1_1") (pintype "passive"))
      (node (ref "X3") (pin "2") (pinfunction "1_2") (pintype "passive"))
    )
    (net (code "186") (name "OE_GREEN") (class "Default")
      (node (ref "IC15") (pin "27") (pinfunction "GPA6_27") (pintype "bidirectional"))
      (node (ref "LED1") (pin "GREEN") (pinfunction "AG_GREEN") (pintype "passive"))
    )
    (net (code "187") (name "OE_RED") (class "Default")
      (node (ref "IC15") (pin "28") (pinfunction "GPA7_28") (pintype "bidirectional"))
      (node (ref "LED1") (pin "RED") (pinfunction "AR_RED") (pintype "passive"))
    )
    (net (code "188") (name "OE_SYNC") (class "Default")
      (node (ref "IC5") (pin "4") (pinfunction "A2_4") (pintype "input"))
      (node (ref "X1") (pin "6") (pinfunction "1_6") (pintype "passive"))
    )
    (net (code "189") (name "OE_TRIG") (class "Default")
      (node (ref "IC14") (pin "1") (pinfunction "CLK_1") (pintype "input"))
      (node (ref "IC5") (pin "13") (pinfunction "B2_13") (pintype "output"))
    )
    (net (code "190") (name "OUTC+") (class "Default")
      (node (ref "J1") (pin "1") (pinfunction "1_1") (pintype "passive"))
      (node (ref "J1") (pin "NC1") (pinfunction "1_NC1") (pintype "passive"))
      (node (ref "J1") (pin "NC2") (pinfunction "1_NC2") (pintype "passive"))
      (node (ref "J1") (pin "NC3") (pinfunction "1_NC3") (pintype "passive"))
      (node (ref "J1") (pin "NC4") (pinfunction "1_NC4") (pintype "passive"))
      (node (ref "X5") (pin "1") (pinfunction "1_1") (pintype "passive"))
      (node (ref "X5") (pin "2") (pinfunction "1_2") (pintype "passive"))
      (node (ref "X5") (pin "3") (pinfunction "1_3") (pintype "passive"))
      (node (ref "X5") (pin "4") (pinfunction "1_4") (pintype "passive"))
      (node (ref "X5") (pin "5") (pinfunction "1_5") (pintype "passive"))
    )
    (net (code "191") (name "OUTC-") (class "Default")
      (node (ref "J2") (pin "1") (pinfunction "1_1") (pintype "passive"))
      (node (ref "J2") (pin "NC1") (pinfunction "1_NC1") (pintype "passive"))
      (node (ref "J2") (pin "NC2") (pinfunction "1_NC2") (pintype "passive"))
      (node (ref "J2") (pin "NC3") (pinfunction "1_NC3") (pintype "passive"))
      (node (ref "J2") (pin "NC4") (pinfunction "1_NC4") (pintype "passive"))
      (node (ref "X5") (pin "16") (pinfunction "1_16") (pintype "passive"))
      (node (ref "X5") (pin "17") (pinfunction "1_17") (pintype "passive"))
      (node (ref "X5") (pin "18") (pinfunction "1_18") (pintype "passive"))
      (node (ref "X5") (pin "19") (pinfunction "1_19") (pintype "passive"))
      (node (ref "X5") (pin "20") (pinfunction "1_20") (pintype "passive"))
    )
    (net (code "192") (name "OUTF+") (class "Default")
      (node (ref "F2") (pin "2") (pinfunction "2_2") (pintype "passive"))
      (node (ref "Q20") (pin "A1") (pinfunction "A1_A1") (pintype "passive"))
      (node (ref "R103") (pin "2") (pinfunction "2_2") (pintype "passive"))
      (node (ref "X5") (pin "10") (pinfunction "1_10") (pintype "passive"))
      (node (ref "X5") (pin "6") (pinfunction "1_6") (pintype "passive"))
      (node (ref "X5") (pin "7") (pinfunction "1_7") (pintype "passive"))
      (node (ref "X5") (pin "8") (pinfunction "1_8") (pintype "passive"))
      (node (ref "X5") (pin "9") (pinfunction "1_9") (pintype "passive"))
    )
    (net (code "193") (name "OVP_FAULT") (class "Default")
      (node (ref "IC15") (pin "25") (pinfunction "GPA4_25") (pintype "bidirectional"))
      (node (ref "IC21") (pin "1") (pinfunction "E_1") (pintype "passive"))
      (node (ref "Q21") (pin "1") (pinfunction "G_1") (pintype "passive"))
      (node (ref "R109") (pin "2") (pinfunction "2_2") (pintype "passive"))
      (node (ref "R114") (pin "1") (pinfunction "1_1") (pintype "passive"))
    )
    (net (code "194") (name "PE") (class "Default")
      (node (ref "C13") (pin "2") (pinfunction "2_2") (pintype "passive"))
      (node (ref "C18") (pin "2") (pinfunction "2_2") (pintype "passive"))
      (node (ref "C19") (pin "2") (pinfunction "2_2") (pintype "passive"))
      (node (ref "C2") (pin "2") (pinfunction "2_2") (pintype "passive"))
      (node (ref "C70") (pin "2") (pinfunction "2_2") (pintype "passive"))
      (node (ref "C74") (pin "1") (pinfunction "1_1") (pintype "passive"))
      (node (ref "C9") (pin "2") (pinfunction "2_2") (pintype "passive"))
      (node (ref "X3") (pin "3") (pinfunction "1_3") (pintype "passive"))
      (node (ref "X4") (pin "3") (pinfunction "1_3") (pintype "passive"))
    )
    (net (code "195") (name "POST_OE") (class "Default")
      (node (ref "Q18") (pin "3") (pinfunction "D_3") (pintype "passive"))
      (node (ref "R35") (pin "1") (pinfunction "1_1") (pintype "passive"))
    )
    (net (code "196") (name "POST_OUT+") (class "Default")
      (node (ref "C24") (pin "2") (pinfunction "2_2") (pintype "passive"))
      (node (ref "C29") (pin "1") (pinfunction "1_1") (pintype "passive"))
      (node (ref "C35") (pin "1") (pinfunction "1_1") (pintype "passive"))
      (node (ref "D5") (pin "A") (pinfunction "A_A") (pintype "passive"))
      (node (ref "F1") (pin "1") (pinfunction "1_1") (pintype "passive"))
      (node (ref "Q1") (pin "3") (pinfunction "S_3") (pintype "passive"))
      (node (ref "Q3") (pin "E") (pinfunction "E_E") (pintype "passive"))
      (node (ref "R1") (pin "1") (pinfunction "1_1") (pintype "passive"))
      (node (ref "R10") (pin "2") (pinfunction "2_2") (pintype "passive"))
      (node (ref "R11") (pin "2") (pinfunction "2_2") (pintype "passive"))
      (node (ref "R12") (pin "2") (pinfunction "2_2") (pintype "passive"))
      (node (ref "R18") (pin "2") (pinfunction "2_2") (pintype "passive"))
      (node (ref "ZD1") (pin "A") (pinfunction "A_A") (pintype "passive"))
    )
    (net (code "197") (name "POST_OUT-") (class "Default")
      (node (ref "C25") (pin "1") (pinfunction "1_1") (pintype "passive"))
      (node (ref "C26") (pin "2") (pinfunction "2_2") (pintype "passive"))
      (node (ref "C73") (pin "-") (pinfunction "-_-") (pintype "passive"))
      (node (ref "C74") (pin "2") (pinfunction "2_2") (pintype "passive"))
      (node (ref "C75") (pin "2") (pinfunction "2_2") (pintype "passive"))
      (node (ref "D15") (pin "A") (pinfunction "A_A") (pintype "passive"))
      (node (ref "D20") (pin "1") (pinfunction "A_1") (pintype "passive"))
      (node (ref "D20") (pin "2") (pinfunction "A_2") (pintype "passive"))
      (node (ref "K1") (pin "7") (pinfunction "O_7") (pintype "passive"))
      (node (ref "Q11") (pin "MB") (pinfunction "D_MB") (pintype "passive"))
      (node (ref "Q12") (pin "MB") (pinfunction "D_MB") (pintype "passive"))
      (node (ref "Q13") (pin "MB") (pinfunction "D_MB") (pintype "passive"))
      (node (ref "Q29") (pin "E") (pinfunction "E_E") (pintype "passive"))
      (node (ref "R131") (pin "1") (pinfunction "1_1") (pintype "passive"))
      (node (ref "R134") (pin "1") (pinfunction "1_1") (pintype "passive"))
      (node (ref "X5") (pin "11") (pinfunction "1_11") (pintype "passive"))
      (node (ref "X5") (pin "12") (pinfunction "1_12") (pintype "passive"))
      (node (ref "X5") (pin "13") (pinfunction "1_13") (pintype "passive"))
      (node (ref "X5") (pin "14") (pinfunction "1_14") (pintype "passive"))
      (node (ref "X5") (pin "15") (pinfunction "1_15") (pintype "passive"))
    )
    (net (code "198") (name "PREG_IN+") (class "Default")
      (node (ref "FB6") (pin "1") (pinfunction "1_1") (pintype "passive"))
      (node (ref "JP2") (pin "COM") (pinfunction "COM_COM") (pintype "passive"))
      (node (ref "X3") (pin "1") (pinfunction "1_1") (pintype "passive"))
    )
    (net (code "199") (name "PREG_IN-") (class "Default")
      (node (ref "C19") (pin "1") (pinfunction "1_1") (pintype "passive"))
      (node (ref "FB7") (pin "2") (pinfunction "2_2") (pintype "passive"))
      (node (ref "Q5") (pin "2") (pinfunction "D_2") (pintype "passive"))
      (node (ref "SH1") (pin "P$1") (pinfunction "GND_A_P$1") (pintype "bidirectional"))
      (node (ref "SH2") (pin "P$1") (pinfunction "GND_A_P$1") (pintype "bidirectional"))
    )
    (net (code "200") (name "PREG_OUT+") (class "Default")
      (node (ref "C18") (pin "1") (pinfunction "1_1") (pintype "passive"))
      (node (ref "FB6") (pin "2") (pinfunction "2_2") (pintype "passive"))
      (node (ref "Q1") (pin "2") (pinfunction "D_2") (pintype "passive"))
    )
    (net (code "201") (name "PREG_OUT-") (class "Default")
      (node (ref "D15") (pin "C") (pinfunction "C_C") (pintype "passive"))
      (node (ref "Q2") (pin "1") (pinfunction "B_1") (pintype "passive"))
      (node (ref "R110") (pin "1") (pinfunction "1_1") (pintype "passive"))
      (node (ref "R73") (pin "1") (pinfunction "1_1") (pintype "passive"))
      (node (ref "SH1") (pin "P$2") (pinfunction "GND_B_P$2") (pintype "bidirectional"))
    )
    (net (code "202") (name "PRE_OE") (class "Default")
      (node (ref "IC14") (pin "2") (pinfunction "D_2") (pintype "input"))
      (node (ref "IC15") (pin "2") (pinfunction "GPB1_2") (pintype "bidirectional"))
      (node (ref "JP3") (pin "1") (pinfunction "1_1") (pintype "passive"))
    )
    (net (code "203") (name "PWRGOOD") (class "Default")
      (node (ref "D23") (pin "C") (pinfunction "C_C") (pintype "passive"))
      (node (ref "IC1") (pin "5") (pinfunction "~{ERROR}_5") (pintype "input"))
      (node (ref "IC15") (pin "24") (pinfunction "GPA3_24") (pintype "bidirectional"))
      (node (ref "R6") (pin "2") (pinfunction "2_2") (pintype "passive"))
    )
    (net (code "204") (name "RSENSE") (class "Default")
      (node (ref "IC15") (pin "3") (pinfunction "GPB2_3") (pintype "bidirectional"))
      (node (ref "Q31") (pin "1") (pinfunction "G_1") (pintype "passive"))
      (node (ref "R138") (pin "2") (pinfunction "2_2") (pintype "passive"))
    )
    (net (code "205") (name "SCLK") (class "Default")
      (node (ref "IC15") (pin "12") (pinfunction "SCK_12") (pintype "input"))
      (node (ref "IC17") (pin "6") (pinfunction "SCLK_6") (pintype "input"))
      (node (ref "IC19") (pin "1") (pinfunction "SCLK_1") (pintype "input"))
      (node (ref "RN2") (pin "8") (pinfunction "2_8") (pintype "passive"))
    )
    (net (code "206") (name "SENSE+") (class "Default")
      (node (ref "C22") (pin "1") (pinfunction "1_1") (pintype "passive"))
      (node (ref "K1") (pin "3") (pinfunction "P_3") (pintype "passive"))
      (node (ref "R126") (pin "1") (pinfunction "1_1") (pintype "passive"))
      (node (ref "R30") (pin "2") (pinfunction "2_2") (pintype "passive"))
    )
    (net (code "207") (name "SENSE-") (class "Default")
      (node (ref "C28") (pin "1") (pinfunction "1_1") (pintype "passive"))
      (node (ref "K1") (pin "6") (pinfunction "P_6") (pintype "passive"))
      (node (ref "R132") (pin "2") (pinfunction "2_2") (pintype "passive"))
      (node (ref "R39") (pin "2") (pinfunction "2_2") (pintype "passive"))
    )
    (net (code "208") (name "SENSE_ERR") (class "Default")
      (node (ref "IC15") (pin "21") (pinfunction "GPA0_21") (pintype "bidirectional"))
      (node (ref "Q28") (pin "C") (pinfunction "C_C") (pintype "passive"))
      (node (ref "R129") (pin "1") (pinfunction "1_1") (pintype "passive"))
    )
    (net (code "209") (name "SENSE_PROT") (class "Default")
      (node (ref "Q26") (pin "C") (pinfunction "C_C") (pintype "passive"))
      (node (ref "Q8") (pin "C") (pinfunction "C_C") (pintype "passive"))
      (node (ref "Q9") (pin "C") (pinfunction "C_C") (pintype "passive"))
      (node (ref "R22") (pin "2") (pinfunction "2_2") (pintype "passive"))
      (node (ref "R31") (pin "2") (pinfunction "2_2") (pintype "passive"))
    )
    (net (code "210") (name "U_MON") (class "Default")
      (node (ref "IC8") (pin "7") (pinfunction "OUT_7") (pintype "output"))
      (node (ref "R108") (pin "1") (pinfunction "1_1") (pintype "passive"))
      (node (ref "R36") (pin "1") (pinfunction "1_1") (pintype "passive"))
      (node (ref "R37") (pin "1") (pinfunction "1_1") (pintype "passive"))
      (node (ref "R98") (pin "1") (pinfunction "1_1") (pintype "passive"))
    )
    (net (code "211") (name "U_SERVO") (class "Default")
      (node (ref "C27") (pin "2") (pinfunction "2_2") (pintype "passive"))
      (node (ref "D10") (pin "C") (pinfunction "C_C") (pintype "passive"))
      (node (ref "D11") (pin "A") (pinfunction "A_A") (pintype "passive"))
      (node (ref "IC8") (pin "1") (pinfunction "OUT_1") (pintype "output"))
      (node (ref "R101") (pin "1") (pinfunction "1_1") (pintype "passive"))
    )
    (net (code "212") (name "U_SET") (class "Default")
      (node (ref "IC17") (pin "3") (pinfunction "VOUTB_3") (pintype "output"))
      (node (ref "IC18") (pin "3") (pinfunction "NC_3") (pintype "bidirectional"))
      (node (ref "R102") (pin "1") (pinfunction "1_1") (pintype "passive"))
      (node (ref "R95") (pin "1") (pinfunction "1_1") (pintype "passive"))
    )
    (net (code "213") (name "U_SET_OUT") (class "Default")
      (node (ref "IC18") (pin "4") (pinfunction "COM_4") (pintype "bidirectional"))
      (node (ref "R33") (pin "1") (pinfunction "1_1") (pintype "passive"))
    )
    (net (code "214") (name "V+") (class "Default")
      (node (ref "C30") (pin "2") (pinfunction "2_2") (pintype "passive"))
      (node (ref "C31") (pin "2") (pinfunction "2_2") (pintype "passive"))
      (node (ref "C36") (pin "1") (pinfunction "1_1") (pintype "passive"))
      (node (ref "C37") (pin "1") (pinfunction "1_1") (pintype "passive"))
      (node (ref "C38") (pin "1") (pinfunction "1_1") (pintype "passive"))
      (node (ref "C39") (pin "2") (pinfunction "2_2") (pintype "passive"))
      (node (ref "C47") (pin "1") (pinfunction "1_1") (pintype "passive"))
      (node (ref "C48") (pin "1") (pinfunction "1_1") (pintype "passive"))
      (node (ref "C49") (pin "2") (pinfunction "2_2") (pintype "passive"))
      (node (ref "C63") (pin "1") (pinfunction "1_1") (pintype "passive"))
      (node (ref "C64") (pin "2") (pinfunction "2_2") (pintype "passive"))
      (node (ref "C65") (pin "2") (pinfunction "2_2") (pintype "passive"))
      (node (ref "FB2") (pin "P$2") (pinfunction "2_P$2") (pintype "passive"))
      (node (ref "IC10") (pin "4") (pinfunction "V+_4") (pintype "power_in"))
      (node (ref "IC11") (pin "8") (pinfunction "V+_8") (pintype "power_in"))
      (node (ref "IC12") (pin "11") (pinfunction "V-_11") (pintype "power_in"))
      (node (ref "IC13") (pin "14") (pinfunction "VDD_14") (pintype "power_in"))
      (node (ref "IC16") (pin "2") (pinfunction "VIN_2") (pintype "passive"))
      (node (ref "IC17") (pin "1") (pinfunction "VDD_1") (pintype "power_in"))
      (node (ref "IC18") (pin "5") (pinfunction "VDD_5") (pintype "power_in"))
      (node (ref "IC20") (pin "3") (pinfunction "V+_3") (pintype "power_in"))
      (node (ref "IC21") (pin "7") (pinfunction "C_7") (pintype "passive"))
      (node (ref "IC21") (pin "8") (pinfunction "V+_8") (pintype "power_in"))
      (node (ref "IC8") (pin "8") (pinfunction "V+_8") (pintype "power_in"))
      (node (ref "IC9") (pin "8") (pinfunction "V+_8") (pintype "power_in"))
      (node (ref "R100") (pin "1") (pinfunction "1_1") (pintype "passive"))
      (node (ref "R105") (pin "2") (pinfunction "2_2") (pintype "passive"))
      (node (ref "R47") (pin "1") (pinfunction "1_1") (pintype "passive"))
      (node (ref "R48") (pin "1") (pinfunction "1_1") (pintype "passive"))
      (node (ref "R49") (pin "1") (pinfunction "1_1") (pintype "passive"))
    )
    (net (code "215") (name "V-") (class "Default")
      (node (ref "C33") (pin "2") (pinfunction "2_2") (pintype "passive"))
      (node (ref "C34") (pin "2") (pinfunction "2_2") (pintype "passive"))
      (node (ref "C40") (pin "1") (pinfunction "1_1") (pintype "passive"))
      (node (ref "C41") (pin "1") (pinfunction "1_1") (pintype "passive"))
      (node (ref "C42") (pin "1") (pinfunction "1_1") (pintype "passive"))
      (node (ref "C67") (pin "2") (pinfunction "2_2") (pintype "passive"))
      (node (ref "FB5") (pin "P$2") (pinfunction "2_P$2") (pintype "passive"))
      (node (ref "IC10") (pin "11") (pinfunction "V-_11") (pintype "power_in"))
      (node (ref "IC11") (pin "4") (pinfunction "V-_4") (pintype "power_in"))
      (node (ref "IC12") (pin "4") (pinfunction "V+_4") (pintype "power_in"))
      (node (ref "IC20") (pin "12") (pinfunction "GND_12") (pintype "power_in"))
      (node (ref "IC8") (pin "4") (pinfunction "V-_4") (pintype "power_in"))
      (node (ref "IC9") (pin "4") (pinfunction "V-_4") (pintype "power_in"))
      (node (ref "R119") (pin "1") (pinfunction "1_1") (pintype "passive"))
      (node (ref "R13") (pin "1") (pinfunction "1_1") (pintype "passive"))
    )
    (net (code "216") (name "unconnected-(IC1-SD-Pad3)") (class "Default")
      (node (ref "IC1") (pin "3") (pinfunction "SD_3") (pintype "input"))
    )
    (net (code "217") (name "unconnected-(IC1-SENSE-Pad2)") (class "Default")
      (node (ref "IC1") (pin "2") (pinfunction "SENSE_2") (pintype "input"))
    )
    (net (code "218") (name "unconnected-(IC1-VTAP-Pad6)") (class "Default")
      (node (ref "IC1") (pin "6") (pinfunction "VTAP_6") (pintype "input"))
    )
    (net (code "219") (name "unconnected-(IC3-Y2-Pad5)") (class "Default")
      (node (ref "IC3") (pin "5") (pinfunction "Y2_5") (pintype "output"))
    )
    (net (code "220") (name "unconnected-(IC13D-Z-Pad10)") (class "Default")
      (node (ref "IC13") (pin "10") (pinfunction "Z_10") (pintype "tri_state"))
    )
    (net (code "221") (name "unconnected-(IC14A-~{Q}-Pad3)") (class "Default")
      (node (ref "IC14") (pin "3") (pinfunction "~{Q}_3") (pintype "output"))
    )
    (net (code "222") (name "unconnected-(IC15-GPB7-Pad8)") (class "Default")
      (node (ref "IC15") (pin "8") (pinfunction "GPB7_8") (pintype "bidirectional"))
    )
    (net (code "223") (name "unconnected-(IC15-INTB-Pad19)") (class "Default")
      (node (ref "IC15") (pin "19") (pinfunction "INTB_19") (pintype "output"))
    )
    (net (code "224") (name "unconnected-(IC16-TEMP-Pad3)") (class "Default")
      (node (ref "IC16") (pin "3") (pinfunction "TEMP_3") (pintype "input"))
    )
    (net (code "225") (name "unconnected-(IC21A-BALANCE-Pad5)") (class "Default")
      (node (ref "IC21") (pin "5") (pinfunction "BALANCE_5") (pintype "input"))
    )
    (net (code "226") (name "~{DP_DRIVE}") (class "Default")
      (node (ref "Q6") (pin "1") (pinfunction "B_1") (pintype "passive"))
      (node (ref "R23") (pin "1") (pinfunction "1_1") (pintype "passive"))
      (node (ref "R93") (pin "1") (pinfunction "1_1") (pintype "passive"))
    )
    (net (code "227") (name "~{FAULT_OUT}") (class "Default")
      (node (ref "D17") (pin "A") (pinfunction "A_A") (pintype "passive"))
      (node (ref "IC14") (pin "6") (pinfunction "~{CLR}_6") (pintype "input"))
      (node (ref "LED4") (pin "C") (pinfunction "C_C") (pintype "passive"))
      (node (ref "Q30") (pin "2") (pinfunction "S_2") (pintype "passive"))
      (node (ref "R87") (pin "2") (pinfunction "2_2") (pintype "passive"))
    )
    (net (code "228") (name "~{FAULT}") (class "Default")
      (node (ref "D22") (pin "C") (pinfunction "C_C") (pintype "passive"))
      (node (ref "X2") (pin "4") (pinfunction "1_4") (pintype "passive"))
    )
    (net (code "229") (name "~{OVP_EN}") (class "Default")
      (node (ref "IC15") (pin "26") (pinfunction "GPA5_26") (pintype "bidirectional"))
      (node (ref "Q25") (pin "B") (pinfunction "B_B") (pintype "passive"))
    )
    (net (code "230") (name "~{RESET}") (class "Default")
      (node (ref "D17") (pin "C") (pinfunction "C_C") (pintype "passive"))
      (node (ref "IC15") (pin "18") (pinfunction "~{RESET}_18") (pintype "input"))
      (node (ref "IC5") (pin "12") (pinfunction "B3_12") (pintype "output"))
    )
    (net (code "231") (name "~{SET_DP}") (class "Default")
      (node (ref "IC15") (pin "1") (pinfunction "GPB0_1") (pintype "bidirectional"))
      (node (ref "Q19") (pin "1") (pinfunction "G_1") (pintype "passive"))
      (node (ref "R91") (pin "2") (pinfunction "2_2") (pintype "passive"))
    )
  )
)
